# tc08-3-21.net
KiCad netlist of a schematic drawn in EAGLE
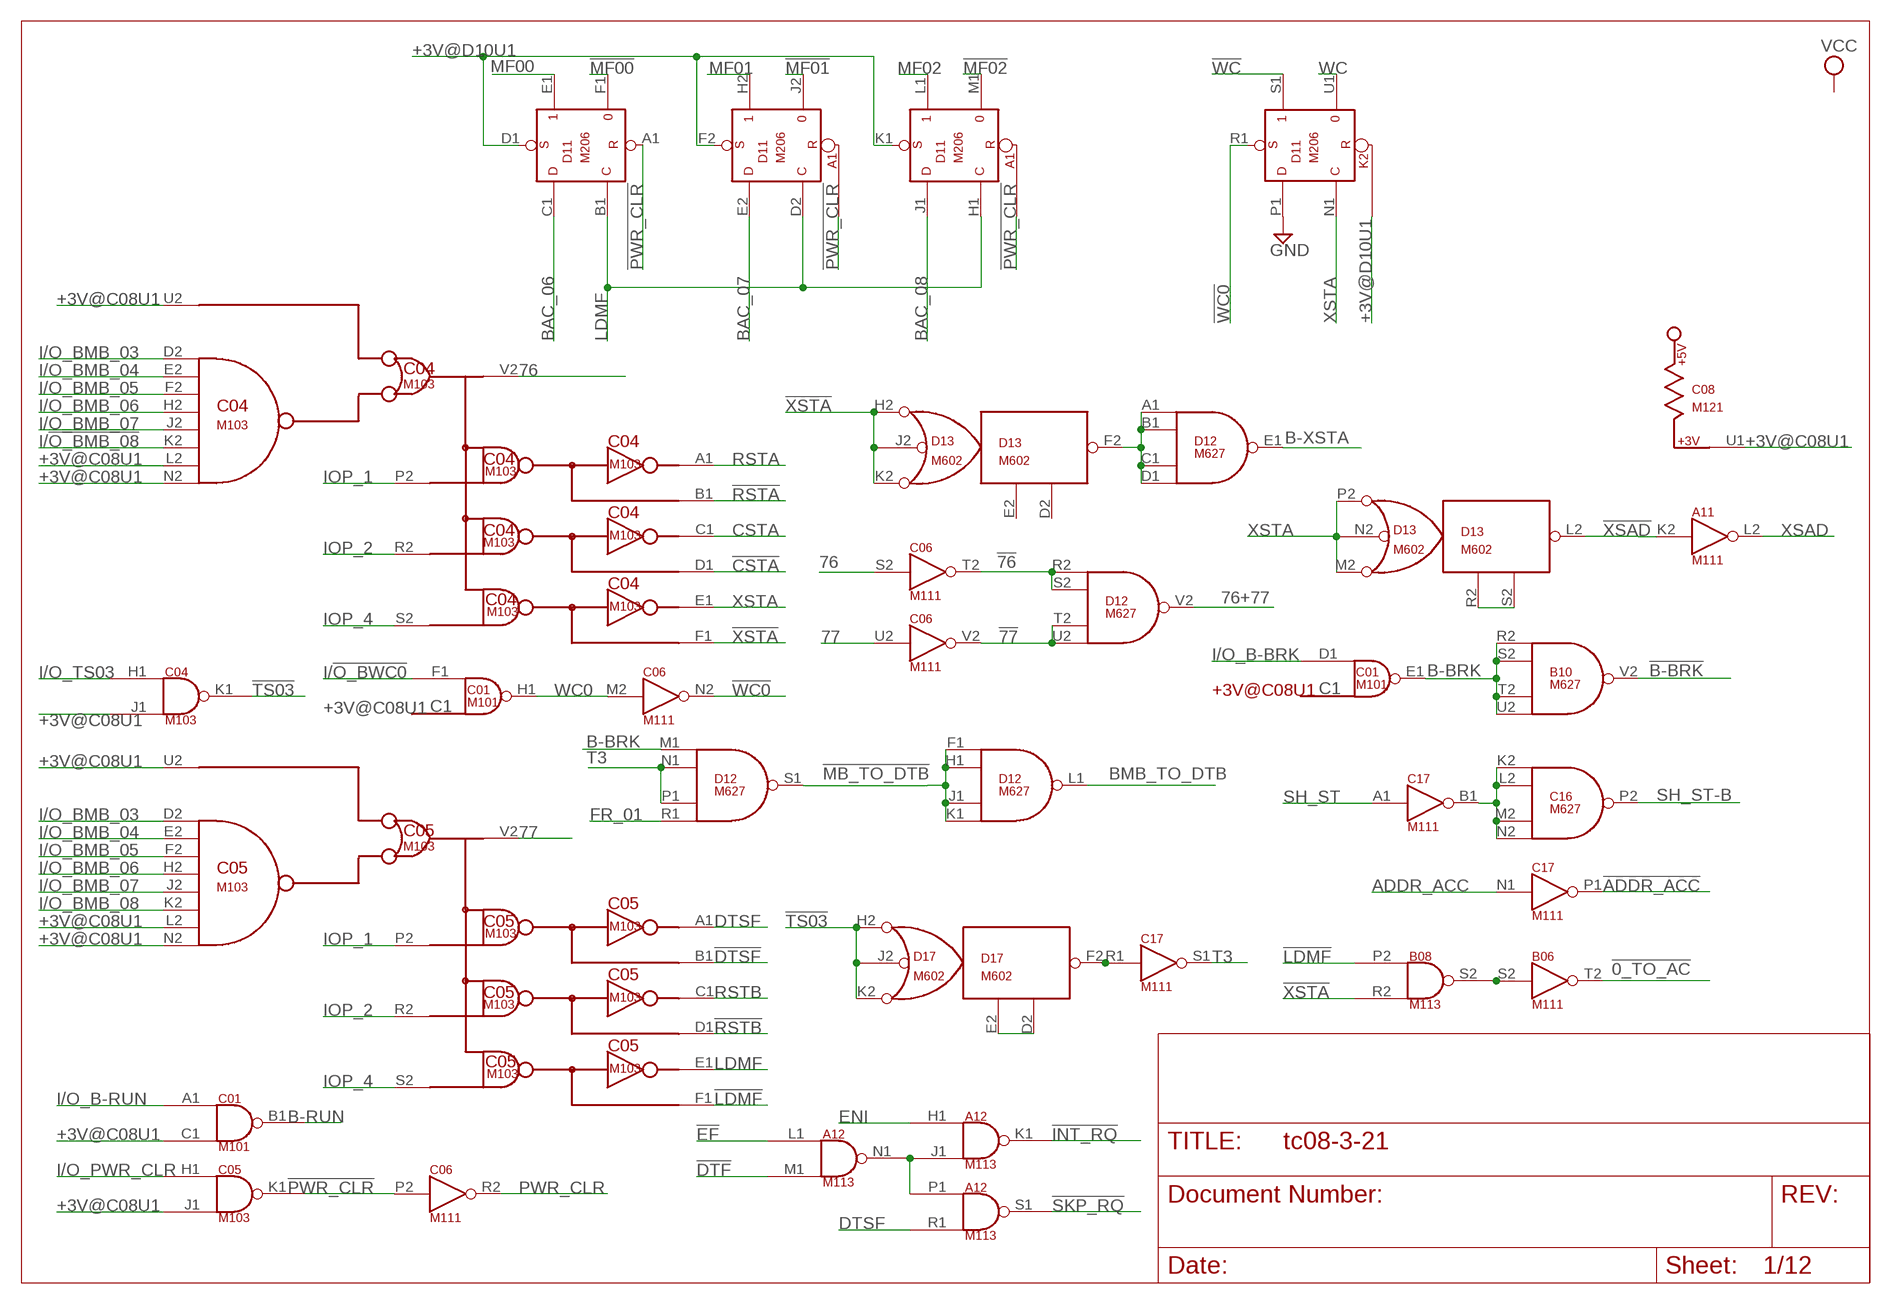
[diagram p0: schematic, sheet 1]
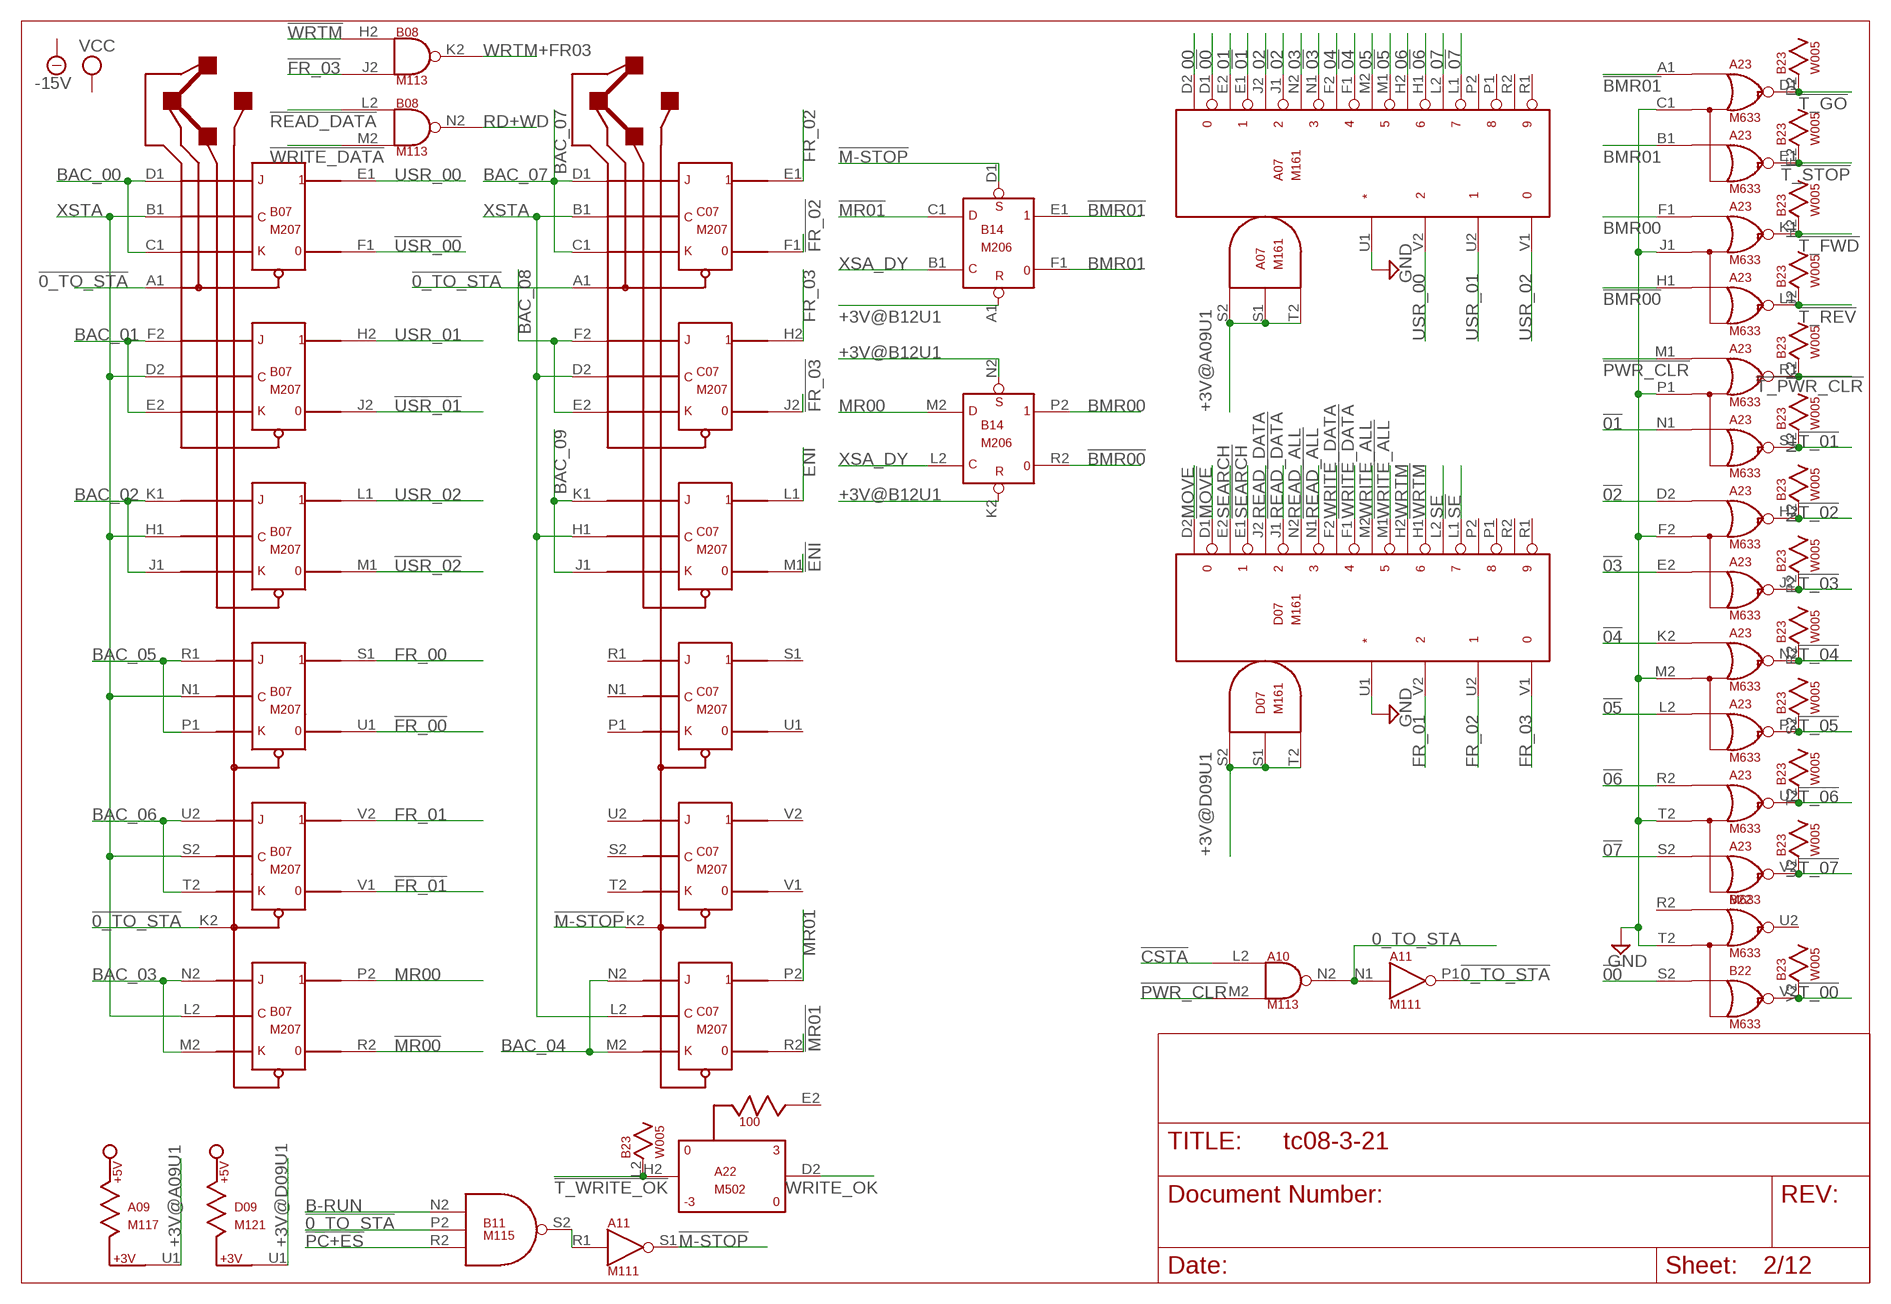
[diagram p1: schematic, sheet 2]
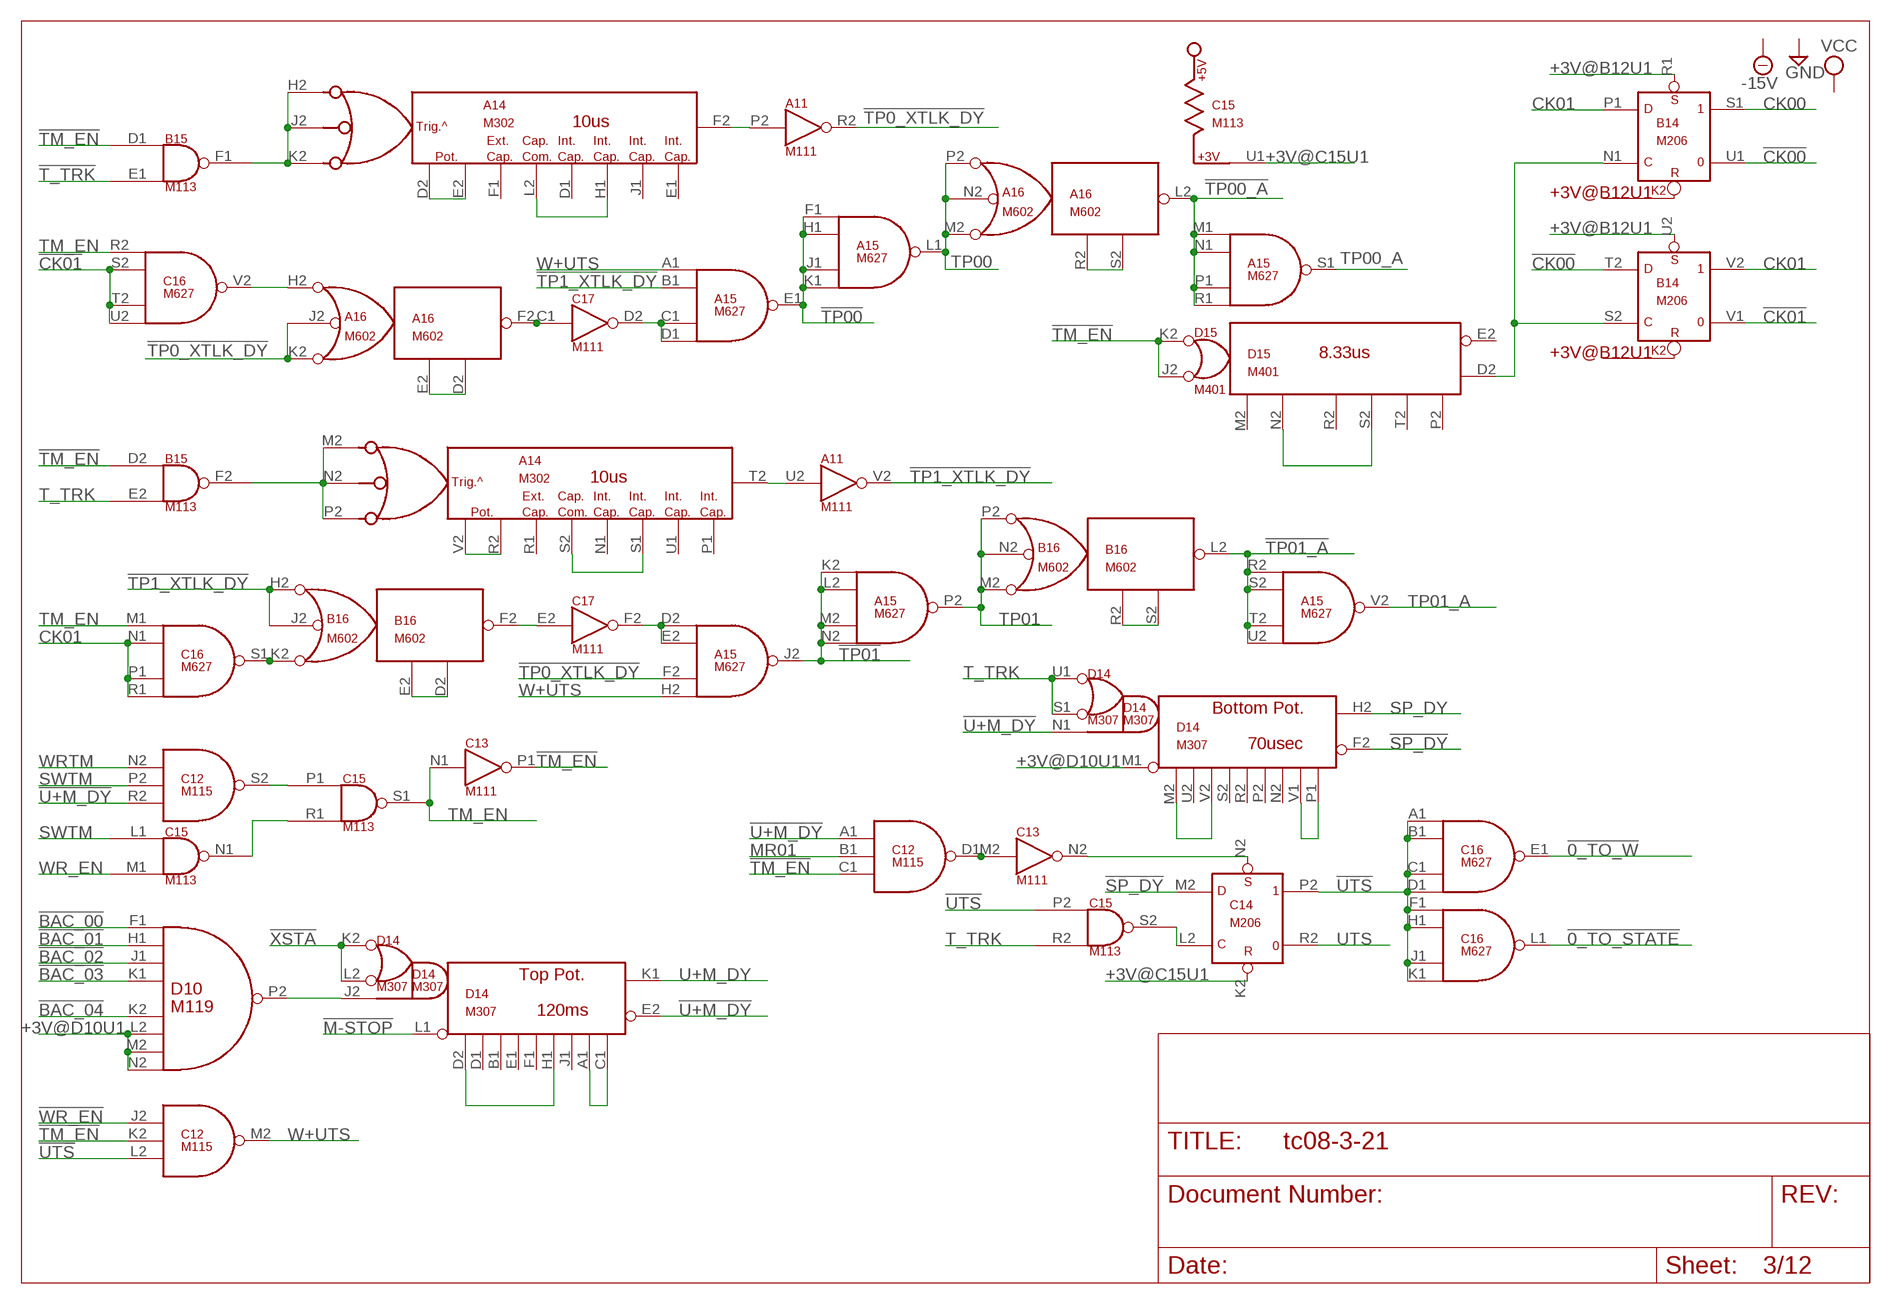
[diagram p2: schematic, sheet 3]
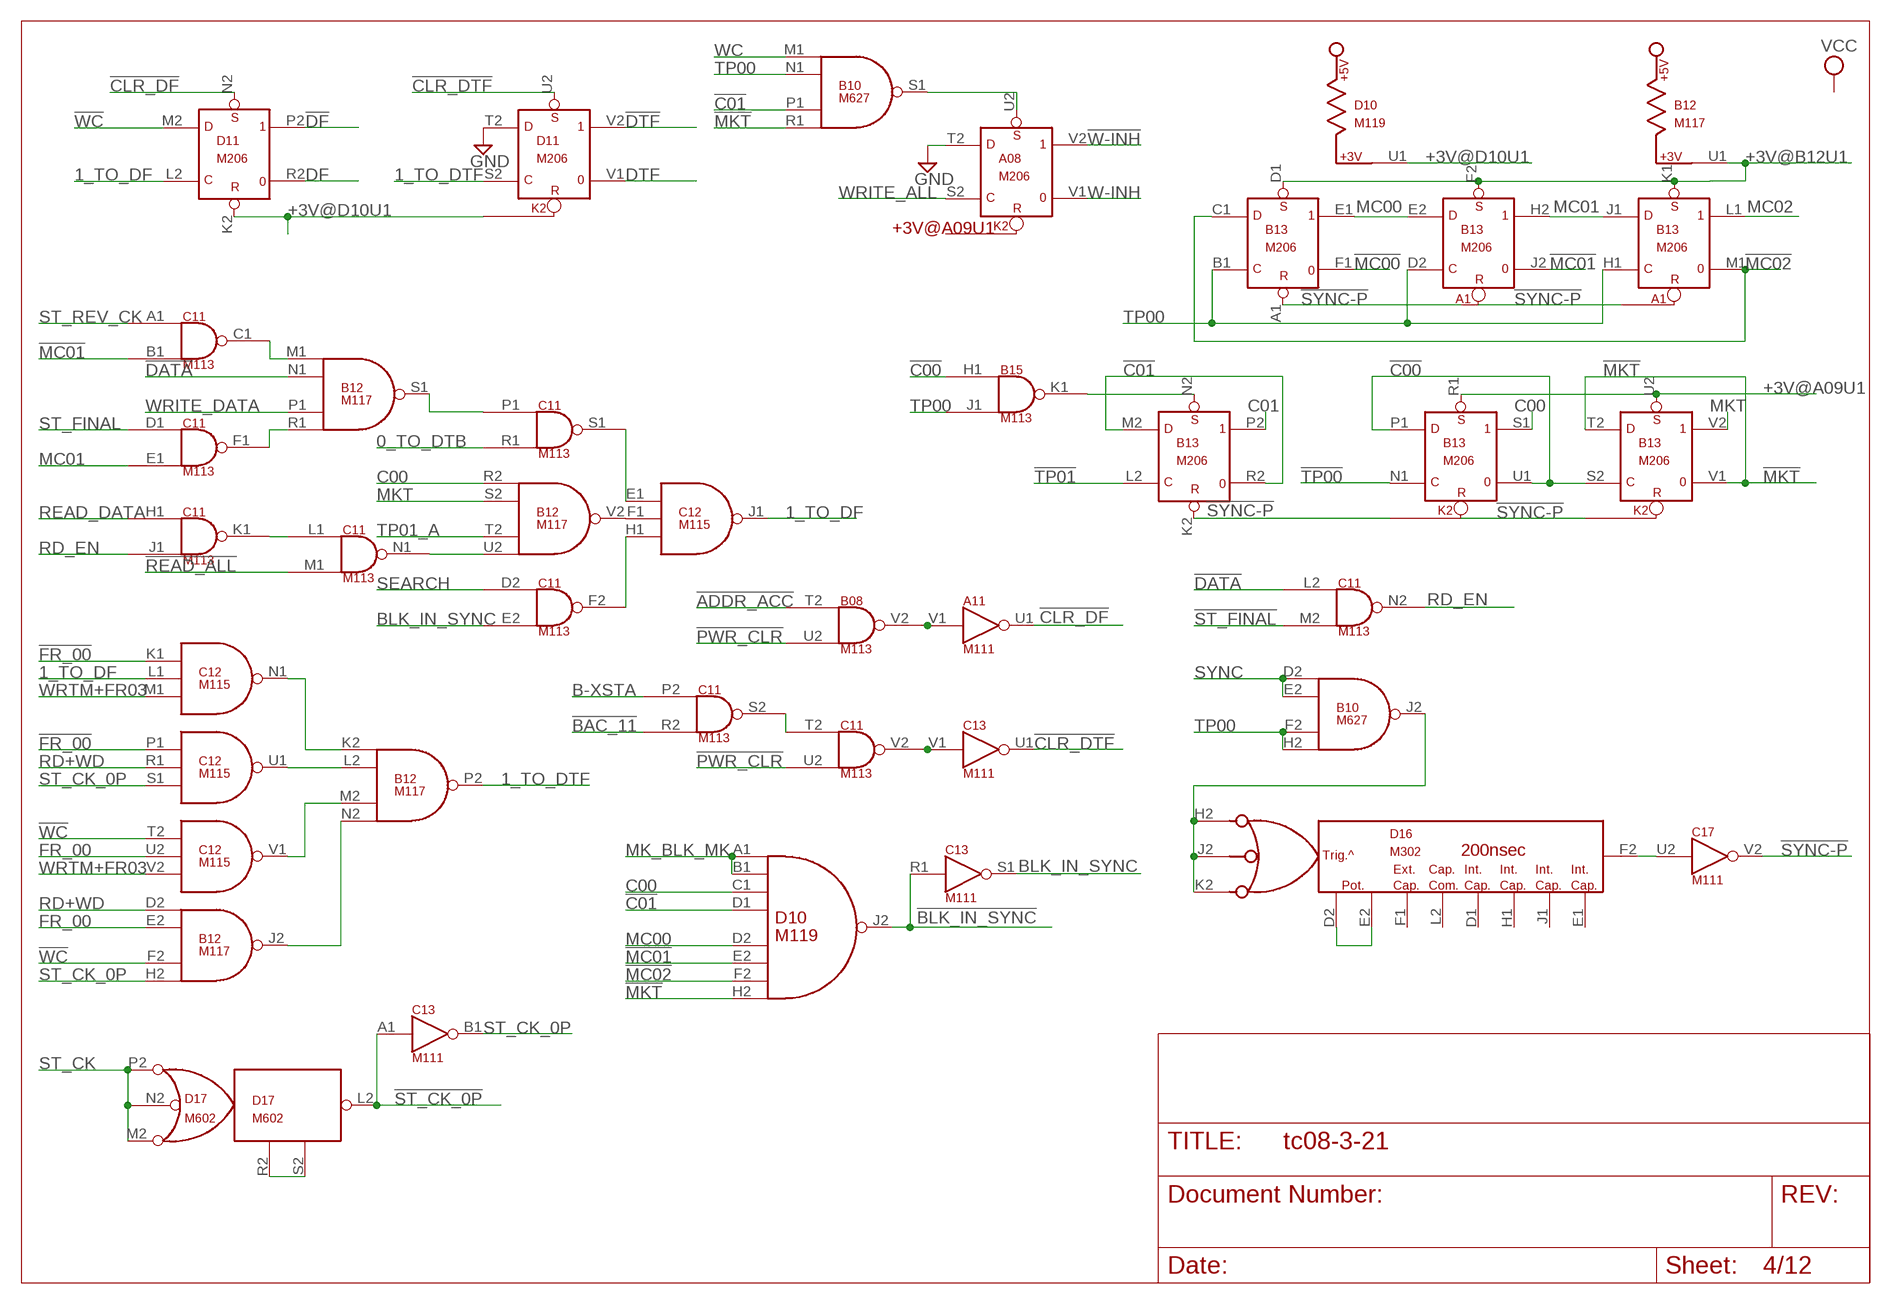
[diagram p3: schematic, sheet 4]
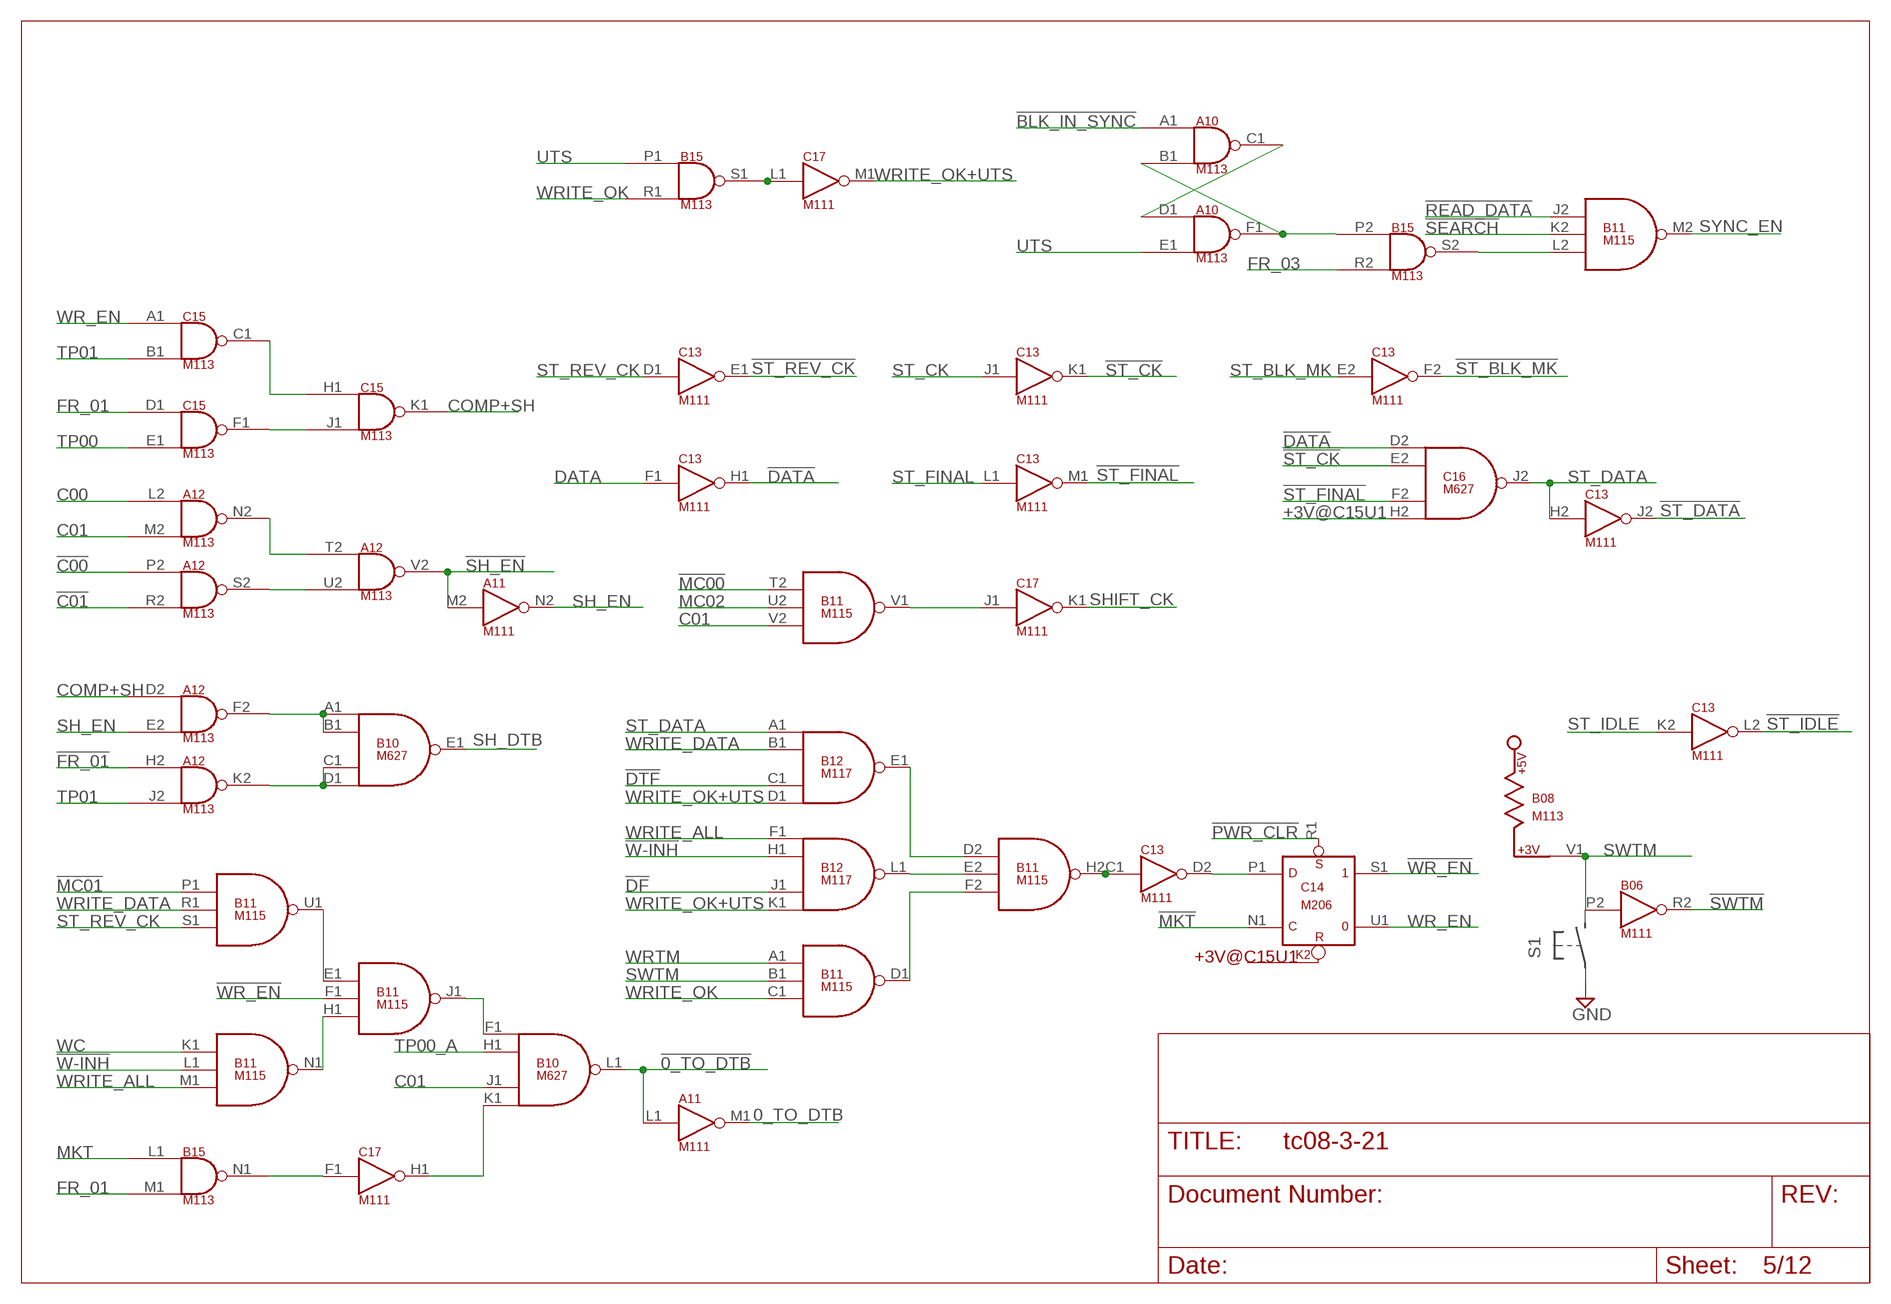
[diagram p4: schematic, sheet 5]
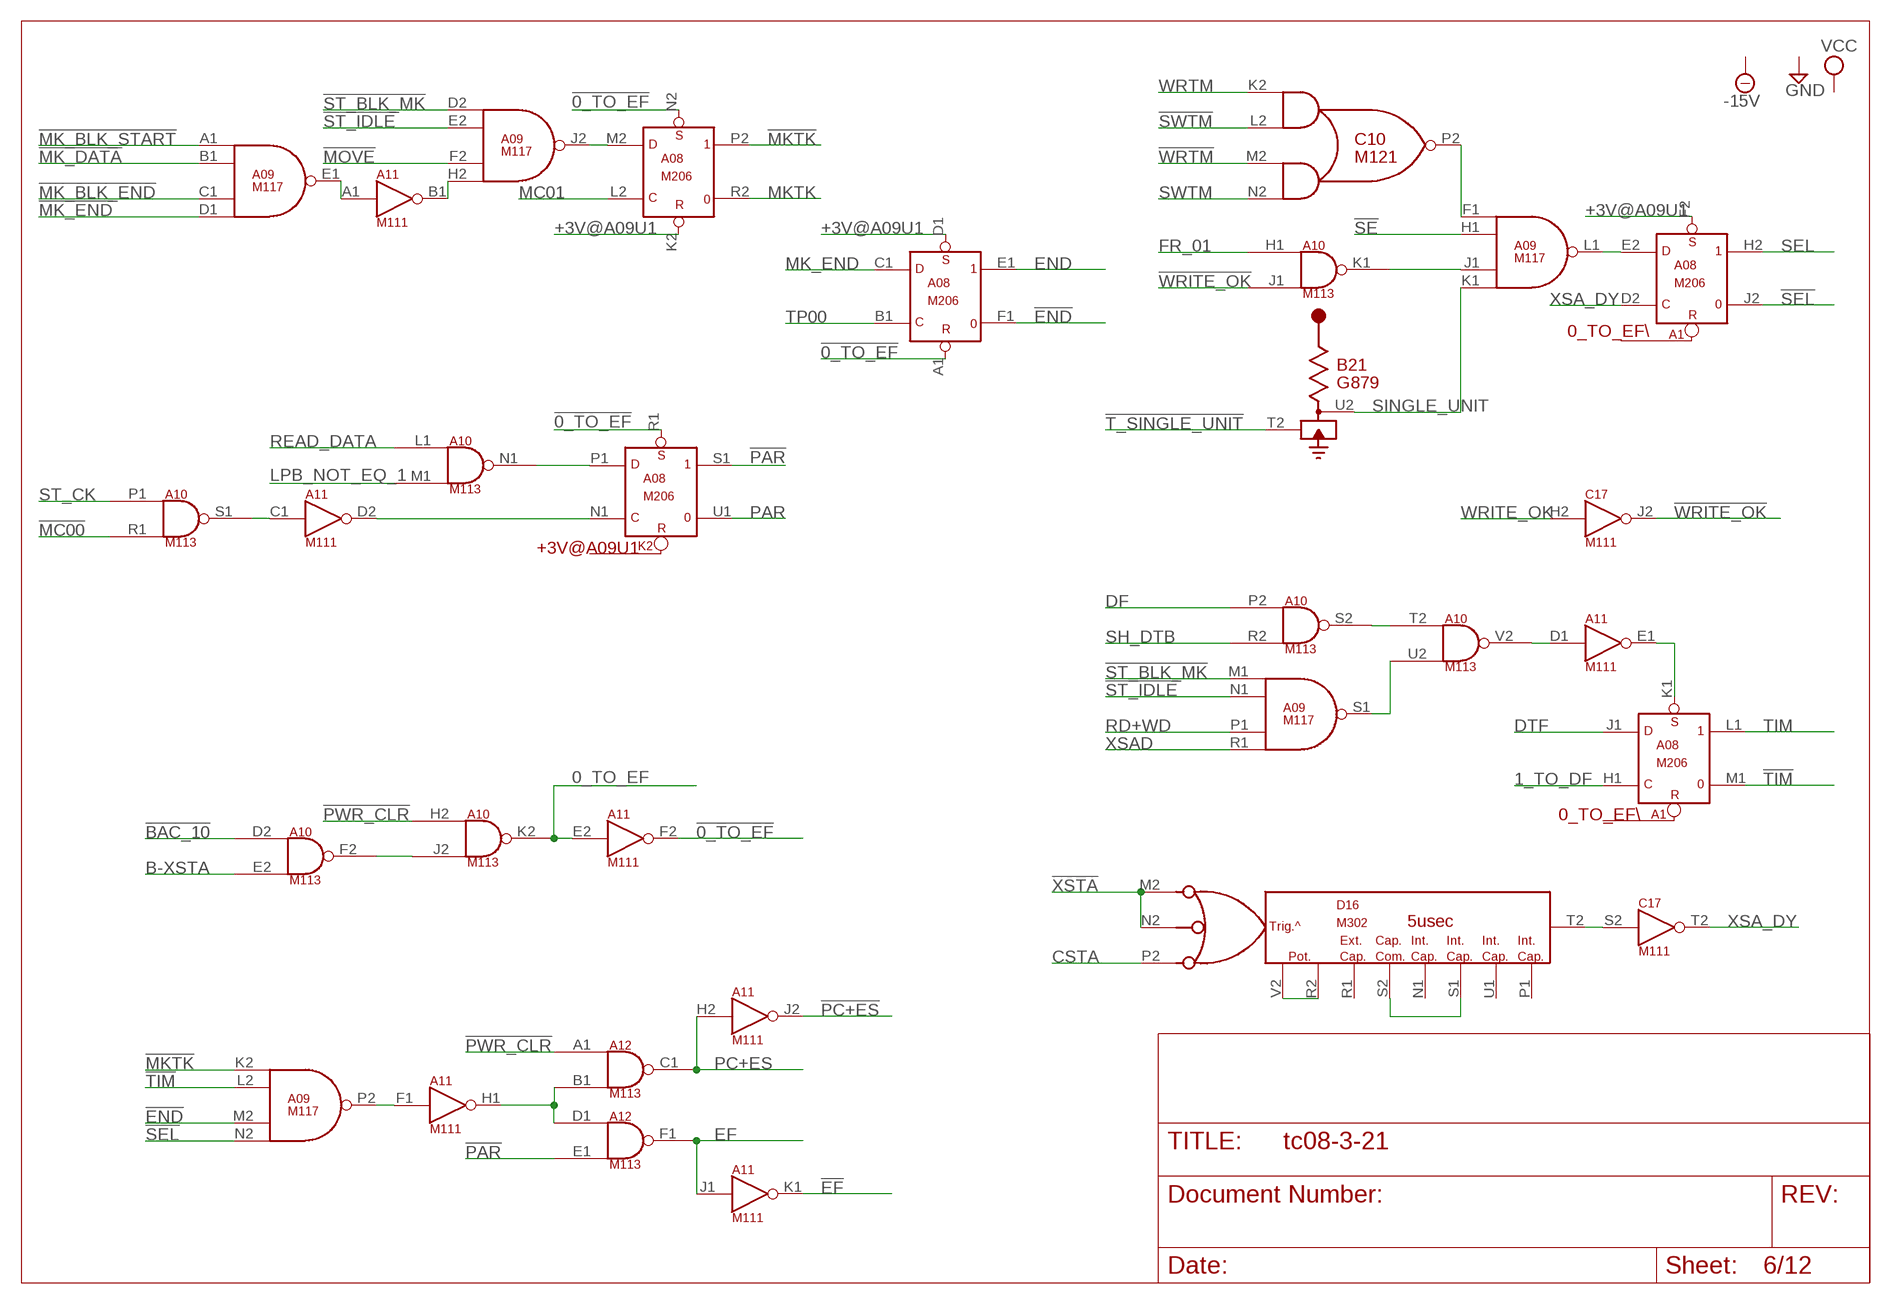
[diagram p5: schematic, sheet 6]
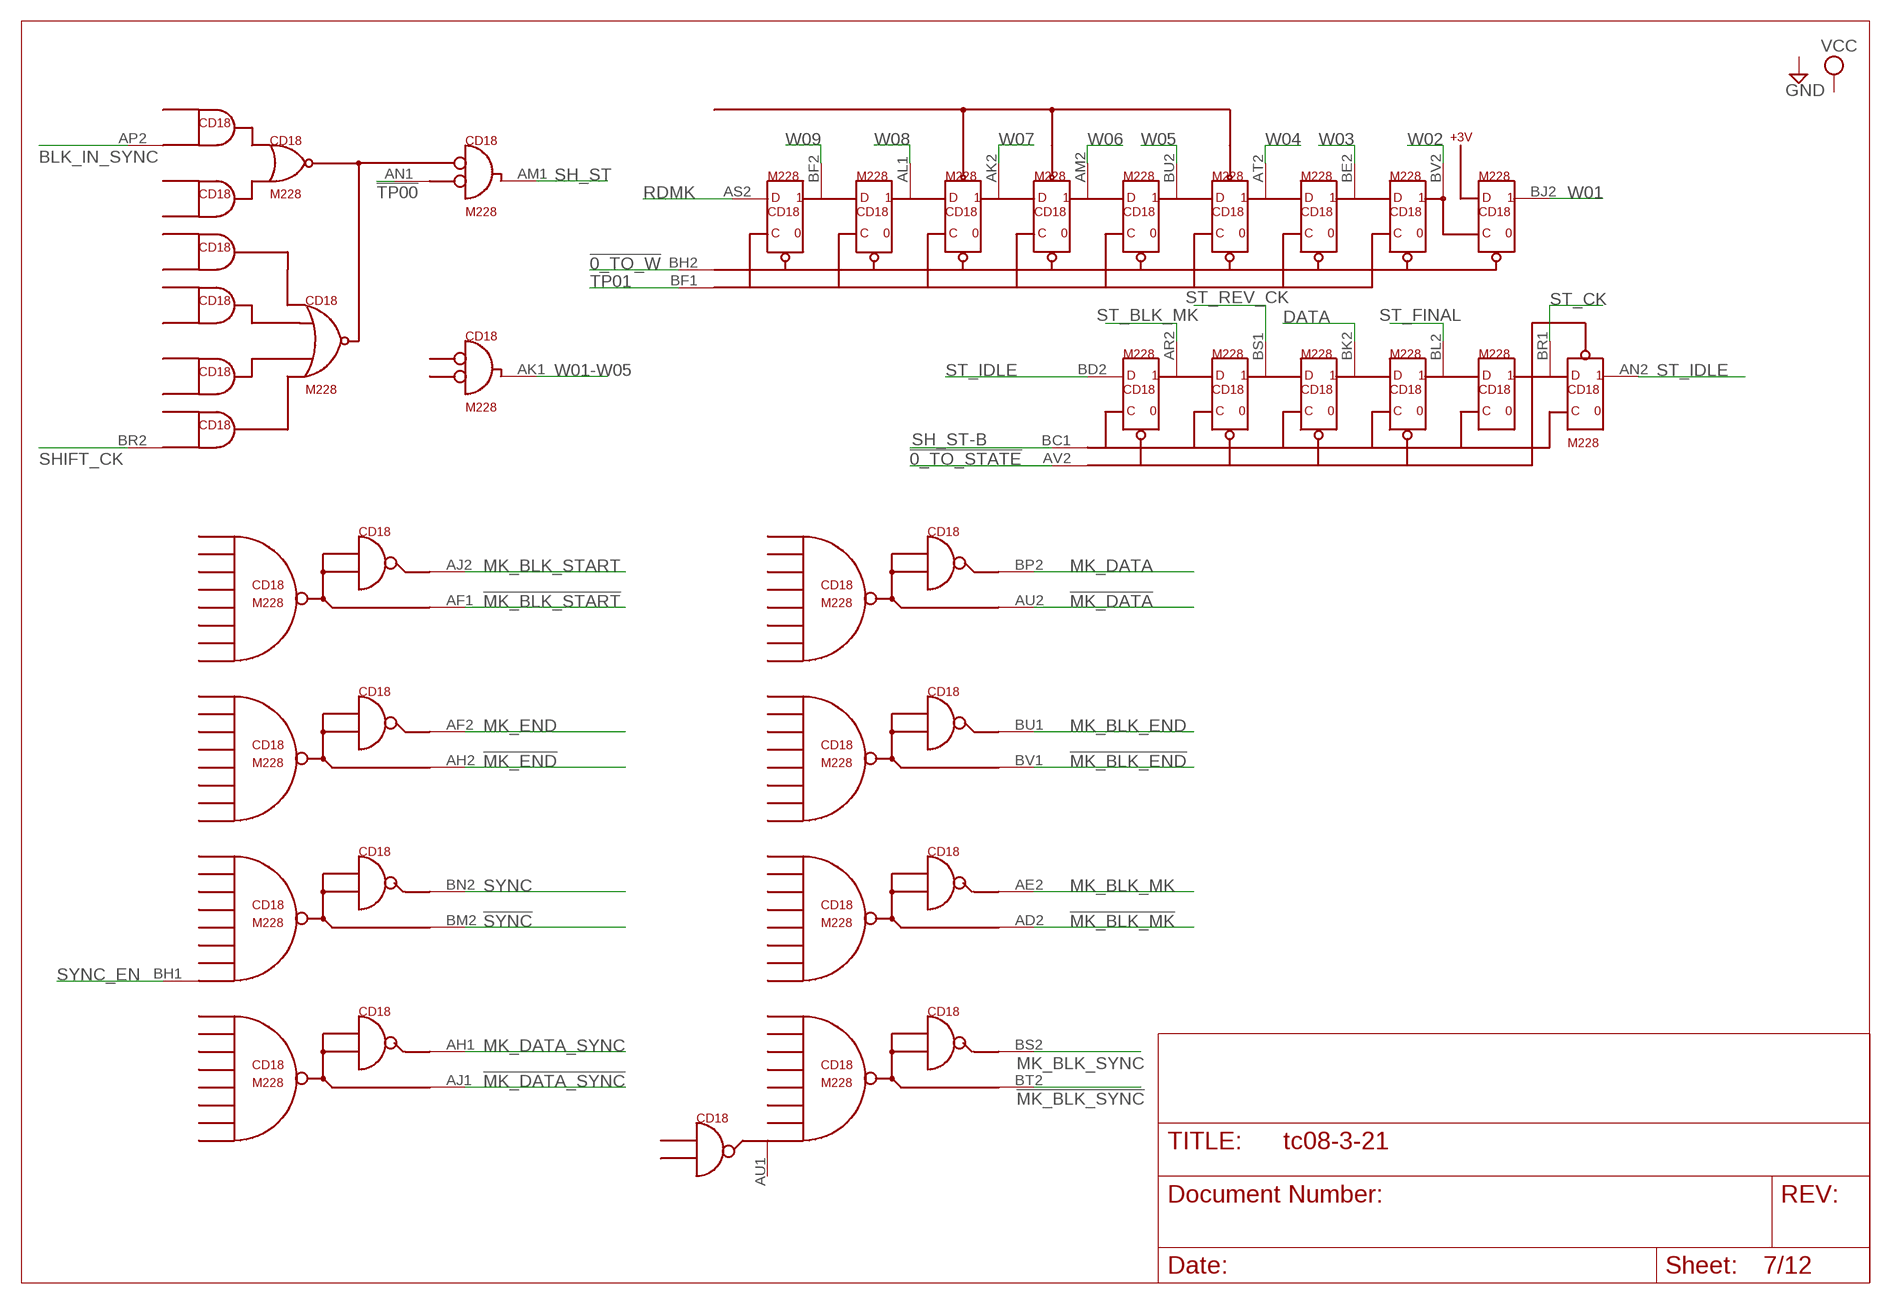
[diagram p6: schematic, sheet 7]
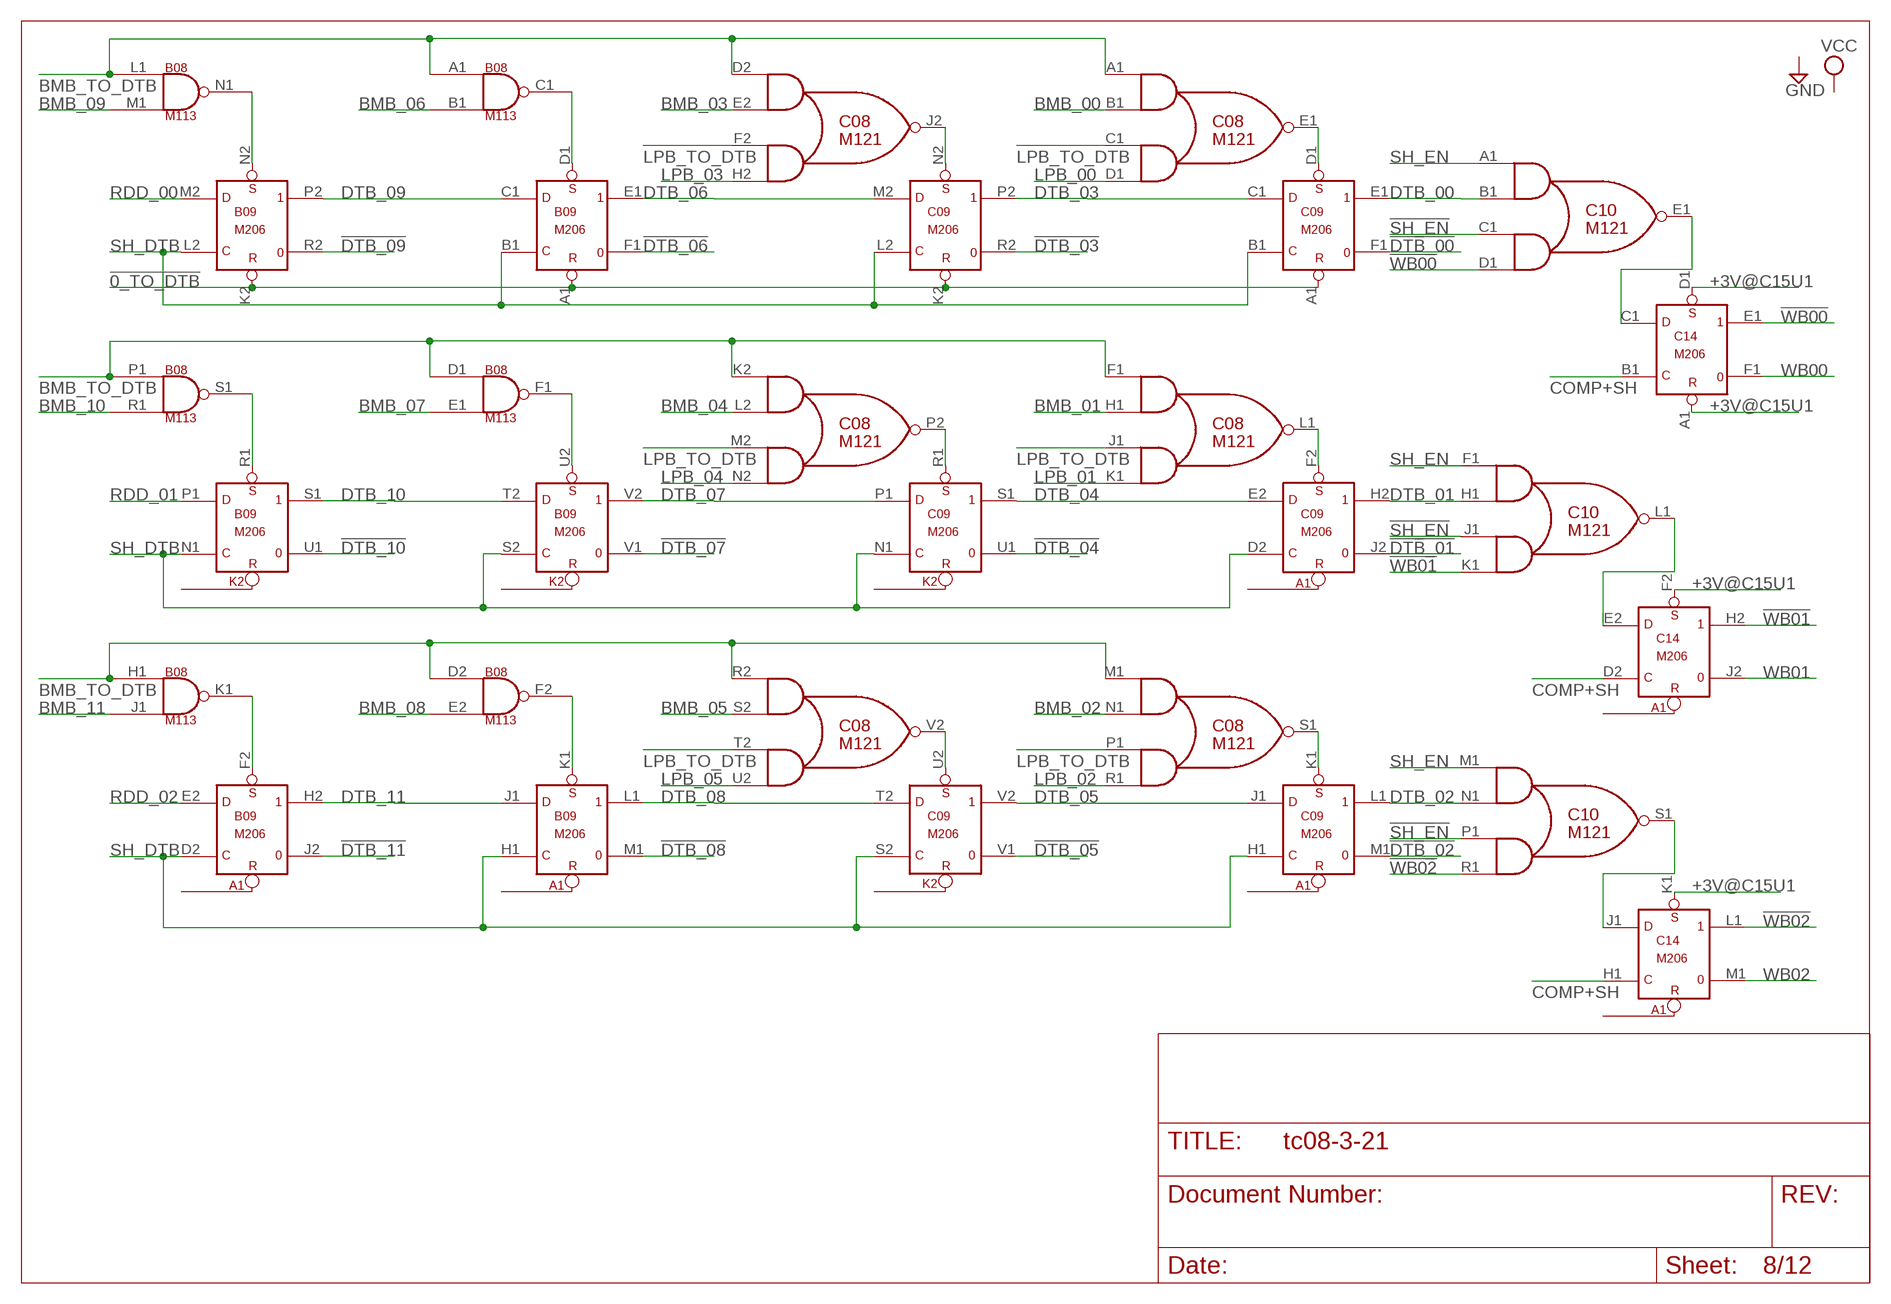
[diagram p7: schematic, sheet 8]
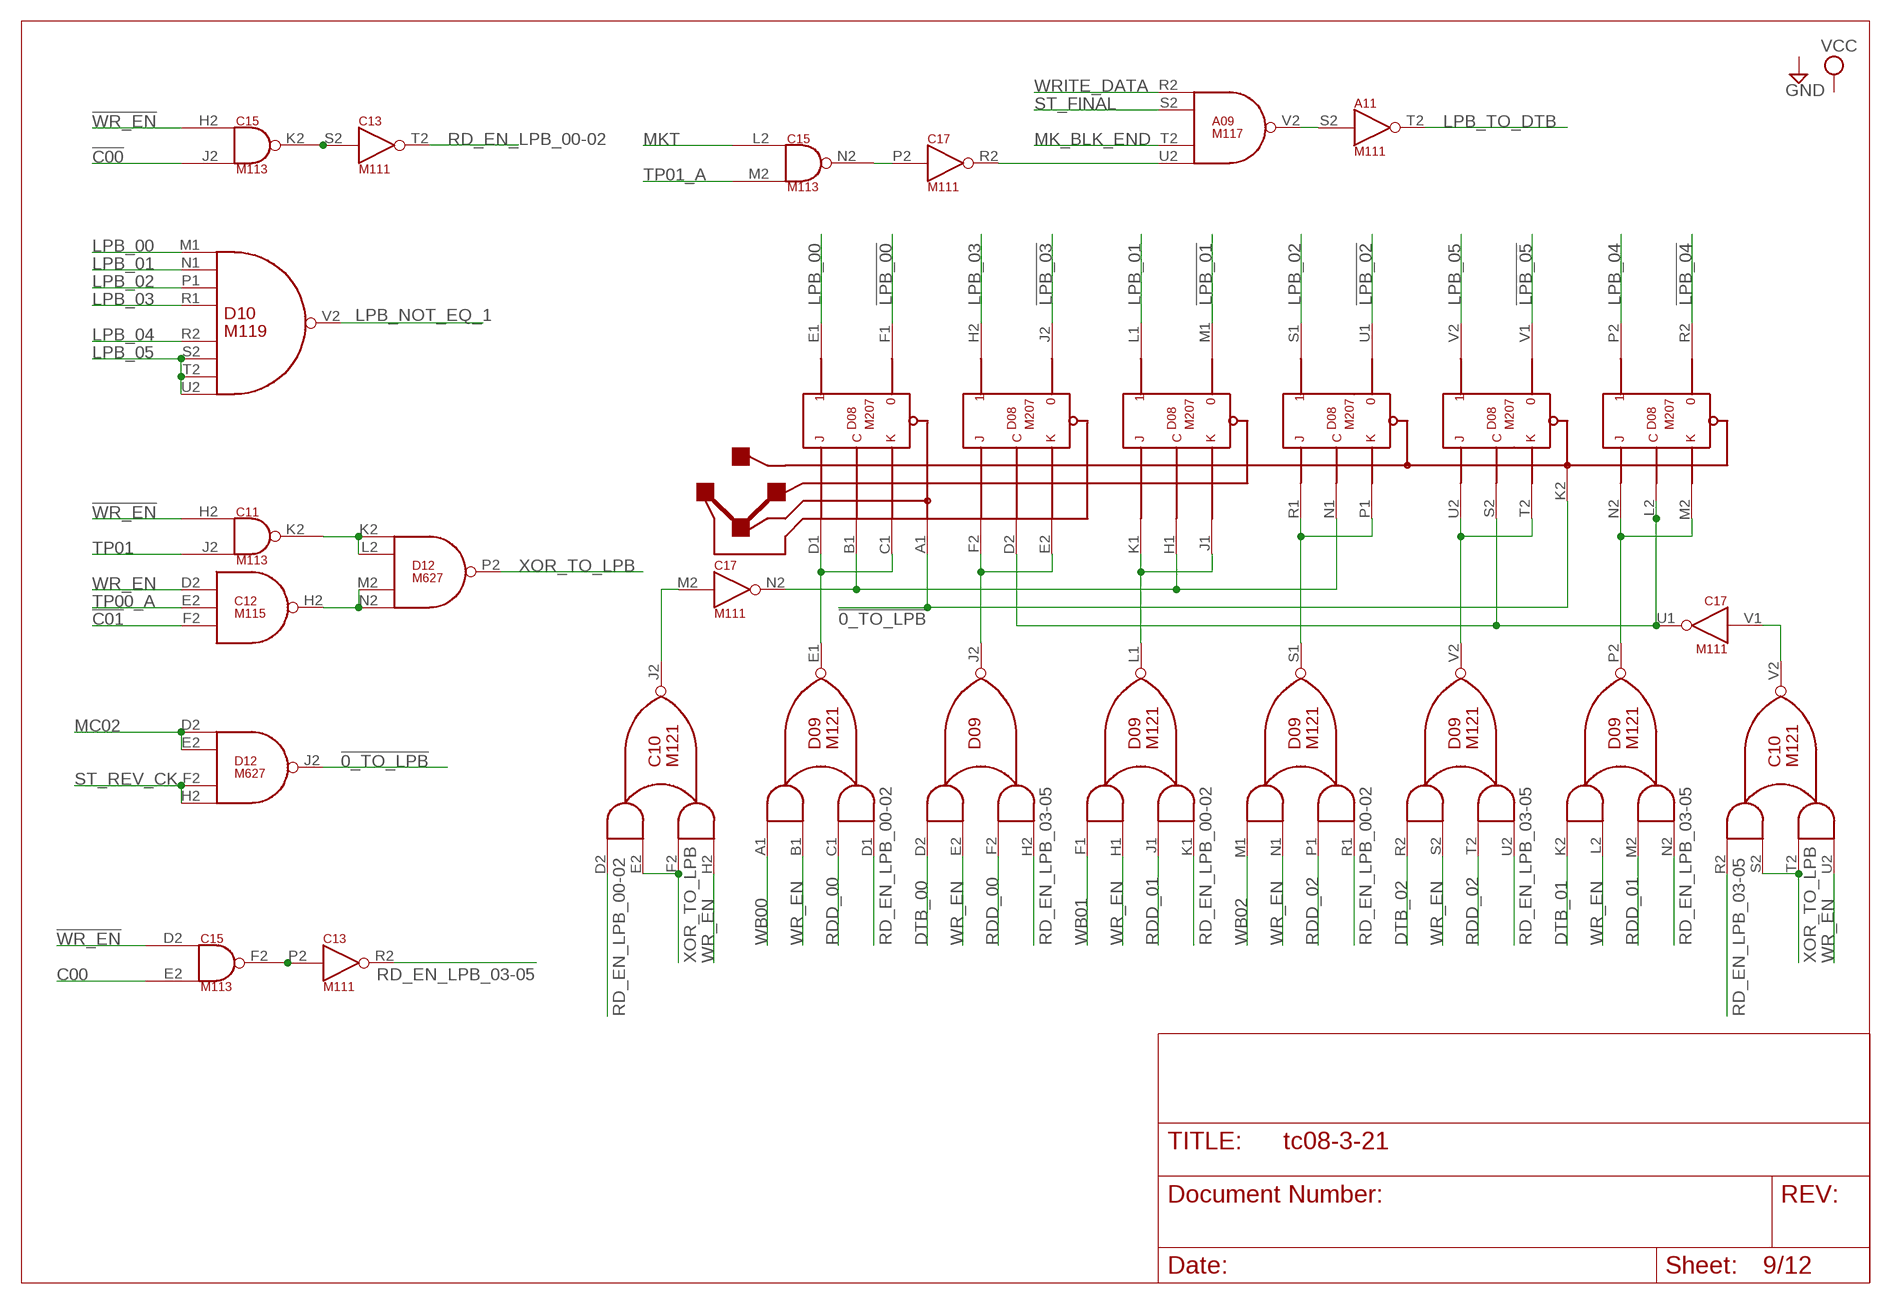
[diagram p8: schematic, sheet 9]
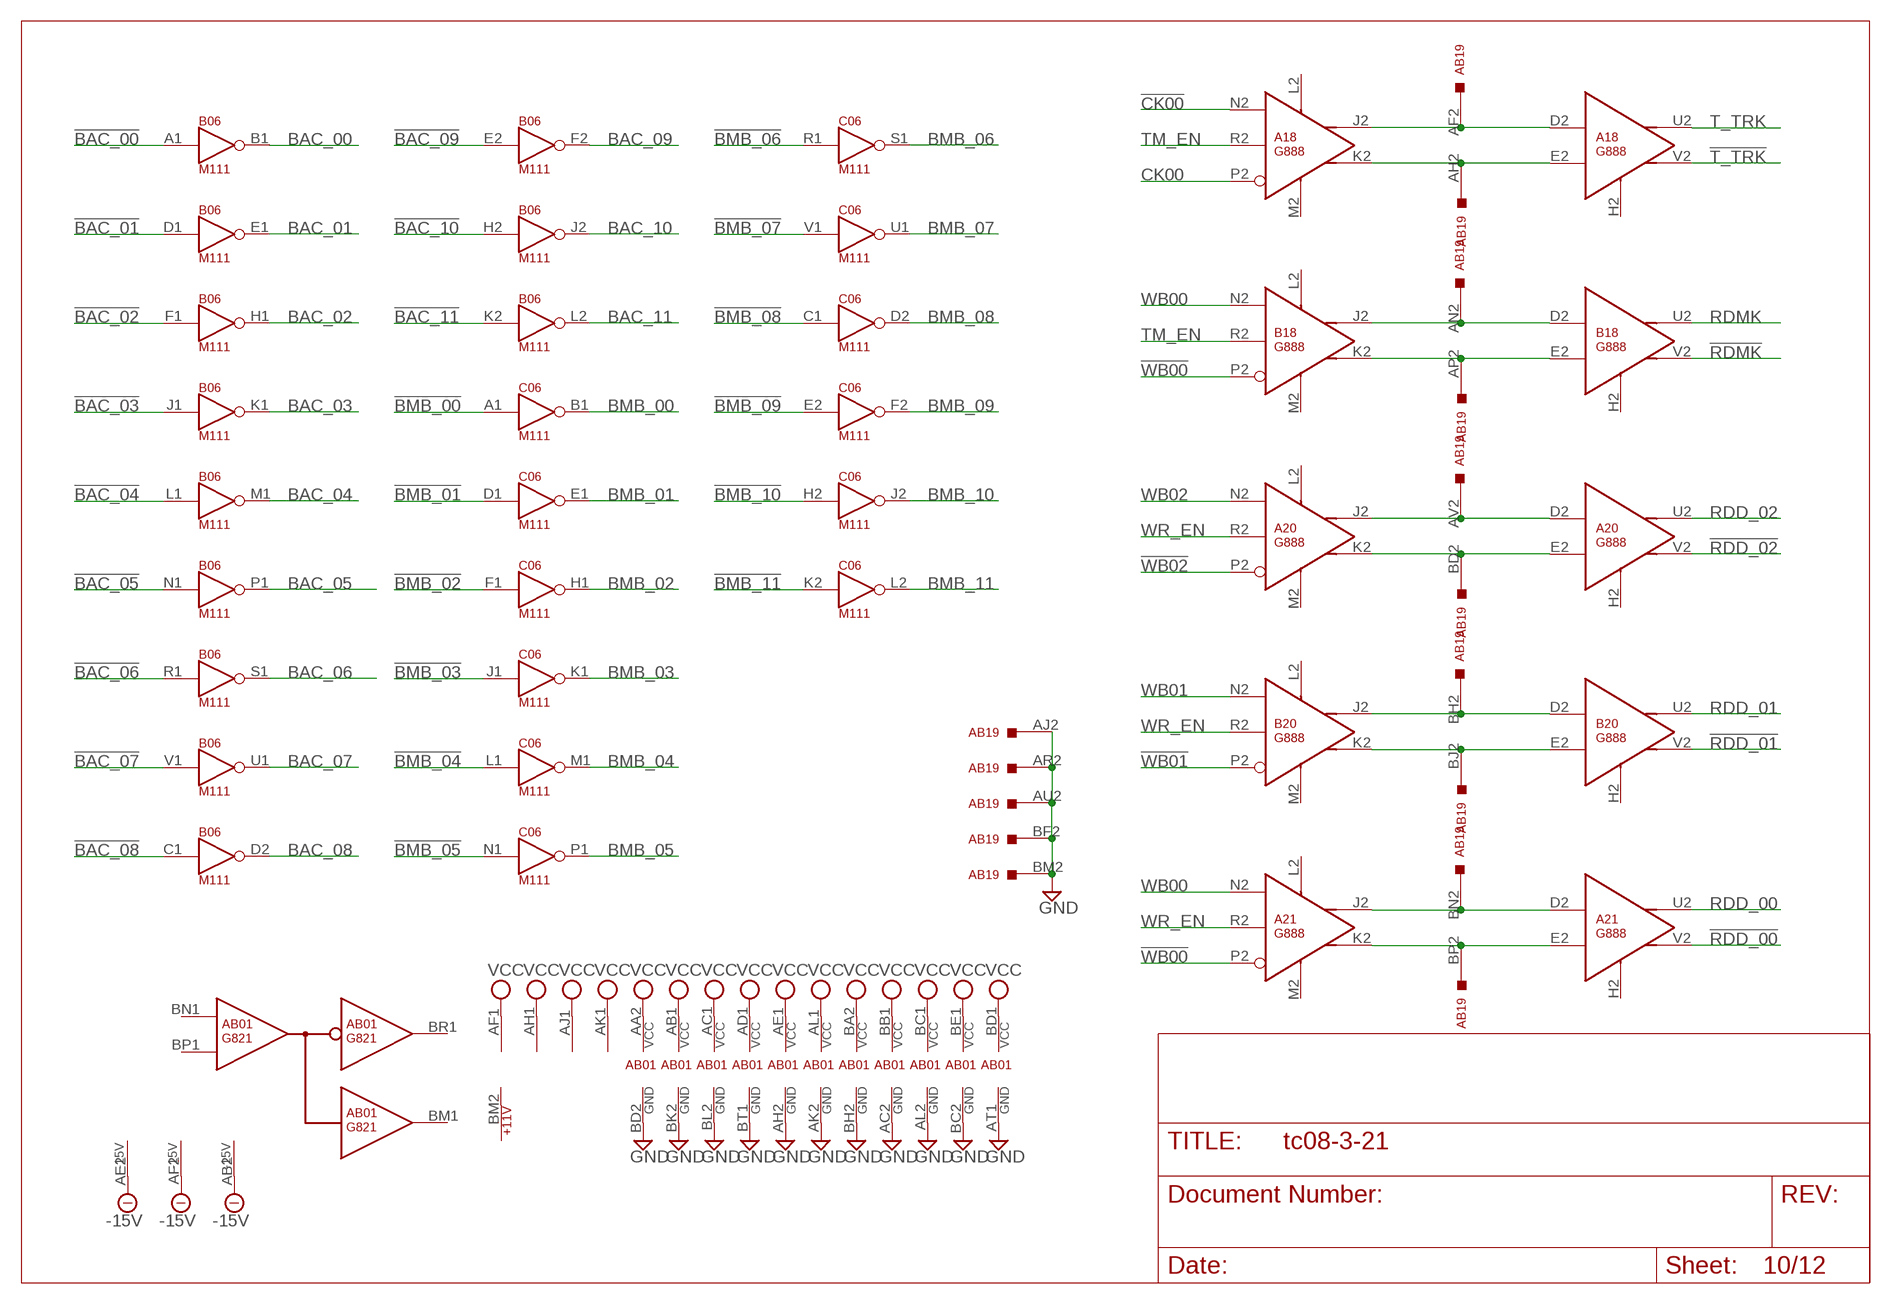
[diagram p9: schematic, sheet 10]
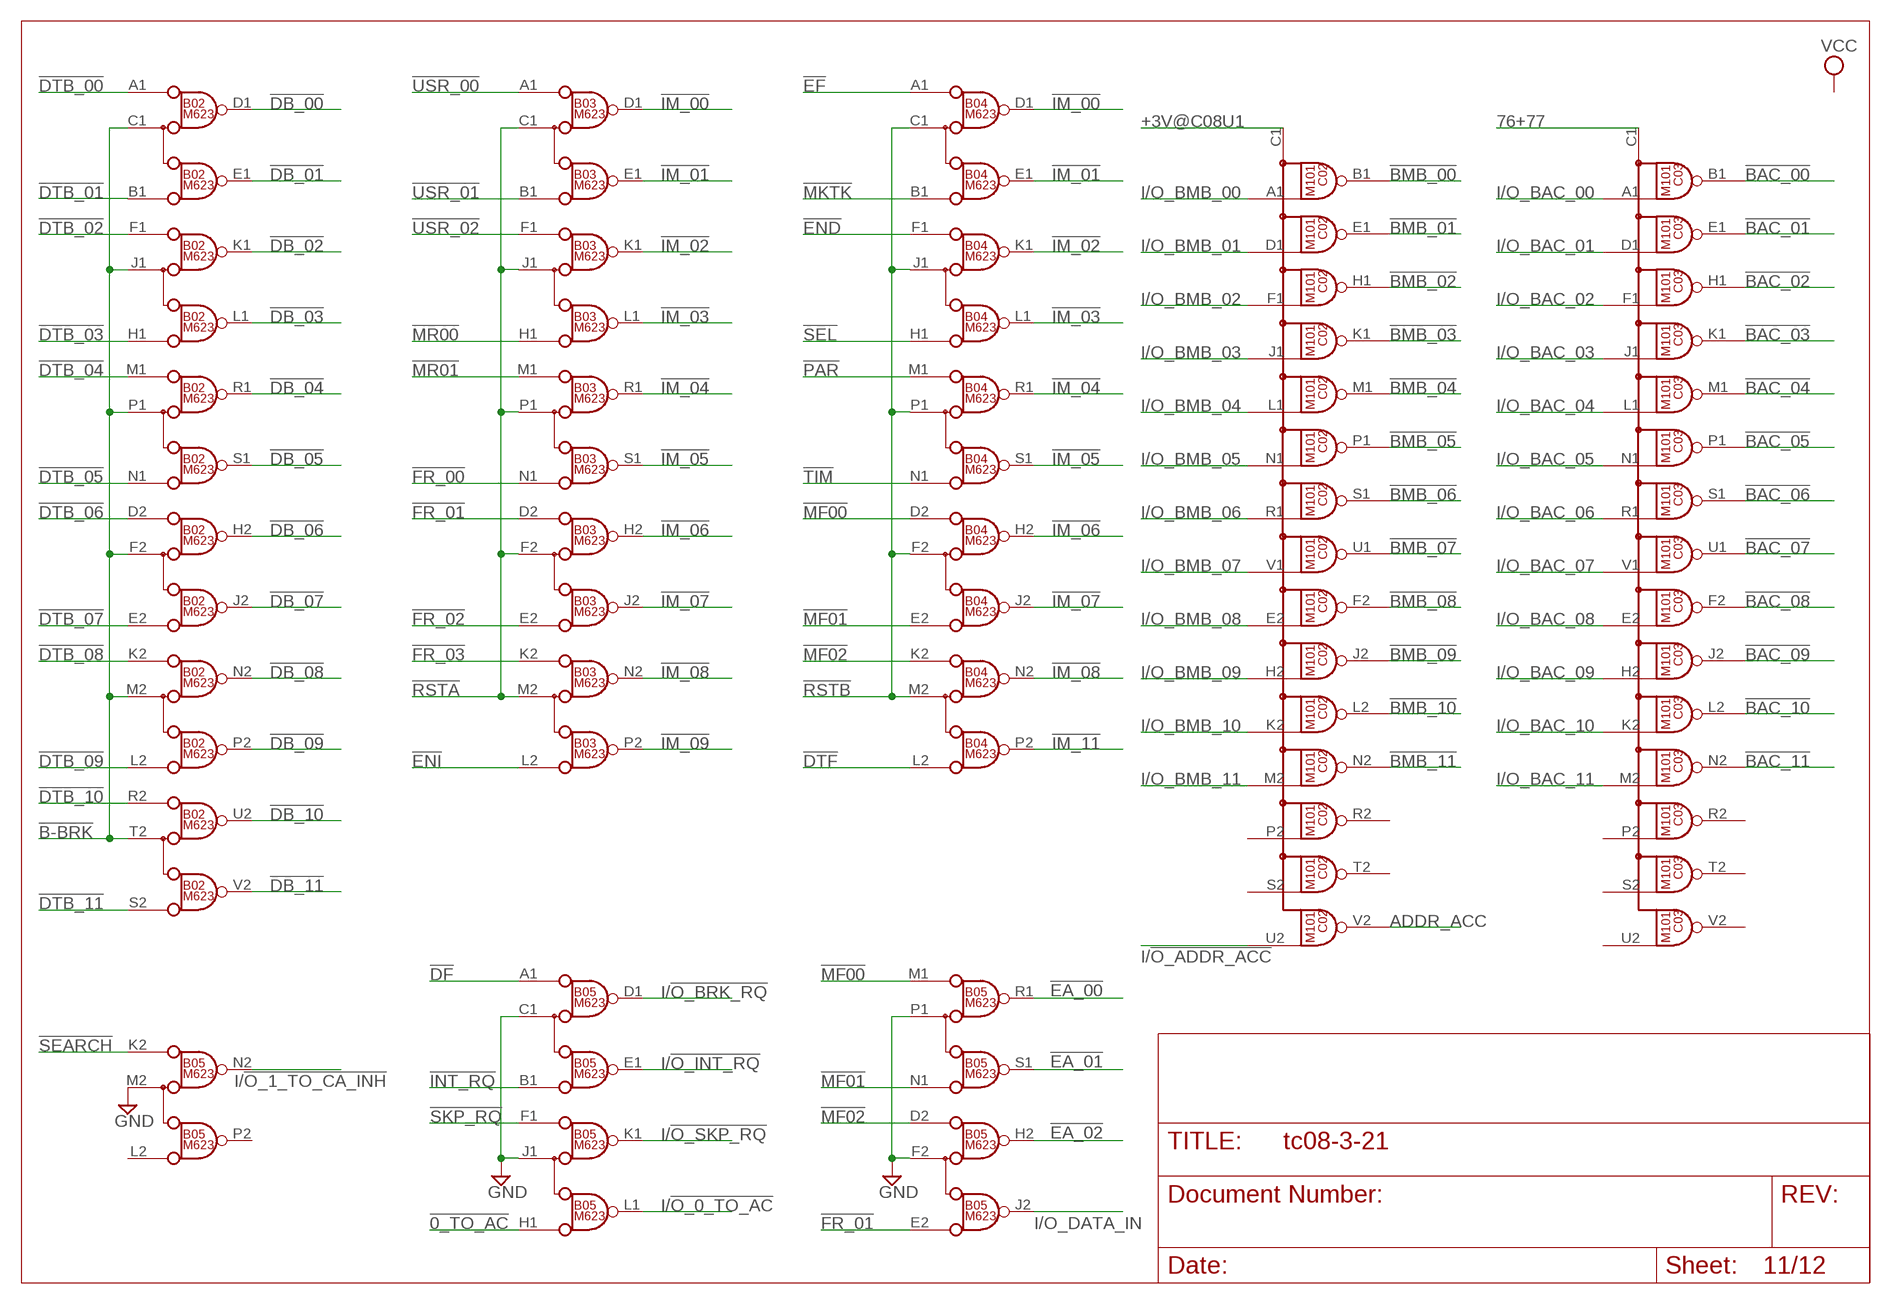
[diagram p10: schematic, sheet 11]
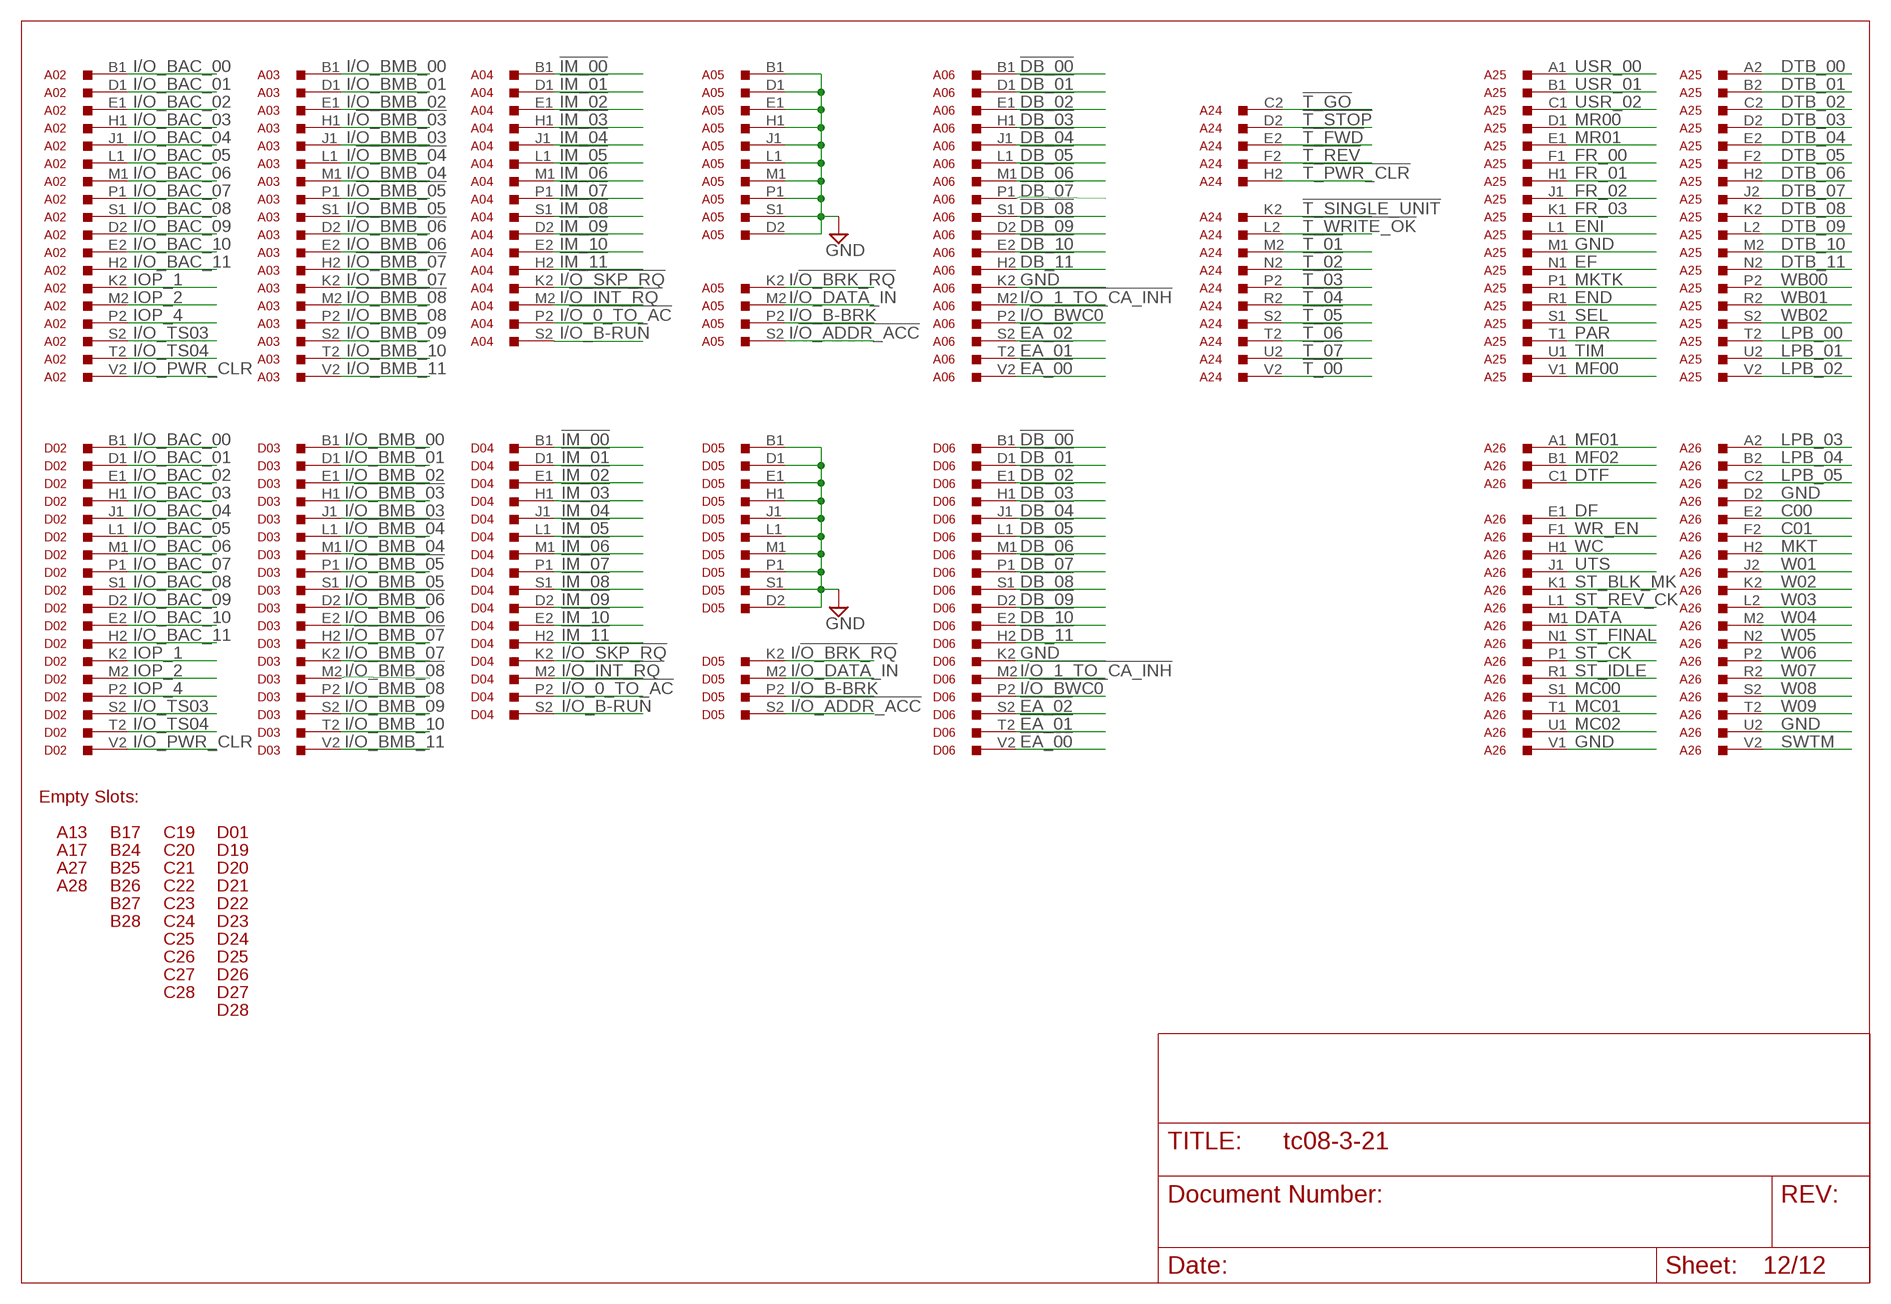
[diagram p11: schematic, sheet 12]

(export (version "E")
  (design (tool "Eeschema 10.0.6"))
  (components
    (comp (ref "A08")
      (value "M206")
      (footprint "eagle-import:H807")
      (libsource (lib "eagle-import") (part "M206X"))
    )
    (comp (ref "A09")
      (value "M117")
      (footprint "eagle-import:H807")
      (libsource (lib "eagle-import") (part "M117"))
    )
    (comp (ref "A10")
      (value "M113")
      (footprint "eagle-import:H807")
      (libsource (lib "eagle-import") (part "M113"))
    )
    (comp (ref "A11")
      (value "M111")
      (footprint "eagle-import:H807")
      (libsource (lib "eagle-import") (part "M111"))
    )
    (comp (ref "A12")
      (value "M113")
      (footprint "eagle-import:H807")
      (libsource (lib "eagle-import") (part "M113"))
    )
    (comp (ref "B21")
      (value "G879")
      (footprint "eagle-import:H807")
      (libsource (lib "eagle-import") (part "G879"))
    )
    (comp (ref "C10")
      (value "M121")
      (footprint "eagle-import:H807")
      (libsource (lib "eagle-import") (part "M121"))
    )
    (comp (ref "C17")
      (value "M111")
      (footprint "eagle-import:H807")
      (libsource (lib "eagle-import") (part "M111"))
    )
    (comp (ref "D16")
      (value "M302")
      (footprint "eagle-import:H807")
      (libsource (lib "eagle-import") (part "M302"))
    )
    (comp (ref "B08")
      (value "M113")
      (footprint "eagle-import:H807")
      (libsource (lib "eagle-import") (part "M113"))
    )
    (comp (ref "B09")
      (value "M206")
      (footprint "eagle-import:H807")
      (libsource (lib "eagle-import") (part "M206X"))
    )
    (comp (ref "C08")
      (value "M121")
      (footprint "eagle-import:H807")
      (libsource (lib "eagle-import") (part "M121"))
    )
    (comp (ref "C09")
      (value "M206")
      (footprint "eagle-import:H807")
      (libsource (lib "eagle-import") (part "M206X"))
    )
    (comp (ref "C14")
      (value "M206")
      (footprint "eagle-import:H807")
      (libsource (lib "eagle-import") (part "M206X"))
    )
    (comp (ref "A02")
      (value "M903")
      (footprint "eagle-import:H807")
      (libsource (lib "eagle-import") (part "M903"))
    )
    (comp (ref "A03")
      (value "M903")
      (footprint "eagle-import:H807")
      (libsource (lib "eagle-import") (part "M903"))
    )
    (comp (ref "A04")
      (value "M903")
      (footprint "eagle-import:H807")
      (libsource (lib "eagle-import") (part "M903"))
    )
    (comp (ref "A05")
      (value "M903")
      (footprint "eagle-import:H807")
      (libsource (lib "eagle-import") (part "M903"))
    )
    (comp (ref "A06")
      (value "M903")
      (footprint "eagle-import:H807")
      (libsource (lib "eagle-import") (part "M903"))
    )
    (comp (ref "A13")
      (value "H807")
      (footprint "eagle-import:H807")
      (libsource (lib "eagle-import") (part "H807"))
    )
    (comp (ref "A17")
      (value "H807")
      (footprint "eagle-import:H807")
      (libsource (lib "eagle-import") (part "H807"))
    )
    (comp (ref "A24")
      (value "W023")
      (footprint "eagle-import:H807")
      (libsource (lib "eagle-import") (part "W023"))
    )
    (comp (ref "A25")
      (value "M916")
      (footprint "eagle-import:H807")
      (libsource (lib "eagle-import") (part "M916"))
    )
    (comp (ref "A26")
      (value "M916")
      (footprint "eagle-import:H807")
      (libsource (lib "eagle-import") (part "M916"))
    )
    (comp (ref "A27")
      (value "H807")
      (footprint "eagle-import:H807")
      (libsource (lib "eagle-import") (part "H807"))
    )
    (comp (ref "A28")
      (value "H807")
      (footprint "eagle-import:H807")
      (libsource (lib "eagle-import") (part "H807"))
    )
    (comp (ref "B17")
      (value "H807")
      (footprint "eagle-import:H807")
      (libsource (lib "eagle-import") (part "H807"))
    )
    (comp (ref "B24")
      (value "H807")
      (footprint "eagle-import:H807")
      (libsource (lib "eagle-import") (part "H807"))
    )
    (comp (ref "B25")
      (value "H807")
      (footprint "eagle-import:H807")
      (libsource (lib "eagle-import") (part "H807"))
    )
    (comp (ref "B26")
      (value "H807")
      (footprint "eagle-import:H807")
      (libsource (lib "eagle-import") (part "H807"))
    )
    (comp (ref "B27")
      (value "H807")
      (footprint "eagle-import:H807")
      (libsource (lib "eagle-import") (part "H807"))
    )
    (comp (ref "B28")
      (value "H807")
      (footprint "eagle-import:H807")
      (libsource (lib "eagle-import") (part "H807"))
    )
    (comp (ref "C19")
      (value "H807")
      (footprint "eagle-import:H807")
      (libsource (lib "eagle-import") (part "H807"))
    )
    (comp (ref "C20")
      (value "H807")
      (footprint "eagle-import:H807")
      (libsource (lib "eagle-import") (part "H807"))
    )
    (comp (ref "C21")
      (value "H807")
      (footprint "eagle-import:H807")
      (libsource (lib "eagle-import") (part "H807"))
    )
    (comp (ref "C22")
      (value "H807")
      (footprint "eagle-import:H807")
      (libsource (lib "eagle-import") (part "H807"))
    )
    (comp (ref "C23")
      (value "H807")
      (footprint "eagle-import:H807")
      (libsource (lib "eagle-import") (part "H807"))
    )
    (comp (ref "C24")
      (value "H807")
      (footprint "eagle-import:H807")
      (libsource (lib "eagle-import") (part "H807"))
    )
    (comp (ref "C25")
      (value "H807")
      (footprint "eagle-import:H807")
      (libsource (lib "eagle-import") (part "H807"))
    )
    (comp (ref "C26")
      (value "H807")
      (footprint "eagle-import:H807")
      (libsource (lib "eagle-import") (part "H807"))
    )
    (comp (ref "C27")
      (value "H807")
      (footprint "eagle-import:H807")
      (libsource (lib "eagle-import") (part "H807"))
    )
    (comp (ref "C28")
      (value "H807")
      (footprint "eagle-import:H807")
      (libsource (lib "eagle-import") (part "H807"))
    )
    (comp (ref "D01")
      (value "H807")
      (footprint "eagle-import:H807")
      (libsource (lib "eagle-import") (part "H807"))
    )
    (comp (ref "D02")
      (value "M903")
      (footprint "eagle-import:H807")
      (libsource (lib "eagle-import") (part "M903"))
    )
    (comp (ref "D03")
      (value "M903")
      (footprint "eagle-import:H807")
      (libsource (lib "eagle-import") (part "M903"))
    )
    (comp (ref "D04")
      (value "M903")
      (footprint "eagle-import:H807")
      (libsource (lib "eagle-import") (part "M903"))
    )
    (comp (ref "D05")
      (value "M903")
      (footprint "eagle-import:H807")
      (libsource (lib "eagle-import") (part "M903"))
    )
    (comp (ref "D06")
      (value "M903")
      (footprint "eagle-import:H807")
      (libsource (lib "eagle-import") (part "M903"))
    )
    (comp (ref "D19")
      (value "H807")
      (footprint "eagle-import:H807")
      (libsource (lib "eagle-import") (part "H807"))
    )
    (comp (ref "D20")
      (value "H807")
      (footprint "eagle-import:H807")
      (libsource (lib "eagle-import") (part "H807"))
    )
    (comp (ref "D21")
      (value "H807")
      (footprint "eagle-import:H807")
      (libsource (lib "eagle-import") (part "H807"))
    )
    (comp (ref "D22")
      (value "H807")
      (footprint "eagle-import:H807")
      (libsource (lib "eagle-import") (part "H807"))
    )
    (comp (ref "D23")
      (value "H807")
      (footprint "eagle-import:H807")
      (libsource (lib "eagle-import") (part "H807"))
    )
    (comp (ref "D24")
      (value "H807")
      (footprint "eagle-import:H807")
      (libsource (lib "eagle-import") (part "H807"))
    )
    (comp (ref "D25")
      (value "H807")
      (footprint "eagle-import:H807")
      (libsource (lib "eagle-import") (part "H807"))
    )
    (comp (ref "D26")
      (value "H807")
      (footprint "eagle-import:H807")
      (libsource (lib "eagle-import") (part "H807"))
    )
    (comp (ref "D27")
      (value "H807")
      (footprint "eagle-import:H807")
      (libsource (lib "eagle-import") (part "H807"))
    )
    (comp (ref "D28")
      (value "H807")
      (footprint "eagle-import:H807")
      (libsource (lib "eagle-import") (part "H807"))
    )
    (comp (ref "C11")
      (value "M113")
      (footprint "eagle-import:H807")
      (libsource (lib "eagle-import") (part "M113"))
    )
    (comp (ref "C12")
      (value "M115")
      (footprint "eagle-import:H807")
      (libsource (lib "eagle-import") (part "M115"))
    )
    (comp (ref "C13")
      (value "M111")
      (footprint "eagle-import:H807")
      (libsource (lib "eagle-import") (part "M111"))
    )
    (comp (ref "C15")
      (value "M113")
      (footprint "eagle-import:H807")
      (libsource (lib "eagle-import") (part "M113"))
    )
    (comp (ref "D08")
      (value "M207")
      (footprint "eagle-import:H807")
      (libsource (lib "eagle-import") (part "M207"))
    )
    (comp (ref "D09")
      (value "M121")
      (footprint "eagle-import:H807")
      (libsource (lib "eagle-import") (part "M121"))
    )
    (comp (ref "D10")
      (value "M119")
      (footprint "eagle-import:H807")
      (libsource (lib "eagle-import") (part "M119"))
    )
    (comp (ref "D12")
      (value "M627")
      (footprint "eagle-import:H807")
      (libsource (lib "eagle-import") (part "M627"))
    )
    (comp (ref "B06")
      (value "M111")
      (footprint "eagle-import:H807")
      (libsource (lib "eagle-import") (part "M111"))
    )
    (comp (ref "B10")
      (value "M627")
      (footprint "eagle-import:H807")
      (libsource (lib "eagle-import") (part "M627"))
    )
    (comp (ref "B11")
      (value "M115")
      (footprint "eagle-import:H807")
      (libsource (lib "eagle-import") (part "M115"))
    )
    (comp (ref "B12")
      (value "M117")
      (footprint "eagle-import:H807")
      (libsource (lib "eagle-import") (part "M117"))
    )
    (comp (ref "B15")
      (value "M113")
      (footprint "eagle-import:H807")
      (libsource (lib "eagle-import") (part "M113"))
    )
    (comp (ref "C16")
      (value "M627")
      (footprint "eagle-import:H807")
      (libsource (lib "eagle-import") (part "M627"))
    )
    (comp (ref "A18")
      (value "G888")
      (footprint "eagle-import:H807")
      (libsource (lib "eagle-import") (part "G888"))
    )
    (comp (ref "A20")
      (value "G888")
      (footprint "eagle-import:H807")
      (libsource (lib "eagle-import") (part "G888"))
    )
    (comp (ref "A21")
      (value "G888")
      (footprint "eagle-import:H807")
      (libsource (lib "eagle-import") (part "G888"))
    )
    (comp (ref "AB01")
      (value "G821")
      (footprint "eagle-import:H807-2")
      (libsource (lib "eagle-import") (part "G821"))
    )
    (comp (ref "AB19")
      (value "W032")
      (footprint "eagle-import:H807-2")
      (libsource (lib "eagle-import") (part "W032"))
    )
    (comp (ref "B18")
      (value "G888")
      (footprint "eagle-import:H807")
      (libsource (lib "eagle-import") (part "G888"))
    )
    (comp (ref "B20")
      (value "G888")
      (footprint "eagle-import:H807")
      (libsource (lib "eagle-import") (part "G888"))
    )
    (comp (ref "C06")
      (value "M111")
      (footprint "eagle-import:H807")
      (libsource (lib "eagle-import") (part "M111"))
    )
    (comp (ref "C01")
      (value "M101")
      (footprint "eagle-import:H807")
      (libsource (lib "eagle-import") (part "M101"))
    )
    (comp (ref "C04")
      (value "M103")
      (footprint "eagle-import:H807")
      (libsource (lib "eagle-import") (part "M103"))
    )
    (comp (ref "C05")
      (value "M103")
      (footprint "eagle-import:H807")
      (libsource (lib "eagle-import") (part "M103"))
    )
    (comp (ref "D11")
      (value "M206")
      (footprint "eagle-import:H807")
      (libsource (lib "eagle-import") (part "M206X"))
    )
    (comp (ref "D13")
      (value "M602")
      (footprint "eagle-import:H807")
      (libsource (lib "eagle-import") (part "M602"))
    )
    (comp (ref "D17")
      (value "M602")
      (footprint "eagle-import:H807")
      (libsource (lib "eagle-import") (part "M602"))
    )
    (comp (ref "A14")
      (value "M302")
      (footprint "eagle-import:H807")
      (libsource (lib "eagle-import") (part "M302"))
    )
    (comp (ref "A15")
      (value "M627")
      (footprint "eagle-import:H807")
      (libsource (lib "eagle-import") (part "M627"))
    )
    (comp (ref "A16")
      (value "M602")
      (footprint "eagle-import:H807")
      (libsource (lib "eagle-import") (part "M602"))
    )
    (comp (ref "B14")
      (value "M206")
      (footprint "eagle-import:H807")
      (libsource (lib "eagle-import") (part "M206X"))
    )
    (comp (ref "B16")
      (value "M602")
      (footprint "eagle-import:H807")
      (libsource (lib "eagle-import") (part "M602"))
    )
    (comp (ref "D14")
      (value "M307")
      (footprint "eagle-import:H807")
      (libsource (lib "eagle-import") (part "M307"))
    )
    (comp (ref "D15")
      (value "M401")
      (footprint "eagle-import:H807")
      (libsource (lib "eagle-import") (part "M401"))
    )
    (comp (ref "A07")
      (value "M161")
      (footprint "eagle-import:H807")
      (libsource (lib "eagle-import") (part "M161"))
    )
    (comp (ref "A22")
      (value "M502")
      (footprint "eagle-import:H807")
      (libsource (lib "eagle-import") (part "M502"))
    )
    (comp (ref "A23")
      (value "M633")
      (footprint "eagle-import:H807")
      (libsource (lib "eagle-import") (part "M633"))
    )
    (comp (ref "B07")
      (value "M207")
      (footprint "eagle-import:H807")
      (libsource (lib "eagle-import") (part "M207"))
    )
    (comp (ref "B22")
      (value "M633")
      (footprint "eagle-import:H807")
      (libsource (lib "eagle-import") (part "M633"))
    )
    (comp (ref "B23")
      (value "W005")
      (footprint "eagle-import:H807")
      (libsource (lib "eagle-import") (part "W005"))
    )
    (comp (ref "C07")
      (value "M207")
      (footprint "eagle-import:H807")
      (libsource (lib "eagle-import") (part "M207"))
    )
    (comp (ref "D07")
      (value "M161")
      (footprint "eagle-import:H807")
      (libsource (lib "eagle-import") (part "M161"))
    )
    (comp (ref "CD18")
      (value "M228")
      (footprint "eagle-import:H807-2")
      (libsource (lib "eagle-import") (part "M228"))
    )
    (comp (ref "B02")
      (value "M623")
      (footprint "eagle-import:H807")
      (libsource (lib "eagle-import") (part "M623"))
    )
    (comp (ref "B03")
      (value "M623")
      (footprint "eagle-import:H807")
      (libsource (lib "eagle-import") (part "M623"))
    )
    (comp (ref "B04")
      (value "M623")
      (footprint "eagle-import:H807")
      (libsource (lib "eagle-import") (part "M623"))
    )
    (comp (ref "B05")
      (value "M623")
      (footprint "eagle-import:H807")
      (libsource (lib "eagle-import") (part "M623"))
    )
    (comp (ref "C02")
      (value "M101")
      (footprint "eagle-import:H807")
      (libsource (lib "eagle-import") (part "M101-ARRAY"))
    )
    (comp (ref "C03")
      (value "M101")
      (footprint "eagle-import:H807")
      (libsource (lib "eagle-import") (part "M101-ARRAY"))
    )
    (comp (ref "B13")
      (value "M206")
      (footprint "eagle-import:H807")
      (libsource (lib "eagle-import") (part "M206X"))
    )
  )
  (nets
    (net (code "1") (name "+3V@A09U1") (class "Default")
      (node (ref "A07") (pin "S1") (pinfunction "EN2_S1") (pintype "input"))
      (node (ref "A07") (pin "S2") (pinfunction "EN1_S2") (pintype "input"))
      (node (ref "A07") (pin "T2") (pinfunction "EN3_T2") (pintype "input"))
      (node (ref "A08") (pin "D1") (pinfunction "S_D1") (pintype "input"))
      (node (ref "A08") (pin "F2") (pinfunction "S_F2") (pintype "input"))
      (node (ref "A08") (pin "K2") (pinfunction "R_K2") (pintype "input"))
      (node (ref "A09") (pin "U1") (pinfunction "P$1_U1") (pintype "passive"))
      (node (ref "B13") (pin "R1") (pinfunction "S_R1") (pintype "input"))
      (node (ref "B13") (pin "U2") (pinfunction "S_U2") (pintype "input"))
    )
    (net (code "2") (name "+3V@B12U1") (class "Default")
      (node (ref "B12") (pin "U1") (pinfunction "P$1_U1") (pintype "passive"))
      (node (ref "B13") (pin "D1") (pinfunction "S_D1") (pintype "input"))
      (node (ref "B13") (pin "F2") (pinfunction "S_F2") (pintype "input"))
      (node (ref "B13") (pin "K1") (pinfunction "S_K1") (pintype "input"))
      (node (ref "B14") (pin "A1") (pinfunction "R_A1") (pintype "input"))
      (node (ref "B14") (pin "K2") (pinfunction "R_K2") (pintype "input"))
      (node (ref "B14") (pin "N2") (pinfunction "S_N2") (pintype "input"))
      (node (ref "B14") (pin "R1") (pinfunction "S_R1") (pintype "input"))
      (node (ref "B14") (pin "U2") (pinfunction "S_U2") (pintype "input"))
    )
    (net (code "3") (name "+3V@C08U1") (class "Default")
      (node (ref "C01") (pin "C1") (pinfunction "IN2_C1") (pintype "input"))
      (node (ref "C02") (pin "C1") (pinfunction "ENABLE_C1") (pintype "input"))
      (node (ref "C04") (pin "J1") (pinfunction "IN2_J1") (pintype "input"))
      (node (ref "C04") (pin "L2") (pinfunction "L2_L2") (pintype "input"))
      (node (ref "C04") (pin "N2") (pinfunction "N2_N2") (pintype "input"))
      (node (ref "C04") (pin "U2") (pinfunction "U2_U2") (pintype "input"))
      (node (ref "C05") (pin "J1") (pinfunction "IN2_J1") (pintype "input"))
      (node (ref "C05") (pin "L2") (pinfunction "L2_L2") (pintype "input"))
      (node (ref "C05") (pin "N2") (pinfunction "N2_N2") (pintype "input"))
      (node (ref "C05") (pin "U2") (pinfunction "U2_U2") (pintype "input"))
      (node (ref "C08") (pin "U1") (pinfunction "P$1_U1") (pintype "passive"))
    )
    (net (code "4") (name "+3V@C15U1") (class "Default")
      (node (ref "C14") (pin "A1") (pinfunction "R_A1") (pintype "input"))
      (node (ref "C14") (pin "D1") (pinfunction "S_D1") (pintype "input"))
      (node (ref "C14") (pin "F2") (pinfunction "S_F2") (pintype "input"))
      (node (ref "C14") (pin "K1") (pinfunction "S_K1") (pintype "input"))
      (node (ref "C14") (pin "K2") (pinfunction "R_K2") (pintype "input"))
      (node (ref "C15") (pin "U1") (pinfunction "P$1_U1") (pintype "passive"))
      (node (ref "C16") (pin "H2") (pinfunction "IN4_H2") (pintype "input"))
    )
    (net (code "5") (name "+3V@D09U1") (class "Default")
      (node (ref "D07") (pin "S1") (pinfunction "EN2_S1") (pintype "input"))
      (node (ref "D07") (pin "S2") (pinfunction "EN1_S2") (pintype "input"))
      (node (ref "D07") (pin "T2") (pinfunction "EN3_T2") (pintype "input"))
      (node (ref "D09") (pin "U1") (pinfunction "P$1_U1") (pintype "passive"))
    )
    (net (code "6") (name "+3V@D10U1") (class "Default")
      (node (ref "D10") (pin "L2") (pinfunction "IN6_L2") (pintype "input"))
      (node (ref "D10") (pin "M2") (pinfunction "IN7_M2") (pintype "input"))
      (node (ref "D10") (pin "N2") (pinfunction "IN8_N2") (pintype "input"))
      (node (ref "D10") (pin "U1") (pinfunction "P$1_U1") (pintype "passive"))
      (node (ref "D11") (pin "D1") (pinfunction "S_D1") (pintype "input"))
      (node (ref "D11") (pin "F2") (pinfunction "S_F2") (pintype "input"))
      (node (ref "D11") (pin "K1") (pinfunction "S_K1") (pintype "input"))
      (node (ref "D11") (pin "K2") (pinfunction "R_K2") (pintype "input"))
      (node (ref "D14") (pin "M1") (pinfunction "M1_M1") (pintype "input"))
    )
    (net (code "7") (name "+11V") (class "Default")
      (node (ref "AB01") (pin "BM2") (pinfunction "+11V_BM2") (pintype "power_in"))
    )
    (net (code "8") (name "-15V") (class "Default")
      (node (ref "AB01") (pin "AB2") (pinfunction "-15V_AB2") (pintype "power_in"))
      (node (ref "AB01") (pin "AE2") (pinfunction "-15V_AE2") (pintype "power_in"))
      (node (ref "AB01") (pin "AF2") (pinfunction "-15V_AF2") (pintype "power_in"))
    )
    (net (code "9") (name "00") (class "Default")
      (node (ref "A07") (pin "D2") (pinfunction "O0_D2") (pintype "output"))
    )
    (net (code "10") (name "0_TO_DTB") (class "Default")
      (node (ref "A11") (pin "M1") (pinfunction "OUT_M1") (pintype "output"))
      (node (ref "C11") (pin "R1") (pinfunction "IN2_R1") (pintype "input"))
    )
    (net (code "11") (name "0_TO_EF") (class "Default")
      (node (ref "A10") (pin "K2") (pinfunction "OUT_K2") (pintype "output"))
      (node (ref "A11") (pin "E2") (pinfunction "IN_E2") (pintype "input"))
    )
    (net (code "12") (name "0_TO_STA") (class "Default")
      (node (ref "A10") (pin "N2") (pinfunction "OUT_N2") (pintype "output"))
      (node (ref "A11") (pin "N1") (pinfunction "IN_N1") (pintype "input"))
    )
    (net (code "13") (name "01") (class "Default")
      (node (ref "A07") (pin "E2") (pinfunction "O1_E2") (pintype "output"))
    )
    (net (code "14") (name "1_TO_DF") (class "Default")
      (node (ref "A08") (pin "H1") (pinfunction "C_H1") (pintype "input"))
      (node (ref "C12") (pin "J1") (pinfunction "OUT_J1") (pintype "output"))
      (node (ref "C12") (pin "L1") (pinfunction "IN2_L1") (pintype "input"))
      (node (ref "D11") (pin "L2") (pinfunction "C_L2") (pintype "input"))
    )
    (net (code "15") (name "1_TO_DTF") (class "Default")
      (node (ref "B12") (pin "P2") (pinfunction "OUT_P2") (pintype "output"))
      (node (ref "D11") (pin "S2") (pinfunction "C_S2") (pintype "input"))
    )
    (net (code "16") (name "02") (class "Default")
      (node (ref "A07") (pin "J2") (pinfunction "O2_J2") (pintype "output"))
    )
    (net (code "17") (name "03") (class "Default")
      (node (ref "A07") (pin "N2") (pinfunction "O3_N2") (pintype "output"))
    )
    (net (code "18") (name "04") (class "Default")
      (node (ref "A07") (pin "F2") (pinfunction "O4_F2") (pintype "output"))
    )
    (net (code "19") (name "05") (class "Default")
      (node (ref "A07") (pin "M2") (pinfunction "O5_M2") (pintype "output"))
    )
    (net (code "20") (name "06") (class "Default")
      (node (ref "A07") (pin "H2") (pinfunction "O6_H2") (pintype "output"))
    )
    (net (code "21") (name "07") (class "Default")
      (node (ref "A07") (pin "L2") (pinfunction "O7_L2") (pintype "output"))
    )
    (net (code "22") (name "76") (class "Default")
      (node (ref "C04") (pin "V2") (pinfunction "V2_V2") (pintype "output"))
      (node (ref "C06") (pin "S2") (pinfunction "IN_S2") (pintype "input"))
    )
    (net (code "23") (name "76+77") (class "Default")
      (node (ref "C03") (pin "C1") (pinfunction "ENABLE_C1") (pintype "input"))
      (node (ref "D12") (pin "V2") (pinfunction "OUT_V2") (pintype "output"))
    )
    (net (code "24") (name "77") (class "Default")
      (node (ref "C05") (pin "V2") (pinfunction "V2_V2") (pintype "output"))
      (node (ref "C06") (pin "U2") (pinfunction "IN_U2") (pintype "input"))
    )
    (net (code "25") (name "ADDR_ACC") (class "Default")
      (node (ref "C02") (pin "V2") (pinfunction "O15_V2") (pintype "output"))
      (node (ref "C17") (pin "N1") (pinfunction "IN_N1") (pintype "input"))
    )
    (net (code "26") (name "B-BRK") (class "Default")
      (node (ref "B10") (pin "R2") (pinfunction "IN1_R2") (pintype "input"))
      (node (ref "B10") (pin "S2") (pinfunction "IN2_S2") (pintype "input"))
      (node (ref "B10") (pin "T2") (pinfunction "IN3_T2") (pintype "input"))
      (node (ref "B10") (pin "U2") (pinfunction "IN4_U2") (pintype "input"))
      (node (ref "C01") (pin "E1") (pinfunction "OUT_E1") (pintype "output"))
      (node (ref "D12") (pin "M1") (pinfunction "IN1_M1") (pintype "input"))
    )
    (net (code "27") (name "B-RUN") (class "Default")
      (node (ref "B11") (pin "N2") (pinfunction "IN1_N2") (pintype "input"))
      (node (ref "C01") (pin "B1") (pinfunction "OUT_B1") (pintype "output"))
    )
    (net (code "28") (name "B-XSTA") (class "Default")
      (node (ref "A10") (pin "E2") (pinfunction "IN2_E2") (pintype "input"))
      (node (ref "C11") (pin "P2") (pinfunction "IN1_P2") (pintype "input"))
      (node (ref "D12") (pin "E1") (pinfunction "OUT_E1") (pintype "output"))
    )
    (net (code "29") (name "BAC_00") (class "Default")
      (node (ref "B06") (pin "B1") (pinfunction "OUT_B1") (pintype "output"))
      (node (ref "B07") (pin "C1") (pinfunction "C1_C1") (pintype "input"))
      (node (ref "B07") (pin "D1") (pinfunction "D1_D1") (pintype "input"))
    )
    (net (code "30") (name "BAC_01") (class "Default")
      (node (ref "B06") (pin "E1") (pinfunction "OUT_E1") (pintype "output"))
      (node (ref "B07") (pin "E2") (pinfunction "E2_E2") (pintype "input"))
      (node (ref "B07") (pin "F2") (pinfunction "F2_F2") (pintype "input"))
    )
    (net (code "31") (name "BAC_02") (class "Default")
      (node (ref "B06") (pin "H1") (pinfunction "OUT_H1") (pintype "output"))
      (node (ref "B07") (pin "J1") (pinfunction "J1_J1") (pintype "input"))
      (node (ref "B07") (pin "K1") (pinfunction "K1_K1") (pintype "input"))
    )
    (net (code "32") (name "BAC_03") (class "Default")
      (node (ref "B06") (pin "K1") (pinfunction "OUT_K1") (pintype "output"))
      (node (ref "B07") (pin "M2") (pinfunction "M2_M2") (pintype "input"))
      (node (ref "B07") (pin "N2") (pinfunction "N2_N2") (pintype "input"))
    )
    (net (code "33") (name "BAC_04") (class "Default")
      (node (ref "B06") (pin "M1") (pinfunction "OUT_M1") (pintype "output"))
      (node (ref "C07") (pin "M2") (pinfunction "M2_M2") (pintype "input"))
      (node (ref "C07") (pin "N2") (pinfunction "N2_N2") (pintype "input"))
    )
    (net (code "34") (name "BAC_05") (class "Default")
      (node (ref "B06") (pin "P1") (pinfunction "OUT_P1") (pintype "output"))
      (node (ref "B07") (pin "P1") (pinfunction "P1_P1") (pintype "input"))
      (node (ref "B07") (pin "R1") (pinfunction "R1_R1") (pintype "input"))
    )
    (net (code "35") (name "BAC_06") (class "Default")
      (node (ref "B06") (pin "S1") (pinfunction "OUT_S1") (pintype "output"))
      (node (ref "B07") (pin "T2") (pinfunction "T2_T2") (pintype "input"))
      (node (ref "B07") (pin "U2") (pinfunction "U2_U2") (pintype "input"))
      (node (ref "D11") (pin "C1") (pinfunction "D_C1") (pintype "input"))
    )
    (net (code "36") (name "BAC_07") (class "Default")
      (node (ref "B06") (pin "U1") (pinfunction "OUT_U1") (pintype "output"))
      (node (ref "C07") (pin "C1") (pinfunction "C1_C1") (pintype "input"))
      (node (ref "C07") (pin "D1") (pinfunction "D1_D1") (pintype "input"))
      (node (ref "D11") (pin "E2") (pinfunction "D_E2") (pintype "input"))
    )
    (net (code "37") (name "BAC_08") (class "Default")
      (node (ref "B06") (pin "D2") (pinfunction "OUT_D2") (pintype "output"))
      (node (ref "C07") (pin "E2") (pinfunction "E2_E2") (pintype "input"))
      (node (ref "C07") (pin "F2") (pinfunction "F2_F2") (pintype "input"))
      (node (ref "D11") (pin "J1") (pinfunction "D_J1") (pintype "input"))
    )
    (net (code "38") (name "BAC_09") (class "Default")
      (node (ref "B06") (pin "F2") (pinfunction "OUT_F2") (pintype "output"))
      (node (ref "C07") (pin "J1") (pinfunction "J1_J1") (pintype "input"))
      (node (ref "C07") (pin "K1") (pinfunction "K1_K1") (pintype "input"))
    )
    (net (code "39") (name "BAC_10") (class "Default")
      (node (ref "B06") (pin "J2") (pinfunction "OUT_J2") (pintype "output"))
    )
    (net (code "40") (name "BAC_11") (class "Default")
      (node (ref "B06") (pin "L2") (pinfunction "OUT_L2") (pintype "output"))
    )
    (net (code "41") (name "BLK_IN_SYNC") (class "Default")
      (node (ref "C11") (pin "E2") (pinfunction "IN2_E2") (pintype "input"))
      (node (ref "C13") (pin "S1") (pinfunction "OUT_S1") (pintype "output"))
      (node (ref "CD18") (pin "AP2") (pinfunction "AP2_AP2") (pintype "input"))
    )
    (net (code "42") (name "BMB_00") (class "Default")
      (node (ref "C06") (pin "B1") (pinfunction "OUT_B1") (pintype "output"))
      (node (ref "C08") (pin "B1") (pinfunction "IN1B_B1") (pintype "input"))
    )
    (net (code "43") (name "BMB_01") (class "Default")
      (node (ref "C06") (pin "E1") (pinfunction "OUT_E1") (pintype "output"))
      (node (ref "C08") (pin "H1") (pinfunction "IN1B_H1") (pintype "input"))
    )
    (net (code "44") (name "BMB_02") (class "Default")
      (node (ref "C06") (pin "H1") (pinfunction "OUT_H1") (pintype "output"))
      (node (ref "C08") (pin "N1") (pinfunction "IN1B_N1") (pintype "input"))
    )
    (net (code "45") (name "BMB_03") (class "Default")
      (node (ref "C06") (pin "K1") (pinfunction "OUT_K1") (pintype "output"))
      (node (ref "C08") (pin "E2") (pinfunction "IN1B_E2") (pintype "input"))
    )
    (net (code "46") (name "BMB_04") (class "Default")
      (node (ref "C06") (pin "M1") (pinfunction "OUT_M1") (pintype "output"))
      (node (ref "C08") (pin "L2") (pinfunction "IN1B_L2") (pintype "input"))
    )
    (net (code "47") (name "BMB_05") (class "Default")
      (node (ref "C06") (pin "P1") (pinfunction "OUT_P1") (pintype "output"))
      (node (ref "C08") (pin "S2") (pinfunction "IN1B_S2") (pintype "input"))
    )
    (net (code "48") (name "BMB_06") (class "Default")
      (node (ref "B08") (pin "B1") (pinfunction "IN2_B1") (pintype "input"))
      (node (ref "C06") (pin "S1") (pinfunction "OUT_S1") (pintype "output"))
    )
    (net (code "49") (name "BMB_07") (class "Default")
      (node (ref "B08") (pin "E1") (pinfunction "IN2_E1") (pintype "input"))
      (node (ref "C06") (pin "U1") (pinfunction "OUT_U1") (pintype "output"))
    )
    (net (code "50") (name "BMB_08") (class "Default")
      (node (ref "B08") (pin "E2") (pinfunction "IN2_E2") (pintype "input"))
      (node (ref "C06") (pin "D2") (pinfunction "OUT_D2") (pintype "output"))
    )
    (net (code "51") (name "BMB_09") (class "Default")
      (node (ref "B08") (pin "M1") (pinfunction "IN2_M1") (pintype "input"))
      (node (ref "C06") (pin "F2") (pinfunction "OUT_F2") (pintype "output"))
    )
    (net (code "52") (name "BMB_10") (class "Default")
      (node (ref "B08") (pin "R1") (pinfunction "IN2_R1") (pintype "input"))
      (node (ref "C06") (pin "J2") (pinfunction "OUT_J2") (pintype "output"))
    )
    (net (code "53") (name "BMB_11") (class "Default")
      (node (ref "B08") (pin "J1") (pinfunction "IN2_J1") (pintype "input"))
      (node (ref "C06") (pin "L2") (pinfunction "OUT_L2") (pintype "output"))
    )
    (net (code "54") (name "BMB_TO_DTB") (class "Default")
      (node (ref "B08") (pin "A1") (pinfunction "IN1_A1") (pintype "input"))
      (node (ref "B08") (pin "D1") (pinfunction "IN1_D1") (pintype "input"))
      (node (ref "B08") (pin "D2") (pinfunction "IN1_D2") (pintype "input"))
      (node (ref "B08") (pin "H1") (pinfunction "IN1_H1") (pintype "input"))
      (node (ref "B08") (pin "L1") (pinfunction "IN1_L1") (pintype "input"))
      (node (ref "B08") (pin "P1") (pinfunction "IN1_P1") (pintype "input"))
      (node (ref "C08") (pin "A1") (pinfunction "IN1A_A1") (pintype "input"))
      (node (ref "C08") (pin "D2") (pinfunction "IN1A_D2") (pintype "input"))
      (node (ref "C08") (pin "F1") (pinfunction "IN1A_F1") (pintype "input"))
      (node (ref "C08") (pin "K2") (pinfunction "IN1A_K2") (pintype "input"))
      (node (ref "C08") (pin "M1") (pinfunction "IN1A_M1") (pintype "input"))
      (node (ref "C08") (pin "R2") (pinfunction "IN1A_R2") (pintype "input"))
      (node (ref "D12") (pin "L1") (pinfunction "OUT_L1") (pintype "output"))
    )
    (net (code "55") (name "BMR00") (class "Default")
      (node (ref "A23") (pin "F1") (pinfunction "A_F1") (pintype "input"))
      (node (ref "B14") (pin "P2") (pinfunction "1_P2") (pintype "output"))
    )
    (net (code "56") (name "BMR01") (class "Default")
      (node (ref "A23") (pin "B1") (pinfunction "B_B1") (pintype "input"))
      (node (ref "B14") (pin "F1") (pinfunction "0_F1") (pintype "output"))
    )
    (net (code "57") (name "C00") (class "Default")
      (node (ref "A12") (pin "L2") (pinfunction "IN1_L2") (pintype "input"))
      (node (ref "A26") (pin "E2") (pinfunction "P$2_E2") (pintype "bidirectional"))
      (node (ref "B12") (pin "R2") (pinfunction "IN1_R2") (pintype "input"))
      (node (ref "B13") (pin "S1") (pinfunction "1_S1") (pintype "output"))
      (node (ref "C15") (pin "E2") (pinfunction "IN2_E2") (pintype "input"))
      (node (ref "D10") (pin "C1") (pinfunction "IN3_C1") (pintype "input"))
    )
    (net (code "58") (name "C01") (class "Default")
      (node (ref "A12") (pin "M2") (pinfunction "IN2_M2") (pintype "input"))
      (node (ref "A26") (pin "F2") (pinfunction "P$2_F2") (pintype "bidirectional"))
      (node (ref "B10") (pin "J1") (pinfunction "IN3_J1") (pintype "input"))
      (node (ref "B11") (pin "V2") (pinfunction "IN3_V2") (pintype "input"))
      (node (ref "B13") (pin "P2") (pinfunction "1_P2") (pintype "output"))
    )
    (net (code "59") (name "CK00") (class "Default")
      (node (ref "A18") (pin "P2") (pinfunction "P2_P2") (pintype "input"))
      (node (ref "B14") (pin "S1") (pinfunction "1_S1") (pintype "output"))
    )
    (net (code "60") (name "CK01") (class "Default")
      (node (ref "B14") (pin "P1") (pinfunction "D_P1") (pintype "input"))
      (node (ref "B14") (pin "V2") (pinfunction "1_V2") (pintype "output"))
      (node (ref "C16") (pin "N1") (pinfunction "IN2_N1") (pintype "input"))
      (node (ref "C16") (pin "P1") (pinfunction "IN3_P1") (pintype "input"))
      (node (ref "C16") (pin "R1") (pinfunction "IN4_R1") (pintype "input"))
    )
    (net (code "61") (name "COMP+SH") (class "Default")
      (node (ref "A12") (pin "D2") (pinfunction "IN1_D2") (pintype "input"))
      (node (ref "C14") (pin "B1") (pinfunction "C_B1") (pintype "input"))
      (node (ref "C14") (pin "D2") (pinfunction "C_D2") (pintype "input"))
      (node (ref "C14") (pin "H1") (pinfunction "C_H1") (pintype "input"))
      (node (ref "C15") (pin "K1") (pinfunction "OUT_K1") (pintype "output"))
    )
    (net (code "62") (name "CSTA") (class "Default")
      (node (ref "C04") (pin "C1") (pinfunction "C1_C1") (pintype "output"))
      (node (ref "D16") (pin "P2") (pinfunction "K2_P2") (pintype "input"))
    )
    (net (code "63") (name "DATA") (class "Default")
      (node (ref "A26") (pin "M1") (pinfunction "P$2_M1") (pintype "bidirectional"))
      (node (ref "C13") (pin "F1") (pinfunction "IN_F1") (pintype "input"))
      (node (ref "CD18") (pin "BK2") (pinfunction "BK2_BK2") (pintype "output"))
    )
    (net (code "64") (name "DF") (class "Default")
      (node (ref "A10") (pin "P2") (pinfunction "IN1_P2") (pintype "input"))
      (node (ref "A26") (pin "E1") (pinfunction "P$2_E1") (pintype "bidirectional"))
      (node (ref "D11") (pin "R2") (pinfunction "0_R2") (pintype "output"))
    )
    (net (code "65") (name "DTB_00") (class "Default")
      (node (ref "A25") (pin "A2") (pinfunction "P$2_A2") (pintype "bidirectional"))
      (node (ref "C09") (pin "E1") (pinfunction "1_E1") (pintype "output"))
      (node (ref "C10") (pin "B1") (pinfunction "IN1B_B1") (pintype "input"))
      (node (ref "D09") (pin "D2") (pinfunction "IN1A_D2") (pintype "input"))
    )
    (net (code "66") (name "DTB_01") (class "Default")
      (node (ref "A25") (pin "B2") (pinfunction "P$2_B2") (pintype "bidirectional"))
      (node (ref "C09") (pin "H2") (pinfunction "1_H2") (pintype "output"))
      (node (ref "C10") (pin "H1") (pinfunction "IN1B_H1") (pintype "input"))
      (node (ref "D09") (pin "K2") (pinfunction "IN1A_K2") (pintype "input"))
    )
    (net (code "67") (name "DTB_02") (class "Default")
      (node (ref "A25") (pin "C2") (pinfunction "P$2_C2") (pintype "bidirectional"))
      (node (ref "C09") (pin "L1") (pinfunction "1_L1") (pintype "output"))
      (node (ref "C10") (pin "N1") (pinfunction "IN1B_N1") (pintype "input"))
      (node (ref "D09") (pin "R2") (pinfunction "IN1A_R2") (pintype "input"))
    )
    (net (code "68") (name "DTB_03") (class "Default")
      (node (ref "A25") (pin "D2") (pinfunction "P$2_D2") (pintype "bidirectional"))
      (node (ref "C09") (pin "C1") (pinfunction "D_C1") (pintype "input"))
      (node (ref "C09") (pin "P2") (pinfunction "1_P2") (pintype "output"))
    )
    (net (code "69") (name "DTB_04") (class "Default")
      (node (ref "A25") (pin "E2") (pinfunction "P$2_E2") (pintype "bidirectional"))
      (node (ref "C09") (pin "E2") (pinfunction "D_E2") (pintype "input"))
      (node (ref "C09") (pin "S1") (pinfunction "1_S1") (pintype "output"))
    )
    (net (code "70") (name "DTB_05") (class "Default")
      (node (ref "A25") (pin "F2") (pinfunction "P$2_F2") (pintype "bidirectional"))
      (node (ref "C09") (pin "J1") (pinfunction "D_J1") (pintype "input"))
      (node (ref "C09") (pin "V2") (pinfunction "1_V2") (pintype "output"))
    )
    (net (code "71") (name "DTB_06") (class "Default")
      (node (ref "A25") (pin "H2") (pinfunction "P$2_H2") (pintype "bidirectional"))
      (node (ref "B09") (pin "E1") (pinfunction "1_E1") (pintype "output"))
      (node (ref "C09") (pin "M2") (pinfunction "D_M2") (pintype "input"))
    )
    (net (code "72") (name "DTB_07") (class "Default")
      (node (ref "A25") (pin "J2") (pinfunction "P$2_J2") (pintype "bidirectional"))
      (node (ref "B09") (pin "V2") (pinfunction "1_V2") (pintype "output"))
      (node (ref "C09") (pin "P1") (pinfunction "D_P1") (pintype "input"))
    )
    (net (code "73") (name "DTB_08") (class "Default")
      (node (ref "A25") (pin "K2") (pinfunction "P$2_K2") (pintype "bidirectional"))
      (node (ref "B09") (pin "L1") (pinfunction "1_L1") (pintype "output"))
      (node (ref "C09") (pin "T2") (pinfunction "D_T2") (pintype "input"))
    )
    (net (code "74") (name "DTB_09") (class "Default")
      (node (ref "A25") (pin "L2") (pinfunction "P$2_L2") (pintype "bidirectional"))
      (node (ref "B09") (pin "C1") (pinfunction "D_C1") (pintype "input"))
      (node (ref "B09") (pin "P2") (pinfunction "1_P2") (pintype "output"))
    )
    (net (code "75") (name "DTB_10") (class "Default")
      (node (ref "A25") (pin "M2") (pinfunction "P$2_M2") (pintype "bidirectional"))
      (node (ref "B09") (pin "S1") (pinfunction "1_S1") (pintype "output"))
      (node (ref "B09") (pin "T2") (pinfunction "D_T2") (pintype "input"))
    )
    (net (code "76") (name "DTB_11") (class "Default")
      (node (ref "A25") (pin "N2") (pinfunction "P$2_N2") (pintype "bidirectional"))
      (node (ref "B09") (pin "H2") (pinfunction "1_H2") (pintype "output"))
      (node (ref "B09") (pin "J1") (pinfunction "D_J1") (pintype "input"))
    )
    (net (code "77") (name "DTF") (class "Default")
      (node (ref "A08") (pin "J1") (pinfunction "D_J1") (pintype "input"))
      (node (ref "A26") (pin "C1") (pinfunction "P$2_C1") (pintype "bidirectional"))
      (node (ref "D11") (pin "V1") (pinfunction "0_V1") (pintype "output"))
    )
    (net (code "78") (name "DTSF") (class "Default")
      (node (ref "A12") (pin "R1") (pinfunction "IN2_R1") (pintype "input"))
      (node (ref "C05") (pin "A1") (pinfunction "A1_A1") (pintype "output"))
    )
    (net (code "79") (name "EF") (class "Default")
      (node (ref "A11") (pin "J1") (pinfunction "IN_J1") (pintype "input"))
      (node (ref "A12") (pin "F1") (pinfunction "OUT_F1") (pintype "output"))
      (node (ref "A25") (pin "N1") (pinfunction "P$2_N1") (pintype "bidirectional"))
    )
    (net (code "80") (name "END") (class "Default")
      (node (ref "A08") (pin "E1") (pinfunction "1_E1") (pintype "output"))
      (node (ref "A25") (pin "R1") (pinfunction "P$2_R1") (pintype "bidirectional"))
    )
    (net (code "81") (name "ENI") (class "Default")
      (node (ref "A12") (pin "H1") (pinfunction "IN1_H1") (pintype "input"))
      (node (ref "A25") (pin "L1") (pinfunction "P$2_L1") (pintype "bidirectional"))
      (node (ref "C07") (pin "L1") (pinfunction "L1_L1") (pintype "output"))
    )
    (net (code "82") (name "FR_00") (class "Default")
      (node (ref "A25") (pin "F1") (pinfunction "P$2_F1") (pintype "bidirectional"))
      (node (ref "B07") (pin "S1") (pinfunction "S1_S1") (pintype "output"))
      (node (ref "B12") (pin "E2") (pinfunction "IN2_E2") (pintype "input"))
      (node (ref "C12") (pin "U2") (pinfunction "IN2_U2") (pintype "input"))
    )
    (net (code "83") (name "FR_01") (class "Default")
      (node (ref "A10") (pin "H1") (pinfunction "IN1_H1") (pintype "input"))
      (node (ref "A25") (pin "H1") (pinfunction "P$2_H1") (pintype "bidirectional"))
      (node (ref "B07") (pin "V2") (pinfunction "V2_V2") (pintype "output"))
      (node (ref "B15") (pin "M1") (pinfunction "IN2_M1") (pintype "input"))
      (node (ref "C15") (pin "D1") (pinfunction "IN1_D1") (pintype "input"))
      (node (ref "D07") (pin "V2") (pinfunction "IN2_V2") (pintype "input"))
      (node (ref "D12") (pin "R1") (pinfunction "IN4_R1") (pintype "input"))
    )
    (net (code "84") (name "FR_02") (class "Default")
      (node (ref "A25") (pin "J1") (pinfunction "P$2_J1") (pintype "bidirectional"))
      (node (ref "C07") (pin "E1") (pinfunction "E1_E1") (pintype "output"))
      (node (ref "D07") (pin "U2") (pinfunction "IN1_U2") (pintype "input"))
    )
    (net (code "85") (name "FR_03") (class "Default")
      (node (ref "A25") (pin "K1") (pinfunction "P$2_K1") (pintype "bidirectional"))
      (node (ref "B15") (pin "R2") (pinfunction "IN2_R2") (pintype "input"))
      (node (ref "C07") (pin "H2") (pinfunction "H2_H2") (pintype "output"))
      (node (ref "D07") (pin "V1") (pinfunction "IN0_V1") (pintype "input"))
    )
    (net (code "86") (name "GND") (class "Default")
      (node (ref "A05") (pin "B1") (pinfunction "P$2_B1") (pintype "bidirectional"))
      (node (ref "A05") (pin "D1") (pinfunction "P$2_D1") (pintype "bidirectional"))
      (node (ref "A05") (pin "D2") (pinfunction "P$2_D2") (pintype "bidirectional"))
      (node (ref "A05") (pin "E1") (pinfunction "P$2_E1") (pintype "bidirectional"))
      (node (ref "A05") (pin "H1") (pinfunction "P$2_H1") (pintype "bidirectional"))
      (node (ref "A05") (pin "J1") (pinfunction "P$2_J1") (pintype "bidirectional"))
      (node (ref "A05") (pin "L1") (pinfunction "P$2_L1") (pintype "bidirectional"))
      (node (ref "A05") (pin "M1") (pinfunction "P$2_M1") (pintype "bidirectional"))
      (node (ref "A05") (pin "P1") (pinfunction "P$2_P1") (pintype "bidirectional"))
      (node (ref "A05") (pin "S1") (pinfunction "P$2_S1") (pintype "bidirectional"))
      (node (ref "A06") (pin "K2") (pinfunction "P$2_K2") (pintype "bidirectional"))
      (node (ref "A07") (pin "U1") (pinfunction "IN*_U1") (pintype "input"))
      (node (ref "A08") (pin "T2") (pinfunction "D_T2") (pintype "input"))
      (node (ref "A23") (pin "C1") (pinfunction "C_C1") (pintype "input"))
      (node (ref "A23") (pin "F2") (pinfunction "C_F2") (pintype "input"))
      (node (ref "A23") (pin "J1") (pinfunction "C_J1") (pintype "input"))
      (node (ref "A23") (pin "M2") (pinfunction "C_M2") (pintype "input"))
      (node (ref "A23") (pin "P1") (pinfunction "C_P1") (pintype "input"))
      (node (ref "A23") (pin "T2") (pinfunction "C_T2") (pintype "input"))
      (node (ref "A25") (pin "M1") (pinfunction "P$2_M1") (pintype "bidirectional"))
      (node (ref "A26") (pin "D2") (pinfunction "P$2_D2") (pintype "bidirectional"))
      (node (ref "A26") (pin "U2") (pinfunction "P$2_U2") (pintype "bidirectional"))
      (node (ref "A26") (pin "V1") (pinfunction "P$2_V1") (pintype "bidirectional"))
      (node (ref "AB01") (pin "AC2") (pinfunction "GND_AC2") (pintype "power_in"))
      (node (ref "AB01") (pin "AH2") (pinfunction "GND_AH2") (pintype "power_in"))
      (node (ref "AB01") (pin "AK2") (pinfunction "GND_AK2") (pintype "power_in"))
      (node (ref "AB01") (pin "AL2") (pinfunction "GND_AL2") (pintype "power_in"))
      (node (ref "AB01") (pin "AT1") (pinfunction "GND_AT1") (pintype "power_in"))
      (node (ref "AB01") (pin "BC2") (pinfunction "GND_BC2") (pintype "power_in"))
      (node (ref "AB01") (pin "BD2") (pinfunction "GND_BD2") (pintype "power_in"))
      (node (ref "AB01") (pin "BH2") (pinfunction "GND_BH2") (pintype "power_in"))
      (node (ref "AB01") (pin "BK2") (pinfunction "GND_BK2") (pintype "power_in"))
      (node (ref "AB01") (pin "BL2") (pinfunction "GND_BL2") (pintype "power_in"))
      (node (ref "AB01") (pin "BT1") (pinfunction "GND_BT1") (pintype "power_in"))
      (node (ref "AB19") (pin "AJ2") (pinfunction "P$2_AJ2") (pintype "bidirectional"))
      (node (ref "AB19") (pin "AR2") (pinfunction "P$2_AR2") (pintype "bidirectional"))
      (node (ref "AB19") (pin "AU2") (pinfunction "P$2_AU2") (pintype "bidirectional"))
      (node (ref "AB19") (pin "BF2") (pinfunction "P$2_BF2") (pintype "bidirectional"))
      (node (ref "AB19") (pin "BM2") (pinfunction "P$2_BM2") (pintype "bidirectional"))
      (node (ref "B05") (pin "C1") (pinfunction "C_C1") (pintype "input"))
      (node (ref "B05") (pin "F2") (pinfunction "C_F2") (pintype "input"))
      (node (ref "B05") (pin "J1") (pinfunction "C_J1") (pintype "input"))
      (node (ref "B05") (pin "M2") (pinfunction "C_M2") (pintype "input"))
      (node (ref "B05") (pin "P1") (pinfunction "C_P1") (pintype "input"))
      (node (ref "B22") (pin "T2") (pinfunction "C_T2") (pintype "input"))
      (node (ref "D05") (pin "B1") (pinfunction "P$2_B1") (pintype "bidirectional"))
      (node (ref "D05") (pin "D1") (pinfunction "P$2_D1") (pintype "bidirectional"))
      (node (ref "D05") (pin "D2") (pinfunction "P$2_D2") (pintype "bidirectional"))
      (node (ref "D05") (pin "E1") (pinfunction "P$2_E1") (pintype "bidirectional"))
      (node (ref "D05") (pin "H1") (pinfunction "P$2_H1") (pintype "bidirectional"))
      (node (ref "D05") (pin "J1") (pinfunction "P$2_J1") (pintype "bidirectional"))
      (node (ref "D05") (pin "L1") (pinfunction "P$2_L1") (pintype "bidirectional"))
      (node (ref "D05") (pin "M1") (pinfunction "P$2_M1") (pintype "bidirectional"))
      (node (ref "D05") (pin "P1") (pinfunction "P$2_P1") (pintype "bidirectional"))
      (node (ref "D05") (pin "S1") (pinfunction "P$2_S1") (pintype "bidirectional"))
      (node (ref "D06") (pin "K2") (pinfunction "P$2_K2") (pintype "bidirectional"))
      (node (ref "D07") (pin "U1") (pinfunction "IN*_U1") (pintype "input"))
      (node (ref "D11") (pin "P1") (pinfunction "D_P1") (pintype "input"))
      (node (ref "D11") (pin "T2") (pinfunction "D_T2") (pintype "input"))
    )
    (net (code "87") (name "IOP_1") (class "Default")
      (node (ref "A02") (pin "K2") (pinfunction "P$2_K2") (pintype "bidirectional"))
      (node (ref "C04") (pin "P2") (pinfunction "P2_P2") (pintype "input"))
      (node (ref "C05") (pin "P2") (pinfunction "P2_P2") (pintype "input"))
      (node (ref "D02") (pin "K2") (pinfunction "P$2_K2") (pintype "bidirectional"))
    )
    (net (code "88") (name "IOP_2") (class "Default")
      (node (ref "A02") (pin "M2") (pinfunction "P$2_M2") (pintype "bidirectional"))
      (node (ref "C04") (pin "R2") (pinfunction "R2_R2") (pintype "input"))
      (node (ref "C05") (pin "R2") (pinfunction "R2_R2") (pintype "input"))
      (node (ref "D02") (pin "M2") (pinfunction "P$2_M2") (pintype "bidirectional"))
    )
    (net (code "89") (name "IOP_4") (class "Default")
      (node (ref "A02") (pin "P2") (pinfunction "P$2_P2") (pintype "bidirectional"))
      (node (ref "C04") (pin "S2") (pinfunction "S2_S2") (pintype "input"))
      (node (ref "C05") (pin "S2") (pinfunction "S2_S2") (pintype "input"))
      (node (ref "D02") (pin "P2") (pinfunction "P$2_P2") (pintype "bidirectional"))
    )
    (net (code "90") (name "I{slash}O_B-BRK") (class "Default")
      (node (ref "A05") (pin "P2") (pinfunction "P$2_P2") (pintype "bidirectional"))
      (node (ref "C01") (pin "D1") (pinfunction "IN_D1") (pintype "input"))
      (node (ref "D05") (pin "P2") (pinfunction "P$2_P2") (pintype "bidirectional"))
    )
    (net (code "91") (name "I{slash}O_B-RUN") (class "Default")
      (node (ref "A04") (pin "S2") (pinfunction "P$2_S2") (pintype "bidirectional"))
      (node (ref "C01") (pin "A1") (pinfunction "IN1_A1") (pintype "input"))
      (node (ref "D04") (pin "S2") (pinfunction "P$2_S2") (pintype "bidirectional"))
    )
    (net (code "92") (name "I{slash}O_BAC_00") (class "Default")
      (node (ref "A02") (pin "B1") (pinfunction "P$2_B1") (pintype "bidirectional"))
      (node (ref "C03") (pin "A1") (pinfunction "IN1_A1") (pintype "input"))
      (node (ref "D02") (pin "B1") (pinfunction "P$2_B1") (pintype "bidirectional"))
    )
    (net (code "93") (name "I{slash}O_BAC_01") (class "Default")
      (node (ref "A02") (pin "D1") (pinfunction "P$2_D1") (pintype "bidirectional"))
      (node (ref "C03") (pin "D1") (pinfunction "IN2_D1") (pintype "input"))
      (node (ref "D02") (pin "D1") (pinfunction "P$2_D1") (pintype "bidirectional"))
    )
    (net (code "94") (name "I{slash}O_BAC_02") (class "Default")
      (node (ref "A02") (pin "E1") (pinfunction "P$2_E1") (pintype "bidirectional"))
      (node (ref "C03") (pin "F1") (pinfunction "IN3_F1") (pintype "input"))
      (node (ref "D02") (pin "E1") (pinfunction "P$2_E1") (pintype "bidirectional"))
    )
    (net (code "95") (name "I{slash}O_BAC_03") (class "Default")
      (node (ref "A02") (pin "H1") (pinfunction "P$2_H1") (pintype "bidirectional"))
      (node (ref "C03") (pin "J1") (pinfunction "IN4_J1") (pintype "input"))
      (node (ref "D02") (pin "H1") (pinfunction "P$2_H1") (pintype "bidirectional"))
    )
    (net (code "96") (name "I{slash}O_BAC_04") (class "Default")
      (node (ref "A02") (pin "J1") (pinfunction "P$2_J1") (pintype "bidirectional"))
      (node (ref "C03") (pin "L1") (pinfunction "IN5_L1") (pintype "input"))
      (node (ref "D02") (pin "J1") (pinfunction "P$2_J1") (pintype "bidirectional"))
    )
    (net (code "97") (name "I{slash}O_BAC_05") (class "Default")
      (node (ref "A02") (pin "L1") (pinfunction "P$2_L1") (pintype "bidirectional"))
      (node (ref "C03") (pin "N1") (pinfunction "IN6_N1") (pintype "input"))
      (node (ref "D02") (pin "L1") (pinfunction "P$2_L1") (pintype "bidirectional"))
    )
    (net (code "98") (name "I{slash}O_BAC_06") (class "Default")
      (node (ref "A02") (pin "M1") (pinfunction "P$2_M1") (pintype "bidirectional"))
      (node (ref "C03") (pin "R1") (pinfunction "IN7_R1") (pintype "input"))
      (node (ref "D02") (pin "M1") (pinfunction "P$2_M1") (pintype "bidirectional"))
    )
    (net (code "99") (name "I{slash}O_BAC_07") (class "Default")
      (node (ref "A02") (pin "P1") (pinfunction "P$2_P1") (pintype "bidirectional"))
      (node (ref "C03") (pin "V1") (pinfunction "IN8_V1") (pintype "input"))
      (node (ref "D02") (pin "P1") (pinfunction "P$2_P1") (pintype "bidirectional"))
    )
    (net (code "100") (name "I{slash}O_BAC_08") (class "Default")
      (node (ref "A02") (pin "S1") (pinfunction "P$2_S1") (pintype "bidirectional"))
      (node (ref "C03") (pin "E2") (pinfunction "IN9_E2") (pintype "input"))
      (node (ref "D02") (pin "S1") (pinfunction "P$2_S1") (pintype "bidirectional"))
    )
    (net (code "101") (name "I{slash}O_BAC_09") (class "Default")
      (node (ref "A02") (pin "D2") (pinfunction "P$2_D2") (pintype "bidirectional"))
      (node (ref "C03") (pin "H2") (pinfunction "IN10_H2") (pintype "input"))
      (node (ref "D02") (pin "D2") (pinfunction "P$2_D2") (pintype "bidirectional"))
    )
    (net (code "102") (name "I{slash}O_BAC_10") (class "Default")
      (node (ref "A02") (pin "E2") (pinfunction "P$2_E2") (pintype "bidirectional"))
      (node (ref "C03") (pin "K2") (pinfunction "IN11_K2") (pintype "input"))
      (node (ref "D02") (pin "E2") (pinfunction "P$2_E2") (pintype "bidirectional"))
    )
    (net (code "103") (name "I{slash}O_BAC_11") (class "Default")
      (node (ref "A02") (pin "H2") (pinfunction "P$2_H2") (pintype "bidirectional"))
      (node (ref "C03") (pin "M2") (pinfunction "IN12_M2") (pintype "input"))
      (node (ref "D02") (pin "H2") (pinfunction "P$2_H2") (pintype "bidirectional"))
    )
    (net (code "104") (name "I{slash}O_BMB_00") (class "Default")
      (node (ref "A03") (pin "B1") (pinfunction "P$2_B1") (pintype "bidirectional"))
      (node (ref "C02") (pin "A1") (pinfunction "IN1_A1") (pintype "input"))
      (node (ref "D03") (pin "B1") (pinfunction "P$2_B1") (pintype "bidirectional"))
    )
    (net (code "105") (name "I{slash}O_BMB_01") (class "Default")
      (node (ref "A03") (pin "D1") (pinfunction "P$2_D1") (pintype "bidirectional"))
      (node (ref "C02") (pin "D1") (pinfunction "IN2_D1") (pintype "input"))
      (node (ref "D03") (pin "D1") (pinfunction "P$2_D1") (pintype "bidirectional"))
    )
    (net (code "106") (name "I{slash}O_BMB_02") (class "Default")
      (node (ref "A03") (pin "E1") (pinfunction "P$2_E1") (pintype "bidirectional"))
      (node (ref "C02") (pin "F1") (pinfunction "IN3_F1") (pintype "input"))
      (node (ref "D03") (pin "E1") (pinfunction "P$2_E1") (pintype "bidirectional"))
    )
    (net (code "107") (name "I{slash}O_BMB_03") (class "Default")
      (node (ref "A03") (pin "J1") (pinfunction "P$2_J1") (pintype "bidirectional"))
      (node (ref "C02") (pin "J1") (pinfunction "IN4_J1") (pintype "input"))
      (node (ref "C04") (pin "D2") (pinfunction "D2_D2") (pintype "input"))
      (node (ref "C05") (pin "D2") (pinfunction "D2_D2") (pintype "input"))
      (node (ref "D03") (pin "J1") (pinfunction "P$2_J1") (pintype "bidirectional"))
    )
    (net (code "108") (name "I{slash}O_BMB_04") (class "Default")
      (node (ref "A03") (pin "M1") (pinfunction "P$2_M1") (pintype "bidirectional"))
      (node (ref "C02") (pin "L1") (pinfunction "IN5_L1") (pintype "input"))
      (node (ref "C04") (pin "E2") (pinfunction "E2_E2") (pintype "input"))
      (node (ref "C05") (pin "E2") (pinfunction "E2_E2") (pintype "input"))
      (node (ref "D03") (pin "M1") (pinfunction "P$2_M1") (pintype "bidirectional"))
    )
    (net (code "109") (name "I{slash}O_BMB_05") (class "Default")
      (node (ref "A03") (pin "S1") (pinfunction "P$2_S1") (pintype "bidirectional"))
      (node (ref "C02") (pin "N1") (pinfunction "IN6_N1") (pintype "input"))
      (node (ref "C04") (pin "F2") (pinfunction "F2_F2") (pintype "input"))
      (node (ref "C05") (pin "F2") (pinfunction "F2_F2") (pintype "input"))
      (node (ref "D03") (pin "S1") (pinfunction "P$2_S1") (pintype "bidirectional"))
    )
    (net (code "110") (name "I{slash}O_BMB_06") (class "Default")
      (node (ref "A03") (pin "E2") (pinfunction "P$2_E2") (pintype "bidirectional"))
      (node (ref "C02") (pin "R1") (pinfunction "IN7_R1") (pintype "input"))
      (node (ref "C04") (pin "H2") (pinfunction "H2_H2") (pintype "input"))
      (node (ref "C05") (pin "H2") (pinfunction "H2_H2") (pintype "input"))
      (node (ref "D03") (pin "E2") (pinfunction "P$2_E2") (pintype "bidirectional"))
    )
    (net (code "111") (name "I{slash}O_BMB_07") (class "Default")
      (node (ref "A03") (pin "K2") (pinfunction "P$2_K2") (pintype "bidirectional"))
      (node (ref "C02") (pin "V1") (pinfunction "IN8_V1") (pintype "input"))
      (node (ref "C04") (pin "J2") (pinfunction "J2_J2") (pintype "input"))
      (node (ref "C05") (pin "J2") (pinfunction "J2_J2") (pintype "input"))
      (node (ref "D03") (pin "K2") (pinfunction "P$2_K2") (pintype "bidirectional"))
    )
    (net (code "112") (name "I{slash}O_BMB_08") (class "Default")
      (node (ref "A03") (pin "P2") (pinfunction "P$2_P2") (pintype "bidirectional"))
      (node (ref "C02") (pin "E2") (pinfunction "IN9_E2") (pintype "input"))
      (node (ref "C05") (pin "K2") (pinfunction "K2_K2") (pintype "input"))
      (node (ref "D03") (pin "P2") (pinfunction "P$2_P2") (pintype "bidirectional"))
    )
    (net (code "113") (name "I{slash}O_BMB_09") (class "Default")
      (node (ref "A03") (pin "S2") (pinfunction "P$2_S2") (pintype "bidirectional"))
      (node (ref "C02") (pin "H2") (pinfunction "IN10_H2") (pintype "input"))
      (node (ref "D03") (pin "S2") (pinfunction "P$2_S2") (pintype "bidirectional"))
    )
    (net (code "114") (name "I{slash}O_BMB_10") (class "Default")
      (node (ref "A03") (pin "T2") (pinfunction "P$2_T2") (pintype "bidirectional"))
      (node (ref "C02") (pin "K2") (pinfunction "IN11_K2") (pintype "input"))
      (node (ref "D03") (pin "T2") (pinfunction "P$2_T2") (pintype "bidirectional"))
    )
    (net (code "115") (name "I{slash}O_BMB_11") (class "Default")
      (node (ref "A03") (pin "V2") (pinfunction "P$2_V2") (pintype "bidirectional"))
      (node (ref "C02") (pin "M2") (pinfunction "IN12_M2") (pintype "input"))
      (node (ref "D03") (pin "V2") (pinfunction "P$2_V2") (pintype "bidirectional"))
    )
    (net (code "116") (name "I{slash}O_DATA_IN") (class "Default")
      (node (ref "A05") (pin "M2") (pinfunction "P$2_M2") (pintype "bidirectional"))
      (node (ref "B05") (pin "J2") (pinfunction "E_J2") (pintype "open_collector"))
      (node (ref "D05") (pin "M2") (pinfunction "P$2_M2") (pintype "bidirectional"))
    )
    (net (code "117") (name "I{slash}O_PWR_CLR") (class "Default")
      (node (ref "A02") (pin "V2") (pinfunction "P$2_V2") (pintype "bidirectional"))
      (node (ref "C05") (pin "H1") (pinfunction "IN1_H1") (pintype "input"))
      (node (ref "D02") (pin "V2") (pinfunction "P$2_V2") (pintype "bidirectional"))
    )
    (net (code "118") (name "I{slash}O_TS03") (class "Default")
      (node (ref "A02") (pin "S2") (pinfunction "P$2_S2") (pintype "bidirectional"))
      (node (ref "C04") (pin "H1") (pinfunction "IN1_H1") (pintype "input"))
      (node (ref "D02") (pin "S2") (pinfunction "P$2_S2") (pintype "bidirectional"))
    )
    (net (code "119") (name "I{slash}O_TS04") (class "Default")
      (node (ref "A02") (pin "T2") (pinfunction "P$2_T2") (pintype "bidirectional"))
      (node (ref "D02") (pin "T2") (pinfunction "P$2_T2") (pintype "bidirectional"))
    )
    (net (code "120") (name "I{slash}~{O_0_TO_AC}") (class "Default")
      (node (ref "A04") (pin "P2") (pinfunction "P$2_P2") (pintype "bidirectional"))
      (node (ref "B05") (pin "L1") (pinfunction "E_L1") (pintype "open_collector"))
      (node (ref "D04") (pin "P2") (pinfunction "P$2_P2") (pintype "bidirectional"))
    )
    (net (code "121") (name "I{slash}~{O_1_TO_CA_INH}") (class "Default")
      (node (ref "A06") (pin "M2") (pinfunction "P$2_M2") (pintype "bidirectional"))
      (node (ref "B05") (pin "N2") (pinfunction "D_N2") (pintype "open_collector"))
      (node (ref "D06") (pin "M2") (pinfunction "P$2_M2") (pintype "bidirectional"))
    )
    (net (code "122") (name "I{slash}~{O_ADDR_ACC}") (class "Default")
      (node (ref "A05") (pin "S2") (pinfunction "P$2_S2") (pintype "bidirectional"))
      (node (ref "C02") (pin "U2") (pinfunction "IN15_U2") (pintype "input"))
      (node (ref "D05") (pin "S2") (pinfunction "P$2_S2") (pintype "bidirectional"))
    )
    (net (code "123") (name "I{slash}~{O_BMB_03}") (class "Default")
      (node (ref "A03") (pin "H1") (pinfunction "P$2_H1") (pintype "bidirectional"))
      (node (ref "D03") (pin "H1") (pinfunction "P$2_H1") (pintype "bidirectional"))
    )
    (net (code "124") (name "I{slash}~{O_BMB_04}") (class "Default")
      (node (ref "A03") (pin "L1") (pinfunction "P$2_L1") (pintype "bidirectional"))
      (node (ref "D03") (pin "L1") (pinfunction "P$2_L1") (pintype "bidirectional"))
    )
    (net (code "125") (name "I{slash}~{O_BMB_05}") (class "Default")
      (node (ref "A03") (pin "P1") (pinfunction "P$2_P1") (pintype "bidirectional"))
      (node (ref "D03") (pin "P1") (pinfunction "P$2_P1") (pintype "bidirectional"))
    )
    (net (code "126") (name "I{slash}~{O_BMB_06}") (class "Default")
      (node (ref "A03") (pin "D2") (pinfunction "P$2_D2") (pintype "bidirectional"))
      (node (ref "D03") (pin "D2") (pinfunction "P$2_D2") (pintype "bidirectional"))
    )
    (net (code "127") (name "I{slash}~{O_BMB_07}") (class "Default")
      (node (ref "A03") (pin "H2") (pinfunction "P$2_H2") (pintype "bidirectional"))
      (node (ref "D03") (pin "H2") (pinfunction "P$2_H2") (pintype "bidirectional"))
    )
    (net (code "128") (name "I{slash}~{O_BMB_08}") (class "Default")
      (node (ref "A03") (pin "M2") (pinfunction "P$2_M2") (pintype "bidirectional"))
      (node (ref "C04") (pin "K2") (pinfunction "K2_K2") (pintype "input"))
      (node (ref "D03") (pin "M2") (pinfunction "P$2_M2") (pintype "bidirectional"))
    )
    (net (code "129") (name "I{slash}~{O_BRK_RQ}") (class "Default")
      (node (ref "A05") (pin "K2") (pinfunction "P$2_K2") (pintype "bidirectional"))
      (node (ref "B05") (pin "D1") (pinfunction "D_D1") (pintype "open_collector"))
      (node (ref "D05") (pin "K2") (pinfunction "P$2_K2") (pintype "bidirectional"))
    )
    (net (code "130") (name "I{slash}~{O_BWC0}") (class "Default")
      (node (ref "A06") (pin "P2") (pinfunction "P$2_P2") (pintype "bidirectional"))
      (node (ref "C01") (pin "F1") (pinfunction "IN_F1") (pintype "input"))
      (node (ref "D06") (pin "P2") (pinfunction "P$2_P2") (pintype "bidirectional"))
    )
    (net (code "131") (name "I{slash}~{O_INT_RQ}") (class "Default")
      (node (ref "A04") (pin "M2") (pinfunction "P$2_M2") (pintype "bidirectional"))
      (node (ref "B05") (pin "E1") (pinfunction "E_E1") (pintype "open_collector"))
      (node (ref "D04") (pin "M2") (pinfunction "P$2_M2") (pintype "bidirectional"))
    )
    (net (code "132") (name "I{slash}~{O_SKP_RQ}") (class "Default")
      (node (ref "A04") (pin "K2") (pinfunction "P$2_K2") (pintype "bidirectional"))
      (node (ref "B05") (pin "K1") (pinfunction "D_K1") (pintype "open_collector"))
      (node (ref "D04") (pin "K2") (pinfunction "P$2_K2") (pintype "bidirectional"))
    )
    (net (code "133") (name "LDMF") (class "Default")
      (node (ref "C05") (pin "E1") (pinfunction "E1_E1") (pintype "output"))
      (node (ref "D11") (pin "B1") (pinfunction "C_B1") (pintype "input"))
      (node (ref "D11") (pin "D2") (pinfunction "C_D2") (pintype "input"))
      (node (ref "D11") (pin "H1") (pinfunction "C_H1") (pintype "input"))
    )
    (net (code "134") (name "LPB_00") (class "Default")
      (node (ref "A25") (pin "T2") (pinfunction "P$2_T2") (pintype "bidirectional"))
      (node (ref "C08") (pin "D1") (pinfunction "IN2B_D1") (pintype "input"))
      (node (ref "D08") (pin "E1") (pinfunction "E1_E1") (pintype "output"))
      (node (ref "D10") (pin "M1") (pinfunction "IN1_M1") (pintype "input"))
    )
    (net (code "135") (name "LPB_01") (class "Default")
      (node (ref "A25") (pin "U2") (pinfunction "P$2_U2") (pintype "bidirectional"))
      (node (ref "C08") (pin "K1") (pinfunction "IN2B_K1") (pintype "input"))
      (node (ref "D08") (pin "L1") (pinfunction "L1_L1") (pintype "output"))
      (node (ref "D10") (pin "N1") (pinfunction "IN2_N1") (pintype "input"))
    )
    (net (code "136") (name "LPB_02") (class "Default")
      (node (ref "A25") (pin "V2") (pinfunction "P$2_V2") (pintype "bidirectional"))
      (node (ref "C08") (pin "R1") (pinfunction "IN2B_R1") (pintype "input"))
      (node (ref "D08") (pin "S1") (pinfunction "S1_S1") (pintype "output"))
      (node (ref "D10") (pin "P1") (pinfunction "IN3_P1") (pintype "input"))
    )
    (net (code "137") (name "LPB_03") (class "Default")
      (node (ref "A26") (pin "A2") (pinfunction "P$2_A2") (pintype "bidirectional"))
      (node (ref "C08") (pin "H2") (pinfunction "IN2B_H2") (pintype "input"))
      (node (ref "D08") (pin "H2") (pinfunction "H2_H2") (pintype "output"))
      (node (ref "D10") (pin "R1") (pinfunction "IN4_R1") (pintype "input"))
    )
    (net (code "138") (name "LPB_04") (class "Default")
      (node (ref "A26") (pin "B2") (pinfunction "P$2_B2") (pintype "bidirectional"))
      (node (ref "C08") (pin "N2") (pinfunction "IN2B_N2") (pintype "input"))
      (node (ref "D08") (pin "P2") (pinfunction "P2_P2") (pintype "output"))
      (node (ref "D10") (pin "R2") (pinfunction "IN5_R2") (pintype "input"))
    )
    (net (code "139") (name "LPB_05") (class "Default")
      (node (ref "A26") (pin "C2") (pinfunction "P$2_C2") (pintype "bidirectional"))
      (node (ref "C08") (pin "U2") (pinfunction "IN2B_U2") (pintype "input"))
      (node (ref "D08") (pin "V2") (pinfunction "V2_V2") (pintype "output"))
      (node (ref "D10") (pin "S2") (pinfunction "IN6_S2") (pintype "input"))
      (node (ref "D10") (pin "T2") (pinfunction "IN7_T2") (pintype "input"))
      (node (ref "D10") (pin "U2") (pinfunction "IN8_U2") (pintype "input"))
    )
    (net (code "140") (name "LPB_NOT_EQ_1") (class "Default")
      (node (ref "A10") (pin "M1") (pinfunction "IN2_M1") (pintype "input"))
      (node (ref "D10") (pin "V2") (pinfunction "OUT_V2") (pintype "output"))
    )
    (net (code "141") (name "LPB_TO_DTB") (class "Default")
      (node (ref "A11") (pin "T2") (pinfunction "OUT_T2") (pintype "output"))
      (node (ref "C08") (pin "C1") (pinfunction "IN2A_C1") (pintype "input"))
      (node (ref "C08") (pin "F2") (pinfunction "IN2A_F2") (pintype "input"))
      (node (ref "C08") (pin "J1") (pinfunction "IN2A_J1") (pintype "input"))
      (node (ref "C08") (pin "M2") (pinfunction "IN2A_M2") (pintype "input"))
      (node (ref "C08") (pin "P1") (pinfunction "IN2A_P1") (pintype "input"))
      (node (ref "C08") (pin "T2") (pinfunction "IN2A_T2") (pintype "input"))
    )
    (net (code "142") (name "MC00") (class "Default")
      (node (ref "A26") (pin "S1") (pinfunction "P$2_S1") (pintype "bidirectional"))
      (node (ref "B13") (pin "E1") (pinfunction "1_E1") (pintype "output"))
      (node (ref "B13") (pin "E2") (pinfunction "D_E2") (pintype "input"))
      (node (ref "D10") (pin "D2") (pinfunction "IN5_D2") (pintype "input"))
    )
    (net (code "143") (name "MC01") (class "Default")
      (node (ref "A08") (pin "L2") (pinfunction "C_L2") (pintype "input"))
      (node (ref "A26") (pin "T1") (pinfunction "P$2_T1") (pintype "bidirectional"))
      (node (ref "B13") (pin "H2") (pinfunction "1_H2") (pintype "output"))
      (node (ref "B13") (pin "J1") (pinfunction "D_J1") (pintype "input"))
      (node (ref "C11") (pin "E1") (pinfunction "IN2_E1") (pintype "input"))
    )
    (net (code "144") (name "MC02") (class "Default")
      (node (ref "A26") (pin "U1") (pinfunction "P$2_U1") (pintype "bidirectional"))
      (node (ref "B11") (pin "U2") (pinfunction "IN2_U2") (pintype "input"))
      (node (ref "B13") (pin "L1") (pinfunction "1_L1") (pintype "output"))
      (node (ref "D12") (pin "D2") (pinfunction "IN1_D2") (pintype "input"))
      (node (ref "D12") (pin "E2") (pinfunction "IN2_E2") (pintype "input"))
    )
    (net (code "145") (name "MF00") (class "Default")
      (node (ref "A25") (pin "V1") (pinfunction "P$2_V1") (pintype "bidirectional"))
      (node (ref "D11") (pin "E1") (pinfunction "1_E1") (pintype "output"))
    )
    (net (code "146") (name "MF01") (class "Default")
      (node (ref "A26") (pin "A1") (pinfunction "P$2_A1") (pintype "bidirectional"))
      (node (ref "D11") (pin "H2") (pinfunction "1_H2") (pintype "output"))
    )
    (net (code "147") (name "MF02") (class "Default")
      (node (ref "A26") (pin "B1") (pinfunction "P$2_B1") (pintype "bidirectional"))
      (node (ref "D11") (pin "L1") (pinfunction "1_L1") (pintype "output"))
    )
    (net (code "148") (name "MKT") (class "Default")
      (node (ref "A26") (pin "H2") (pinfunction "P$2_H2") (pintype "bidirectional"))
      (node (ref "B12") (pin "S2") (pinfunction "IN2_S2") (pintype "input"))
      (node (ref "B13") (pin "V2") (pinfunction "1_V2") (pintype "output"))
      (node (ref "B15") (pin "L1") (pinfunction "IN1_L1") (pintype "input"))
      (node (ref "C15") (pin "L2") (pinfunction "IN1_L2") (pintype "input"))
    )
    (net (code "149") (name "MKTK") (class "Default")
      (node (ref "A08") (pin "R2") (pinfunction "0_R2") (pintype "output"))
      (node (ref "A25") (pin "P1") (pinfunction "P$2_P1") (pintype "bidirectional"))
    )
    (net (code "150") (name "MK_BLK_END") (class "Default")
      (node (ref "A09") (pin "T2") (pinfunction "IN3_T2") (pintype "input"))
      (node (ref "CD18") (pin "BU1") (pinfunction "BU1_BU1") (pintype "output"))
    )
    (net (code "151") (name "MK_BLK_MK") (class "Default")
      (node (ref "CD18") (pin "AE2") (pinfunction "AE2_AE2") (pintype "output"))
      (node (ref "D10") (pin "A1") (pinfunction "IN1_A1") (pintype "input"))
      (node (ref "D10") (pin "B1") (pinfunction "IN2_B1") (pintype "input"))
    )
    (net (code "152") (name "MK_BLK_START") (class "Default")
      (node (ref "CD18") (pin "AJ2") (pinfunction "AJ2_AJ2") (pintype "output"))
    )
    (net (code "153") (name "MK_BLK_SYNC") (class "Default")
      (node (ref "CD18") (pin "BS2") (pinfunction "BS2_BS2") (pintype "output"))
    )
    (net (code "154") (name "MK_DATA") (class "Default")
      (node (ref "CD18") (pin "BP2") (pinfunction "BP2_BP2") (pintype "output"))
    )
    (net (code "155") (name "MK_DATA_SYNC") (class "Default")
      (node (ref "CD18") (pin "AH1") (pinfunction "AH1_AH1") (pintype "output"))
    )
    (net (code "156") (name "MK_END") (class "Default")
      (node (ref "A08") (pin "C1") (pinfunction "D_C1") (pintype "input"))
      (node (ref "CD18") (pin "AF2") (pinfunction "AF2_AF2") (pintype "output"))
    )
    (net (code "157") (name "MOVE") (class "Default")
      (node (ref "D07") (pin "D2") (pinfunction "O0_D2") (pintype "output"))
    )
    (net (code "158") (name "MR00") (class "Default")
      (node (ref "A25") (pin "D1") (pinfunction "P$2_D1") (pintype "bidirectional"))
      (node (ref "B07") (pin "P2") (pinfunction "P2_P2") (pintype "output"))
      (node (ref "B14") (pin "M2") (pinfunction "D_M2") (pintype "input"))
    )
    (net (code "159") (name "MR01") (class "Default")
      (node (ref "A25") (pin "E1") (pinfunction "P$2_E1") (pintype "bidirectional"))
      (node (ref "C07") (pin "P2") (pinfunction "P2_P2") (pintype "output"))
      (node (ref "C12") (pin "B1") (pinfunction "IN2_B1") (pintype "input"))
    )
    (net (code "160") (name "Net-(A08D-D)") (class "Default")
      (node (ref "A08") (pin "E2") (pinfunction "D_E2") (pintype "input"))
      (node (ref "A09") (pin "L1") (pinfunction "OUT_L1") (pintype "output"))
    )
    (net (code "161") (name "Net-(A08E-S)") (class "Default")
      (node (ref "A08") (pin "K1") (pinfunction "S_K1") (pintype "input"))
      (node (ref "A11") (pin "E1") (pinfunction "OUT_E1") (pintype "output"))
    )
    (net (code "162") (name "Net-(A08F-D)") (class "Default")
      (node (ref "A08") (pin "M2") (pinfunction "D_M2") (pintype "input"))
      (node (ref "A09") (pin "J2") (pinfunction "OUT_J2") (pintype "output"))
    )
    (net (code "163") (name "Net-(A08G-C)") (class "Default")
      (node (ref "A08") (pin "N1") (pinfunction "C_N1") (pintype "input"))
      (node (ref "A11") (pin "D2") (pinfunction "OUT_D2") (pintype "output"))
    )
    (net (code "164") (name "Net-(A08G-D)") (class "Default")
      (node (ref "A08") (pin "P1") (pinfunction "D_P1") (pintype "input"))
      (node (ref "A10") (pin "N1") (pinfunction "OUT_N1") (pintype "output"))
    )
    (net (code "165") (name "Net-(A08H-S)") (class "Default")
      (node (ref "A08") (pin "U2") (pinfunction "S_U2") (pintype "input"))
      (node (ref "B10") (pin "S1") (pinfunction "OUT_S1") (pintype "output"))
    )
    (net (code "166") (name "Net-(A09A-OUT)") (class "Default")
      (node (ref "A09") (pin "E1") (pinfunction "OUT_E1") (pintype "output"))
      (node (ref "A11") (pin "A1") (pinfunction "IN_A1") (pintype "input"))
    )
    (net (code "167") (name "Net-(A09D-IN4)") (class "Default")
      (node (ref "A09") (pin "H2") (pinfunction "IN4_H2") (pintype "input"))
      (node (ref "A11") (pin "B1") (pinfunction "OUT_B1") (pintype "output"))
    )
    (net (code "168") (name "Net-(A09E-IN1)") (class "Default")
      (node (ref "A09") (pin "F1") (pinfunction "IN1_F1") (pintype "input"))
      (node (ref "C10") (pin "P2") (pinfunction "OUT_P2") (pintype "output"))
    )
    (net (code "169") (name "Net-(A09E-IN3)") (class "Default")
      (node (ref "A09") (pin "J1") (pinfunction "IN3_J1") (pintype "input"))
      (node (ref "A10") (pin "K1") (pinfunction "OUT_K1") (pintype "output"))
    )
    (net (code "170") (name "Net-(A09F-OUT)") (class "Default")
      (node (ref "A09") (pin "P2") (pinfunction "OUT_P2") (pintype "output"))
      (node (ref "A11") (pin "F1") (pinfunction "IN_F1") (pintype "input"))
    )
    (net (code "171") (name "Net-(A09G-OUT)") (class "Default")
      (node (ref "A09") (pin "S1") (pinfunction "OUT_S1") (pintype "output"))
      (node (ref "A10") (pin "U2") (pinfunction "IN2_U2") (pintype "input"))
    )
    (net (code "172") (name "Net-(A09J-IN4)") (class "Default")
      (node (ref "A09") (pin "U2") (pinfunction "IN4_U2") (pintype "input"))
      (node (ref "C17") (pin "R2") (pinfunction "OUT_R2") (pintype "output"))
    )
    (net (code "173") (name "Net-(A09J-OUT)") (class "Default")
      (node (ref "A09") (pin "V2") (pinfunction "OUT_V2") (pintype "output"))
      (node (ref "A11") (pin "S2") (pinfunction "IN_S2") (pintype "input"))
    )
    (net (code "174") (name "Net-(A10A-IN2)") (class "Default")
      (node (ref "A10") (pin "B1") (pinfunction "IN2_B1") (pintype "input"))
      (node (ref "A10") (pin "F1") (pinfunction "OUT_F1") (pintype "output"))
      (node (ref "B15") (pin "P2") (pinfunction "IN1_P2") (pintype "input"))
    )
    (net (code "175") (name "Net-(A10A-OUT)") (class "Default")
      (node (ref "A10") (pin "C1") (pinfunction "OUT_C1") (pintype "output"))
      (node (ref "A10") (pin "D1") (pinfunction "IN1_D1") (pintype "input"))
    )
    (net (code "176") (name "Net-(A10C-OUT)") (class "Default")
      (node (ref "A10") (pin "F2") (pinfunction "OUT_F2") (pintype "output"))
      (node (ref "A10") (pin "J2") (pinfunction "IN2_J2") (pintype "input"))
    )
    (net (code "177") (name "Net-(A10J-OUT)") (class "Default")
      (node (ref "A10") (pin "S1") (pinfunction "OUT_S1") (pintype "output"))
      (node (ref "A11") (pin "C1") (pinfunction "IN_C1") (pintype "input"))
    )
    (net (code "178") (name "Net-(A10K-OUT)") (class "Default")
      (node (ref "A10") (pin "S2") (pinfunction "OUT_S2") (pintype "output"))
      (node (ref "A10") (pin "T2") (pinfunction "IN1_T2") (pintype "input"))
    )
    (net (code "179") (name "Net-(A10N-OUT)") (class "Default")
      (node (ref "A10") (pin "V2") (pinfunction "OUT_V2") (pintype "output"))
      (node (ref "A11") (pin "D1") (pinfunction "IN_D1") (pintype "input"))
    )
    (net (code "180") (name "Net-(A11G-OUT)") (class "Default")
      (node (ref "A11") (pin "H1") (pinfunction "OUT_H1") (pintype "output"))
      (node (ref "A12") (pin "B1") (pinfunction "IN2_B1") (pintype "input"))
      (node (ref "A12") (pin "D1") (pinfunction "IN1_D1") (pintype "input"))
    )
    (net (code "181") (name "Net-(A11N-IN)") (class "Default")
      (node (ref "A11") (pin "P2") (pinfunction "IN_P2") (pintype "input"))
      (node (ref "A14") (pin "F2") (pinfunction "F2_F2") (pintype "output"))
    )
    (net (code "182") (name "Net-(A11O-IN)") (class "Default")
      (node (ref "A11") (pin "R1") (pinfunction "IN_R1") (pintype "input"))
      (node (ref "B11") (pin "S2") (pinfunction "OUT_S2") (pintype "output"))
    )
    (net (code "183") (name "Net-(A11Q-IN)") (class "Default")
      (node (ref "A11") (pin "V1") (pinfunction "IN_V1") (pintype "input"))
      (node (ref "B08") (pin "V2") (pinfunction "OUT_V2") (pintype "output"))
    )
    (net (code "184") (name "Net-(A11R-IN)") (class "Default")
      (node (ref "A11") (pin "U2") (pinfunction "IN_U2") (pintype "input"))
      (node (ref "A14") (pin "T2") (pinfunction "F2_T2") (pintype "output"))
    )
    (net (code "185") (name "Net-(A12C-OUT)") (class "Default")
      (node (ref "A12") (pin "F2") (pinfunction "OUT_F2") (pintype "output"))
      (node (ref "B10") (pin "A1") (pinfunction "IN1_A1") (pintype "input"))
      (node (ref "B10") (pin "B1") (pinfunction "IN2_B1") (pintype "input"))
    )
    (net (code "186") (name "Net-(A12F-IN2)") (class "Default")
      (node (ref "A12") (pin "J1") (pinfunction "IN2_J1") (pintype "input"))
      (node (ref "A12") (pin "N1") (pinfunction "OUT_N1") (pintype "output"))
      (node (ref "A12") (pin "P1") (pinfunction "IN1_P1") (pintype "input"))
    )
    (net (code "187") (name "Net-(A12G-OUT)") (class "Default")
      (node (ref "A12") (pin "K2") (pinfunction "OUT_K2") (pintype "output"))
      (node (ref "B10") (pin "C1") (pinfunction "IN3_C1") (pintype "input"))
      (node (ref "B10") (pin "D1") (pinfunction "IN4_D1") (pintype "input"))
    )
    (net (code "188") (name "Net-(A12I-OUT)") (class "Default")
      (node (ref "A12") (pin "N2") (pinfunction "OUT_N2") (pintype "output"))
      (node (ref "A12") (pin "T2") (pinfunction "IN1_T2") (pintype "input"))
    )
    (net (code "189") (name "Net-(A12K-OUT)") (class "Default")
      (node (ref "A12") (pin "S2") (pinfunction "OUT_S2") (pintype "output"))
      (node (ref "A12") (pin "U2") (pinfunction "IN2_U2") (pintype "input"))
    )
    (net (code "190") (name "Net-(A14-PadD2)") (class "Default")
      (node (ref "A14") (pin "D2") (pinfunction "D2_D2") (pintype "passive"))
      (node (ref "A14") (pin "E2") (pinfunction "E2_E2") (pintype "passive"))
    )
    (net (code "191") (name "Net-(A14-PadH1)") (class "Default")
      (node (ref "A14") (pin "H1") (pinfunction "H1_H1") (pintype "passive"))
      (node (ref "A14") (pin "L2") (pinfunction "L2_L2") (pintype "passive"))
    )
    (net (code "192") (name "Net-(A14D-D2)") (class "Default")
      (node (ref "A14") (pin "R2") (pinfunction "E2_R2") (pintype "passive"))
      (node (ref "A14") (pin "V2") (pinfunction "D2_V2") (pintype "passive"))
    )
    (net (code "193") (name "Net-(A14D-H1)") (class "Default")
      (node (ref "A14") (pin "S1") (pinfunction "H1_S1") (pintype "passive"))
      (node (ref "A14") (pin "S2") (pinfunction "L2_S2") (pintype "passive"))
    )
    (net (code "194") (name "Net-(A14D-H2)") (class "Default")
      (node (ref "A14") (pin "M2") (pinfunction "H2_M2") (pintype "input"))
      (node (ref "A14") (pin "N2") (pinfunction "J2_N2") (pintype "input"))
      (node (ref "A14") (pin "P2") (pinfunction "K2_P2") (pintype "input"))
      (node (ref "B15") (pin "F2") (pinfunction "OUT_F2") (pintype "output"))
    )
    (net (code "195") (name "Net-(A15A-IN3)") (class "Default")
      (node (ref "A15") (pin "C1") (pinfunction "IN3_C1") (pintype "input"))
      (node (ref "A15") (pin "D1") (pinfunction "IN4_D1") (pintype "input"))
      (node (ref "C17") (pin "D2") (pinfunction "OUT_D2") (pintype "output"))
    )
    (net (code "196") (name "Net-(A15D-IN1)") (class "Default")
      (node (ref "A15") (pin "D2") (pinfunction "IN1_D2") (pintype "input"))
      (node (ref "A15") (pin "E2") (pinfunction "IN2_E2") (pintype "input"))
      (node (ref "C17") (pin "F2") (pinfunction "OUT_F2") (pintype "output"))
    )
    (net (code "197") (name "Net-(A16-PadD2)") (class "Default")
      (node (ref "A16") (pin "D2") (pinfunction "D2_D2") (pintype "passive"))
      (node (ref "A16") (pin "E2") (pinfunction "E2_E2") (pintype "passive"))
    )
    (net (code "198") (name "Net-(A16C-D2)") (class "Default")
      (node (ref "A16") (pin "R2") (pinfunction "E2_R2") (pintype "passive"))
      (node (ref "A16") (pin "S2") (pinfunction "D2_S2") (pintype "passive"))
    )
    (net (code "199") (name "Net-(AB19A-P$2)") (class "Default")
      (node (ref "A18") (pin "D2") (pinfunction "D2_D2") (pintype "input"))
      (node (ref "A18") (pin "J2") (pinfunction "J2_J2") (pintype "output"))
      (node (ref "AB19") (pin "AF2") (pinfunction "P$2_AF2") (pintype "bidirectional"))
    )
    (net (code "200") (name "Net-(AB19B-P$2)") (class "Default")
      (node (ref "A18") (pin "E2") (pinfunction "E2_E2") (pintype "input"))
      (node (ref "A18") (pin "K2") (pinfunction "K2_K2") (pintype "output"))
      (node (ref "AB19") (pin "AH2") (pinfunction "P$2_AH2") (pintype "bidirectional"))
    )
    (net (code "201") (name "Net-(AB19D-P$2)") (class "Default")
      (node (ref "AB19") (pin "AN2") (pinfunction "P$2_AN2") (pintype "bidirectional"))
      (node (ref "B18") (pin "D2") (pinfunction "D2_D2") (pintype "input"))
      (node (ref "B18") (pin "J2") (pinfunction "J2_J2") (pintype "output"))
    )
    (net (code "202") (name "Net-(AB19E-P$2)") (class "Default")
      (node (ref "AB19") (pin "AP2") (pinfunction "P$2_AP2") (pintype "bidirectional"))
      (node (ref "B18") (pin "E2") (pinfunction "E2_E2") (pintype "input"))
      (node (ref "B18") (pin "K2") (pinfunction "K2_K2") (pintype "output"))
    )
    (net (code "203") (name "Net-(AB19H-P$2)") (class "Default")
      (node (ref "A20") (pin "D2") (pinfunction "D2_D2") (pintype "input"))
      (node (ref "A20") (pin "J2") (pinfunction "J2_J2") (pintype "output"))
      (node (ref "AB19") (pin "AV2") (pinfunction "P$2_AV2") (pintype "bidirectional"))
    )
    (net (code "204") (name "Net-(AB19I-P$2)") (class "Default")
      (node (ref "A20") (pin "E2") (pinfunction "E2_E2") (pintype "input"))
      (node (ref "A20") (pin "K2") (pinfunction "K2_K2") (pintype "output"))
      (node (ref "AB19") (pin "BD2") (pinfunction "P$2_BD2") (pintype "bidirectional"))
    )
    (net (code "205") (name "Net-(AB19K-P$2)") (class "Default")
      (node (ref "AB19") (pin "BH2") (pinfunction "P$2_BH2") (pintype "bidirectional"))
      (node (ref "B20") (pin "D2") (pinfunction "D2_D2") (pintype "input"))
      (node (ref "B20") (pin "J2") (pinfunction "J2_J2") (pintype "output"))
    )
    (net (code "206") (name "Net-(AB19L-P$2)") (class "Default")
      (node (ref "AB19") (pin "BJ2") (pinfunction "P$2_BJ2") (pintype "bidirectional"))
      (node (ref "B20") (pin "E2") (pinfunction "E2_E2") (pintype "input"))
      (node (ref "B20") (pin "K2") (pinfunction "K2_K2") (pintype "output"))
    )
    (net (code "207") (name "Net-(AB19N-P$2)") (class "Default")
      (node (ref "A21") (pin "D2") (pinfunction "D2_D2") (pintype "input"))
      (node (ref "A21") (pin "J2") (pinfunction "J2_J2") (pintype "output"))
      (node (ref "AB19") (pin "BN2") (pinfunction "P$2_BN2") (pintype "bidirectional"))
    )
    (net (code "208") (name "Net-(AB19O-P$2)") (class "Default")
      (node (ref "A21") (pin "E2") (pinfunction "E2_E2") (pintype "input"))
      (node (ref "A21") (pin "K2") (pinfunction "K2_K2") (pintype "output"))
      (node (ref "AB19") (pin "BP2") (pinfunction "P$2_BP2") (pintype "bidirectional"))
    )
    (net (code "209") (name "Net-(B06P-IN)") (class "Default")
      (node (ref "B06") (pin "S2") (pinfunction "IN_S2") (pintype "input"))
      (node (ref "B08") (pin "S2") (pinfunction "OUT_S2") (pintype "output"))
    )
    (net (code "210") (name "Net-(B08A-OUT)") (class "Default")
      (node (ref "B08") (pin "C1") (pinfunction "OUT_C1") (pintype "output"))
      (node (ref "B09") (pin "D1") (pinfunction "S_D1") (pintype "input"))
    )
    (net (code "211") (name "Net-(B08B-OUT)") (class "Default")
      (node (ref "B08") (pin "F1") (pinfunction "OUT_F1") (pintype "output"))
      (node (ref "B09") (pin "U2") (pinfunction "S_U2") (pintype "input"))
    )
    (net (code "212") (name "Net-(B08C-OUT)") (class "Default")
      (node (ref "B08") (pin "F2") (pinfunction "OUT_F2") (pintype "output"))
      (node (ref "B09") (pin "K1") (pinfunction "S_K1") (pintype "input"))
    )
    (net (code "213") (name "Net-(B08F-OUT)") (class "Default")
      (node (ref "B08") (pin "K1") (pinfunction "OUT_K1") (pintype "output"))
      (node (ref "B09") (pin "F2") (pinfunction "S_F2") (pintype "input"))
    )
    (net (code "214") (name "Net-(B08H-OUT)") (class "Default")
      (node (ref "B08") (pin "N1") (pinfunction "OUT_N1") (pintype "output"))
      (node (ref "B09") (pin "N2") (pinfunction "S_N2") (pintype "input"))
    )
    (net (code "215") (name "Net-(B08J-OUT)") (class "Default")
      (node (ref "B08") (pin "S1") (pinfunction "OUT_S1") (pintype "output"))
      (node (ref "B09") (pin "R1") (pinfunction "S_R1") (pintype "input"))
    )
    (net (code "216") (name "Net-(B10D-OUT)") (class "Default")
      (node (ref "B10") (pin "J2") (pinfunction "OUT_J2") (pintype "output"))
      (node (ref "D16") (pin "H2") (pinfunction "H2_H2") (pintype "input"))
      (node (ref "D16") (pin "J2") (pinfunction "J2_J2") (pintype "input"))
      (node (ref "D16") (pin "K2") (pinfunction "K2_K2") (pintype "input"))
    )
    (net (code "217") (name "Net-(B10E-IN1)") (class "Default")
      (node (ref "B10") (pin "F1") (pinfunction "IN1_F1") (pintype "input"))
      (node (ref "B11") (pin "J1") (pinfunction "OUT_J1") (pintype "output"))
    )
    (net (code "218") (name "Net-(B10E-IN4)") (class "Default")
      (node (ref "B10") (pin "K1") (pinfunction "IN4_K1") (pintype "input"))
      (node (ref "C17") (pin "H1") (pinfunction "OUT_H1") (pintype "output"))
    )
    (net (code "219") (name "Net-(B11A-OUT)") (class "Default")
      (node (ref "B11") (pin "D1") (pinfunction "OUT_D1") (pintype "output"))
      (node (ref "B11") (pin "F2") (pinfunction "IN3_F2") (pintype "input"))
    )
    (net (code "220") (name "Net-(B11D-IN1)") (class "Default")
      (node (ref "B11") (pin "D2") (pinfunction "IN1_D2") (pintype "input"))
      (node (ref "B12") (pin "E1") (pinfunction "OUT_E1") (pintype "output"))
    )
    (net (code "221") (name "Net-(B11D-IN2)") (class "Default")
      (node (ref "B11") (pin "E2") (pinfunction "IN2_E2") (pintype "input"))
      (node (ref "B12") (pin "L1") (pinfunction "OUT_L1") (pintype "output"))
    )
    (net (code "222") (name "Net-(B11D-OUT)") (class "Default")
      (node (ref "B11") (pin "H2") (pinfunction "OUT_H2") (pintype "output"))
      (node (ref "C13") (pin "C1") (pinfunction "IN_C1") (pintype "input"))
    )
    (net (code "223") (name "Net-(B11E-IN1)") (class "Default")
      (node (ref "B11") (pin "E1") (pinfunction "IN1_E1") (pintype "input"))
      (node (ref "B11") (pin "U1") (pinfunction "OUT_U1") (pintype "output"))
    )
    (net (code "224") (name "Net-(B11E-IN3)") (class "Default")
      (node (ref "B11") (pin "H1") (pinfunction "IN3_H1") (pintype "input"))
      (node (ref "B11") (pin "N1") (pinfunction "OUT_N1") (pintype "output"))
    )
    (net (code "225") (name "Net-(B11F-IN3)") (class "Default")
      (node (ref "B11") (pin "L2") (pinfunction "IN3_L2") (pintype "input"))
      (node (ref "B15") (pin "S2") (pinfunction "OUT_S2") (pintype "output"))
    )
    (net (code "226") (name "Net-(B11J-OUT)") (class "Default")
      (node (ref "B11") (pin "V1") (pinfunction "OUT_V1") (pintype "output"))
      (node (ref "C17") (pin "J1") (pinfunction "IN_J1") (pintype "input"))
    )
    (net (code "227") (name "Net-(B12D-OUT)") (class "Default")
      (node (ref "B12") (pin "J2") (pinfunction "OUT_J2") (pintype "output"))
      (node (ref "B12") (pin "N2") (pinfunction "IN4_N2") (pintype "input"))
    )
    (net (code "228") (name "Net-(B12F-IN1)") (class "Default")
      (node (ref "B12") (pin "K2") (pinfunction "IN1_K2") (pintype "input"))
      (node (ref "C12") (pin "N1") (pinfunction "OUT_N1") (pintype "output"))
    )
    (net (code "229") (name "Net-(B12F-IN2)") (class "Default")
      (node (ref "B12") (pin "L2") (pinfunction "IN2_L2") (pintype "input"))
      (node (ref "C12") (pin "U1") (pinfunction "OUT_U1") (pintype "output"))
    )
    (net (code "230") (name "Net-(B12F-IN3)") (class "Default")
      (node (ref "B12") (pin "M2") (pinfunction "IN3_M2") (pintype "input"))
      (node (ref "C12") (pin "V1") (pinfunction "OUT_V1") (pintype "output"))
    )
    (net (code "231") (name "Net-(B12G-IN1)") (class "Default")
      (node (ref "B12") (pin "M1") (pinfunction "IN1_M1") (pintype "input"))
      (node (ref "C11") (pin "C1") (pinfunction "OUT_C1") (pintype "output"))
    )
    (net (code "232") (name "Net-(B12G-IN4)") (class "Default")
      (node (ref "B12") (pin "R1") (pinfunction "IN4_R1") (pintype "input"))
      (node (ref "C11") (pin "F1") (pinfunction "OUT_F1") (pintype "output"))
    )
    (net (code "233") (name "Net-(B12G-OUT)") (class "Default")
      (node (ref "B12") (pin "S1") (pinfunction "OUT_S1") (pintype "output"))
      (node (ref "C11") (pin "P1") (pinfunction "IN1_P1") (pintype "input"))
    )
    (net (code "234") (name "Net-(B12J-IN4)") (class "Default")
      (node (ref "B12") (pin "U2") (pinfunction "IN4_U2") (pintype "input"))
      (node (ref "C11") (pin "N1") (pinfunction "OUT_N1") (pintype "output"))
    )
    (net (code "235") (name "Net-(B12J-OUT)") (class "Default")
      (node (ref "B12") (pin "V2") (pinfunction "OUT_V2") (pintype "output"))
      (node (ref "C12") (pin "F1") (pinfunction "IN2_F1") (pintype "input"))
    )
    (net (code "236") (name "Net-(B13F-S)") (class "Default")
      (node (ref "B13") (pin "N2") (pinfunction "S_N2") (pintype "input"))
      (node (ref "B15") (pin "K1") (pinfunction "OUT_K1") (pintype "output"))
    )
    (net (code "237") (name "Net-(B14G-C)") (class "Default")
      (node (ref "B14") (pin "N1") (pinfunction "C_N1") (pintype "input"))
      (node (ref "B14") (pin "S2") (pinfunction "C_S2") (pintype "input"))
      (node (ref "D15") (pin "D2") (pinfunction "D2_D2") (pintype "output"))
    )
    (net (code "238") (name "Net-(B15B-OUT)") (class "Default")
      (node (ref "A14") (pin "H2") (pinfunction "H2_H2") (pintype "input"))
      (node (ref "A14") (pin "J2") (pinfunction "J2_J2") (pintype "input"))
      (node (ref "A14") (pin "K2") (pinfunction "K2_K2") (pintype "input"))
      (node (ref "B15") (pin "F1") (pinfunction "OUT_F1") (pintype "output"))
    )
    (net (code "239") (name "Net-(B15H-OUT)") (class "Default")
      (node (ref "B15") (pin "N1") (pinfunction "OUT_N1") (pintype "output"))
      (node (ref "C17") (pin "F1") (pinfunction "IN_F1") (pintype "input"))
    )
    (net (code "240") (name "Net-(B15J-OUT)") (class "Default")
      (node (ref "B15") (pin "S1") (pinfunction "OUT_S1") (pintype "output"))
      (node (ref "C17") (pin "L1") (pinfunction "IN_L1") (pintype "input"))
    )
    (net (code "241") (name "Net-(B16-PadD2)") (class "Default")
      (node (ref "B16") (pin "D2") (pinfunction "D2_D2") (pintype "passive"))
      (node (ref "B16") (pin "E2") (pinfunction "E2_E2") (pintype "passive"))
    )
    (net (code "242") (name "Net-(B16C-D2)") (class "Default")
      (node (ref "B16") (pin "R2") (pinfunction "E2_R2") (pintype "passive"))
      (node (ref "B16") (pin "S2") (pinfunction "D2_S2") (pintype "passive"))
    )
    (net (code "243") (name "Net-(C08A-OUT)") (class "Default")
      (node (ref "C08") (pin "E1") (pinfunction "OUT_E1") (pintype "output"))
      (node (ref "C09") (pin "D1") (pinfunction "S_D1") (pintype "input"))
    )
    (net (code "244") (name "Net-(C08D-OUT)") (class "Default")
      (node (ref "C08") (pin "J2") (pinfunction "OUT_J2") (pintype "output"))
      (node (ref "C09") (pin "N2") (pinfunction "S_N2") (pintype "input"))
    )
    (net (code "245") (name "Net-(C08E-OUT)") (class "Default")
      (node (ref "C08") (pin "L1") (pinfunction "OUT_L1") (pintype "output"))
      (node (ref "C09") (pin "F2") (pinfunction "S_F2") (pintype "input"))
    )
    (net (code "246") (name "Net-(C08F-OUT)") (class "Default")
      (node (ref "C08") (pin "P2") (pinfunction "OUT_P2") (pintype "output"))
      (node (ref "C09") (pin "R1") (pinfunction "S_R1") (pintype "input"))
    )
    (net (code "247") (name "Net-(C08G-OUT)") (class "Default")
      (node (ref "C08") (pin "S1") (pinfunction "OUT_S1") (pintype "output"))
      (node (ref "C09") (pin "K1") (pinfunction "S_K1") (pintype "input"))
    )
    (net (code "248") (name "Net-(C08J-OUT)") (class "Default")
      (node (ref "C08") (pin "V2") (pinfunction "OUT_V2") (pintype "output"))
      (node (ref "C09") (pin "U2") (pinfunction "S_U2") (pintype "input"))
    )
    (net (code "249") (name "Net-(C10A-OUT)") (class "Default")
      (node (ref "C10") (pin "E1") (pinfunction "OUT_E1") (pintype "output"))
      (node (ref "C14") (pin "C1") (pinfunction "D_C1") (pintype "input"))
    )
    (net (code "250") (name "Net-(C10D-OUT)") (class "Default")
      (node (ref "C10") (pin "J2") (pinfunction "OUT_J2") (pintype "output"))
      (node (ref "C17") (pin "M2") (pinfunction "IN_M2") (pintype "input"))
    )
    (net (code "251") (name "Net-(C10E-OUT)") (class "Default")
      (node (ref "C10") (pin "L1") (pinfunction "OUT_L1") (pintype "output"))
      (node (ref "C14") (pin "E2") (pinfunction "D_E2") (pintype "input"))
    )
    (net (code "252") (name "Net-(C10G-OUT)") (class "Default")
      (node (ref "C10") (pin "S1") (pinfunction "OUT_S1") (pintype "output"))
      (node (ref "C14") (pin "J1") (pinfunction "D_J1") (pintype "input"))
    )
    (net (code "253") (name "Net-(C10J-OUT)") (class "Default")
      (node (ref "C10") (pin "V2") (pinfunction "OUT_V2") (pintype "output"))
      (node (ref "C17") (pin "V1") (pinfunction "IN_V1") (pintype "input"))
    )
    (net (code "254") (name "Net-(C11C-OUT)") (class "Default")
      (node (ref "C11") (pin "F2") (pinfunction "OUT_F2") (pintype "output"))
      (node (ref "C12") (pin "H1") (pinfunction "IN3_H1") (pintype "input"))
    )
    (net (code "255") (name "Net-(C11F-OUT)") (class "Default")
      (node (ref "C11") (pin "K1") (pinfunction "OUT_K1") (pintype "output"))
      (node (ref "C11") (pin "L1") (pinfunction "IN1_L1") (pintype "input"))
    )
    (net (code "256") (name "Net-(C11G-OUT)") (class "Default")
      (node (ref "C11") (pin "K2") (pinfunction "OUT_K2") (pintype "output"))
      (node (ref "D12") (pin "K2") (pinfunction "IN1_K2") (pintype "input"))
      (node (ref "D12") (pin "L2") (pinfunction "IN2_L2") (pintype "input"))
    )
    (net (code "257") (name "Net-(C11J-OUT)") (class "Default")
      (node (ref "C11") (pin "S1") (pinfunction "OUT_S1") (pintype "output"))
      (node (ref "C12") (pin "E1") (pinfunction "IN1_E1") (pintype "input"))
    )
    (net (code "258") (name "Net-(C11K-OUT)") (class "Default")
      (node (ref "C11") (pin "S2") (pinfunction "OUT_S2") (pintype "output"))
      (node (ref "C11") (pin "T2") (pinfunction "IN1_T2") (pintype "input"))
    )
    (net (code "259") (name "Net-(C11N-OUT)") (class "Default")
      (node (ref "C11") (pin "V2") (pinfunction "OUT_V2") (pintype "output"))
      (node (ref "C13") (pin "V1") (pinfunction "IN_V1") (pintype "input"))
    )
    (net (code "260") (name "Net-(C12A-OUT)") (class "Default")
      (node (ref "C12") (pin "D1") (pinfunction "OUT_D1") (pintype "output"))
      (node (ref "C13") (pin "M2") (pinfunction "IN_M2") (pintype "input"))
    )
    (net (code "261") (name "Net-(C12D-OUT)") (class "Default")
      (node (ref "C12") (pin "H2") (pinfunction "OUT_H2") (pintype "output"))
      (node (ref "D12") (pin "M2") (pinfunction "IN3_M2") (pintype "input"))
      (node (ref "D12") (pin "N2") (pinfunction "IN4_N2") (pintype "input"))
    )
    (net (code "262") (name "Net-(C12H-OUT)") (class "Default")
      (node (ref "C12") (pin "S2") (pinfunction "OUT_S2") (pintype "output"))
      (node (ref "C15") (pin "P1") (pinfunction "IN1_P1") (pintype "input"))
    )
    (net (code "263") (name "Net-(C13B-OUT)") (class "Default")
      (node (ref "C13") (pin "D2") (pinfunction "OUT_D2") (pintype "output"))
      (node (ref "C14") (pin "P1") (pinfunction "D_P1") (pintype "input"))
    )
    (net (code "264") (name "Net-(C13L-OUT)") (class "Default")
      (node (ref "C13") (pin "N2") (pinfunction "OUT_N2") (pintype "output"))
      (node (ref "C14") (pin "N2") (pinfunction "S_N2") (pintype "input"))
    )
    (net (code "265") (name "Net-(C13N-IN)") (class "Default")
      (node (ref "C13") (pin "P2") (pinfunction "IN_P2") (pintype "input"))
      (node (ref "C15") (pin "F2") (pinfunction "OUT_F2") (pintype "output"))
    )
    (net (code "266") (name "Net-(C13P-IN)") (class "Default")
      (node (ref "C13") (pin "S2") (pinfunction "IN_S2") (pintype "input"))
      (node (ref "C15") (pin "K2") (pinfunction "OUT_K2") (pintype "output"))
    )
    (net (code "267") (name "Net-(C14F-C)") (class "Default")
      (node (ref "C14") (pin "L2") (pinfunction "C_L2") (pintype "input"))
      (node (ref "C15") (pin "S2") (pinfunction "OUT_S2") (pintype "output"))
    )
    (net (code "268") (name "Net-(C15A-OUT)") (class "Default")
      (node (ref "C15") (pin "C1") (pinfunction "OUT_C1") (pintype "output"))
      (node (ref "C15") (pin "H1") (pinfunction "IN1_H1") (pintype "input"))
    )
    (net (code "269") (name "Net-(C15B-OUT)") (class "Default")
      (node (ref "C15") (pin "F1") (pinfunction "OUT_F1") (pintype "output"))
      (node (ref "C15") (pin "J1") (pinfunction "IN2_J1") (pintype "input"))
    )
    (net (code "270") (name "Net-(C15H-OUT)") (class "Default")
      (node (ref "C15") (pin "N1") (pinfunction "OUT_N1") (pintype "output"))
      (node (ref "C15") (pin "R1") (pinfunction "IN2_R1") (pintype "input"))
    )
    (net (code "271") (name "Net-(C15I-OUT)") (class "Default")
      (node (ref "C15") (pin "N2") (pinfunction "OUT_N2") (pintype "output"))
      (node (ref "C17") (pin "P2") (pinfunction "IN_P2") (pintype "input"))
    )
    (net (code "272") (name "Net-(C16F-IN1)") (class "Default")
      (node (ref "C16") (pin "K2") (pinfunction "IN1_K2") (pintype "input"))
      (node (ref "C16") (pin "L2") (pinfunction "IN2_L2") (pintype "input"))
      (node (ref "C16") (pin "M2") (pinfunction "IN3_M2") (pintype "input"))
      (node (ref "C16") (pin "N2") (pinfunction "IN4_N2") (pintype "input"))
      (node (ref "C17") (pin "B1") (pinfunction "OUT_B1") (pintype "output"))
    )
    (net (code "273") (name "Net-(C16G-OUT)") (class "Default")
      (node (ref "B16") (pin "K2") (pinfunction "K2_K2") (pintype "input"))
      (node (ref "C16") (pin "S1") (pinfunction "OUT_S1") (pintype "output"))
    )
    (net (code "274") (name "Net-(C16J-OUT)") (class "Default")
      (node (ref "A16") (pin "H2") (pinfunction "H2_H2") (pintype "input"))
      (node (ref "C16") (pin "V2") (pinfunction "OUT_V2") (pintype "output"))
    )
    (net (code "275") (name "Net-(C17B-IN)") (class "Default")
      (node (ref "A16") (pin "F2") (pinfunction "F2_F2") (pintype "output"))
      (node (ref "C17") (pin "C1") (pinfunction "IN_C1") (pintype "input"))
    )
    (net (code "276") (name "Net-(C17D-IN)") (class "Default")
      (node (ref "B16") (pin "F2") (pinfunction "F2_F2") (pintype "output"))
      (node (ref "C17") (pin "E2") (pinfunction "IN_E2") (pintype "input"))
    )
    (net (code "277") (name "Net-(C17L-OUT)") (class "Default")
      (node (ref "C17") (pin "N2") (pinfunction "OUT_N2") (pintype "output"))
      (node (ref "D08") (pin "B1") (pinfunction "B1_B1") (pintype "input"))
      (node (ref "D08") (pin "H1") (pinfunction "H1_H1") (pintype "input"))
      (node (ref "D08") (pin "N1") (pinfunction "N1_N1") (pintype "input"))
    )
    (net (code "278") (name "Net-(C17O-IN)") (class "Default")
      (node (ref "C17") (pin "R1") (pinfunction "IN_R1") (pintype "input"))
      (node (ref "D17") (pin "F2") (pinfunction "F2_F2") (pintype "output"))
    )
    (net (code "279") (name "Net-(C17P-IN)") (class "Default")
      (node (ref "C17") (pin "S2") (pinfunction "IN_S2") (pintype "input"))
      (node (ref "D16") (pin "T2") (pinfunction "F2_T2") (pintype "output"))
    )
    (net (code "280") (name "Net-(C17Q-OUT)") (class "Default")
      (node (ref "C17") (pin "U1") (pinfunction "OUT_U1") (pintype "output"))
      (node (ref "D08") (pin "D2") (pinfunction "D2_D2") (pintype "input"))
      (node (ref "D08") (pin "L2") (pinfunction "L2_L2") (pintype "input"))
      (node (ref "D08") (pin "S2") (pinfunction "S2_S2") (pintype "input"))
    )
    (net (code "281") (name "Net-(C17R-IN)") (class "Default")
      (node (ref "C17") (pin "U2") (pinfunction "IN_U2") (pintype "input"))
      (node (ref "D16") (pin "F2") (pinfunction "F2_F2") (pintype "output"))
    )
    (net (code "282") (name "Net-(D09A-OUT)") (class "Default")
      (node (ref "D08") (pin "C1") (pinfunction "C1_C1") (pintype "input"))
      (node (ref "D08") (pin "D1") (pinfunction "D1_D1") (pintype "input"))
      (node (ref "D09") (pin "E1") (pinfunction "OUT_E1") (pintype "output"))
    )
    (net (code "283") (name "Net-(D09D-OUT)") (class "Default")
      (node (ref "D08") (pin "E2") (pinfunction "E2_E2") (pintype "input"))
      (node (ref "D08") (pin "F2") (pinfunction "F2_F2") (pintype "input"))
      (node (ref "D09") (pin "J2") (pinfunction "OUT_J2") (pintype "output"))
    )
    (net (code "284") (name "Net-(D09E-OUT)") (class "Default")
      (node (ref "D08") (pin "J1") (pinfunction "J1_J1") (pintype "input"))
      (node (ref "D08") (pin "K1") (pinfunction "K1_K1") (pintype "input"))
      (node (ref "D09") (pin "L1") (pinfunction "OUT_L1") (pintype "output"))
    )
    (net (code "285") (name "Net-(D09F-OUT)") (class "Default")
      (node (ref "D08") (pin "M2") (pinfunction "M2_M2") (pintype "input"))
      (node (ref "D08") (pin "N2") (pinfunction "N2_N2") (pintype "input"))
      (node (ref "D09") (pin "P2") (pinfunction "OUT_P2") (pintype "output"))
    )
    (net (code "286") (name "Net-(D09G-OUT)") (class "Default")
      (node (ref "D08") (pin "P1") (pinfunction "P1_P1") (pintype "input"))
      (node (ref "D08") (pin "R1") (pinfunction "R1_R1") (pintype "input"))
      (node (ref "D09") (pin "S1") (pinfunction "OUT_S1") (pintype "output"))
    )
    (net (code "287") (name "Net-(D09J-OUT)") (class "Default")
      (node (ref "D08") (pin "T2") (pinfunction "T2_T2") (pintype "input"))
      (node (ref "D08") (pin "U2") (pinfunction "U2_U2") (pintype "input"))
      (node (ref "D09") (pin "V2") (pinfunction "OUT_V2") (pintype "output"))
    )
    (net (code "288") (name "Net-(D10D-OUT)") (class "Default")
      (node (ref "D10") (pin "P2") (pinfunction "OUT_P2") (pintype "output"))
      (node (ref "D14") (pin "J2") (pinfunction "N1_J2") (pintype "input"))
    )
    (net (code "289") (name "Net-(D12A-IN1)") (class "Default")
      (node (ref "D12") (pin "A1") (pinfunction "IN1_A1") (pintype "input"))
      (node (ref "D12") (pin "B1") (pinfunction "IN2_B1") (pintype "input"))
      (node (ref "D12") (pin "C1") (pinfunction "IN3_C1") (pintype "input"))
      (node (ref "D12") (pin "D1") (pinfunction "IN4_D1") (pintype "input"))
      (node (ref "D13") (pin "F2") (pinfunction "F2_F2") (pintype "output"))
    )
    (net (code "290") (name "Net-(D13C-D2)") (class "Default")
      (node (ref "D13") (pin "R2") (pinfunction "E2_R2") (pintype "passive"))
      (node (ref "D13") (pin "S2") (pinfunction "D2_S2") (pintype "passive"))
    )
    (net (code "291") (name "Net-(D14-PadM2)") (class "Default")
      (node (ref "D14") (pin "M2") (pinfunction "M2_M2") (pintype "passive"))
      (node (ref "D14") (pin "V2") (pinfunction "V2_V2") (pintype "passive"))
    )
    (net (code "292") (name "Net-(D14-PadP1)") (class "Default")
      (node (ref "D14") (pin "P1") (pinfunction "P1_P1") (pintype "passive"))
      (node (ref "D14") (pin "V1") (pinfunction "V1_V1") (pintype "passive"))
    )
    (net (code "293") (name "Net-(D14E-M2)") (class "Default")
      (node (ref "D14") (pin "D2") (pinfunction "M2_D2") (pintype "passive"))
      (node (ref "D14") (pin "H1") (pinfunction "P2_H1") (pintype "passive"))
    )
    (net (code "294") (name "Net-(D14E-P1)") (class "Default")
      (node (ref "D14") (pin "A1") (pinfunction "V1_A1") (pintype "passive"))
      (node (ref "D14") (pin "C1") (pinfunction "P1_C1") (pintype "passive"))
    )
    (net (code "295") (name "Net-(D15-PadN2)") (class "Default")
      (node (ref "D15") (pin "N2") (pinfunction "N2_N2") (pintype "passive"))
      (node (ref "D15") (pin "S2") (pinfunction "S2_S2") (pintype "passive"))
    )
    (net (code "296") (name "Net-(D16-PadD2)") (class "Default")
      (node (ref "D16") (pin "D2") (pinfunction "D2_D2") (pintype "passive"))
      (node (ref "D16") (pin "E2") (pinfunction "E2_E2") (pintype "passive"))
    )
    (net (code "297") (name "Net-(D16D-D2)") (class "Default")
      (node (ref "D16") (pin "R2") (pinfunction "E2_R2") (pintype "passive"))
      (node (ref "D16") (pin "V2") (pinfunction "D2_V2") (pintype "passive"))
    )
    (net (code "298") (name "Net-(D16D-H1)") (class "Default")
      (node (ref "D16") (pin "S1") (pinfunction "H1_S1") (pintype "passive"))
      (node (ref "D16") (pin "S2") (pinfunction "L2_S2") (pintype "passive"))
    )
    (net (code "299") (name "Net-(D17-PadD2)") (class "Default")
      (node (ref "D17") (pin "D2") (pinfunction "D2_D2") (pintype "passive"))
      (node (ref "D17") (pin "E2") (pinfunction "E2_E2") (pintype "passive"))
    )
    (net (code "300") (name "Net-(D17C-D2)") (class "Default")
      (node (ref "D17") (pin "R2") (pinfunction "E2_R2") (pintype "passive"))
      (node (ref "D17") (pin "S2") (pinfunction "D2_S2") (pintype "passive"))
    )
    (net (code "301") (name "PAR") (class "Default")
      (node (ref "A08") (pin "U1") (pinfunction "0_U1") (pintype "output"))
      (node (ref "A25") (pin "T1") (pinfunction "P$2_T1") (pintype "bidirectional"))
    )
    (net (code "302") (name "PC+ES") (class "Default")
      (node (ref "A11") (pin "H2") (pinfunction "IN_H2") (pintype "input"))
      (node (ref "A12") (pin "C1") (pinfunction "OUT_C1") (pintype "output"))
    )
    (net (code "303") (name "PWR_CLR") (class "Default")
      (node (ref "C06") (pin "R2") (pinfunction "OUT_R2") (pintype "output"))
    )
    (net (code "304") (name "RD+WD") (class "Default")
      (node (ref "A09") (pin "P1") (pinfunction "IN3_P1") (pintype "input"))
      (node (ref "B08") (pin "N2") (pinfunction "OUT_N2") (pintype "output"))
      (node (ref "B12") (pin "D2") (pinfunction "IN1_D2") (pintype "input"))
      (node (ref "C12") (pin "R1") (pinfunction "IN2_R1") (pintype "input"))
    )
    (net (code "305") (name "RDD_00") (class "Default")
      (node (ref "A21") (pin "U2") (pinfunction "U2_U2") (pintype "output"))
      (node (ref "B09") (pin "M2") (pinfunction "D_M2") (pintype "input"))
      (node (ref "D09") (pin "C1") (pinfunction "IN2A_C1") (pintype "input"))
      (node (ref "D09") (pin "F2") (pinfunction "IN2A_F2") (pintype "input"))
    )
    (net (code "306") (name "RDD_01") (class "Default")
      (node (ref "B09") (pin "P1") (pinfunction "D_P1") (pintype "input"))
      (node (ref "B20") (pin "U2") (pinfunction "U2_U2") (pintype "output"))
      (node (ref "D09") (pin "J1") (pinfunction "IN2A_J1") (pintype "input"))
      (node (ref "D09") (pin "M2") (pinfunction "IN2A_M2") (pintype "input"))
    )
    (net (code "307") (name "RDD_02") (class "Default")
      (node (ref "A20") (pin "U2") (pinfunction "U2_U2") (pintype "output"))
      (node (ref "B09") (pin "E2") (pinfunction "D_E2") (pintype "input"))
      (node (ref "D09") (pin "P1") (pinfunction "IN2A_P1") (pintype "input"))
      (node (ref "D09") (pin "T2") (pinfunction "IN2A_T2") (pintype "input"))
    )
    (net (code "308") (name "RDMK") (class "Default")
      (node (ref "B18") (pin "U2") (pinfunction "U2_U2") (pintype "output"))
      (node (ref "CD18") (pin "AS2") (pinfunction "AS2_AS2") (pintype "input"))
    )
    (net (code "309") (name "RD_EN") (class "Default")
      (node (ref "C11") (pin "J1") (pinfunction "IN2_J1") (pintype "input"))
      (node (ref "C11") (pin "N2") (pinfunction "OUT_N2") (pintype "output"))
    )
    (net (code "310") (name "RD_EN_LPB_00-02") (class "Default")
      (node (ref "C10") (pin "D2") (pinfunction "IN1A_D2") (pintype "input"))
      (node (ref "C13") (pin "T2") (pinfunction "OUT_T2") (pintype "output"))
      (node (ref "D09") (pin "D1") (pinfunction "IN2B_D1") (pintype "input"))
      (node (ref "D09") (pin "K1") (pinfunction "IN2B_K1") (pintype "input"))
      (node (ref "D09") (pin "R1") (pinfunction "IN2B_R1") (pintype "input"))
    )
    (net (code "311") (name "RD_EN_LPB_03-05") (class "Default")
      (node (ref "C10") (pin "R2") (pinfunction "IN1A_R2") (pintype "input"))
      (node (ref "C13") (pin "R2") (pinfunction "OUT_R2") (pintype "output"))
      (node (ref "D09") (pin "H2") (pinfunction "IN2B_H2") (pintype "input"))
      (node (ref "D09") (pin "N2") (pinfunction "IN2B_N2") (pintype "input"))
      (node (ref "D09") (pin "U2") (pinfunction "IN2B_U2") (pintype "input"))
    )
    (net (code "312") (name "READ_ALL") (class "Default")
      (node (ref "D07") (pin "N2") (pinfunction "O3_N2") (pintype "output"))
    )
    (net (code "313") (name "READ_DATA") (class "Default")
      (node (ref "A10") (pin "L1") (pinfunction "IN1_L1") (pintype "input"))
      (node (ref "C11") (pin "H1") (pinfunction "IN1_H1") (pintype "input"))
      (node (ref "D07") (pin "J2") (pinfunction "O2_J2") (pintype "output"))
    )
    (net (code "314") (name "RSTA") (class "Default")
      (node (ref "C04") (pin "A1") (pinfunction "A1_A1") (pintype "output"))
    )
    (net (code "315") (name "RSTB") (class "Default")
      (node (ref "C05") (pin "C1") (pinfunction "C1_C1") (pintype "output"))
    )
    (net (code "316") (name "SE") (class "Default")
      (node (ref "D07") (pin "L2") (pinfunction "O7_L2") (pintype "output"))
    )
    (net (code "317") (name "SEARCH") (class "Default")
      (node (ref "C11") (pin "D2") (pinfunction "IN1_D2") (pintype "input"))
      (node (ref "D07") (pin "E2") (pinfunction "O1_E2") (pintype "output"))
    )
    (net (code "318") (name "SEL") (class "Default")
      (node (ref "A08") (pin "H2") (pinfunction "1_H2") (pintype "output"))
      (node (ref "A25") (pin "S1") (pinfunction "P$2_S1") (pintype "bidirectional"))
    )
    (net (code "319") (name "SHIFT_CK") (class "Default")
      (node (ref "C17") (pin "K1") (pinfunction "OUT_K1") (pintype "output"))
      (node (ref "CD18") (pin "BR2") (pinfunction "BR2_BR2") (pintype "input"))
    )
    (net (code "320") (name "SH_DTB") (class "Default")
      (node (ref "A10") (pin "R2") (pinfunction "IN2_R2") (pintype "input"))
      (node (ref "B09") (pin "B1") (pinfunction "C_B1") (pintype "input"))
      (node (ref "B09") (pin "D2") (pinfunction "C_D2") (pintype "input"))
      (node (ref "B09") (pin "H1") (pinfunction "C_H1") (pintype "input"))
      (node (ref "B09") (pin "L2") (pinfunction "C_L2") (pintype "input"))
      (node (ref "B09") (pin "N1") (pinfunction "C_N1") (pintype "input"))
      (node (ref "B09") (pin "S2") (pinfunction "C_S2") (pintype "input"))
      (node (ref "B10") (pin "E1") (pinfunction "OUT_E1") (pintype "output"))
      (node (ref "C09") (pin "B1") (pinfunction "C_B1") (pintype "input"))
      (node (ref "C09") (pin "D2") (pinfunction "C_D2") (pintype "input"))
      (node (ref "C09") (pin "H1") (pinfunction "C_H1") (pintype "input"))
      (node (ref "C09") (pin "L2") (pinfunction "C_L2") (pintype "input"))
      (node (ref "C09") (pin "N1") (pinfunction "C_N1") (pintype "input"))
      (node (ref "C09") (pin "S2") (pinfunction "C_S2") (pintype "input"))
    )
    (net (code "321") (name "SH_EN") (class "Default")
      (node (ref "A11") (pin "N2") (pinfunction "OUT_N2") (pintype "output"))
      (node (ref "A12") (pin "E2") (pinfunction "IN2_E2") (pintype "input"))
      (node (ref "C10") (pin "A1") (pinfunction "IN1A_A1") (pintype "input"))
      (node (ref "C10") (pin "F1") (pinfunction "IN1A_F1") (pintype "input"))
      (node (ref "C10") (pin "M1") (pinfunction "IN1A_M1") (pintype "input"))
    )
    (net (code "322") (name "SH_ST") (class "Default")
      (node (ref "C17") (pin "A1") (pinfunction "IN_A1") (pintype "input"))
      (node (ref "CD18") (pin "AM1") (pinfunction "AM1_AM1") (pintype "output"))
    )
    (net (code "323") (name "SH_ST-B") (class "Default")
      (node (ref "C16") (pin "P2") (pinfunction "OUT_P2") (pintype "output"))
      (node (ref "CD18") (pin "BC1") (pinfunction "BC1_BC1") (pintype "input"))
    )
    (net (code "324") (name "SINGLE_UNIT") (class "Default")
      (node (ref "A09") (pin "K1") (pinfunction "IN4_K1") (pintype "input"))
      (node (ref "B21") (pin "U2") (pinfunction "OUT_U2") (pintype "output"))
    )
    (net (code "325") (name "SP_DY") (class "Default")
      (node (ref "D14") (pin "H2") (pinfunction "H2_H2") (pintype "output"))
    )
    (net (code "326") (name "ST_BLK_MK") (class "Default")
      (node (ref "A26") (pin "K1") (pinfunction "P$2_K1") (pintype "bidirectional"))
      (node (ref "C13") (pin "E2") (pinfunction "IN_E2") (pintype "input"))
      (node (ref "CD18") (pin "AR2") (pinfunction "AR2_AR2") (pintype "output"))
    )
    (net (code "327") (name "ST_CK") (class "Default")
      (node (ref "A10") (pin "P1") (pinfunction "IN1_P1") (pintype "input"))
      (node (ref "A26") (pin "P1") (pinfunction "P$2_P1") (pintype "bidirectional"))
      (node (ref "C13") (pin "J1") (pinfunction "IN_J1") (pintype "input"))
      (node (ref "CD18") (pin "BR1") (pinfunction "BR1_BR1") (pintype "output"))
      (node (ref "D17") (pin "M2") (pinfunction "K2_M2") (pintype "input"))
      (node (ref "D17") (pin "N2") (pinfunction "J2_N2") (pintype "input"))
      (node (ref "D17") (pin "P2") (pinfunction "H2_P2") (pintype "input"))
    )
    (net (code "328") (name "ST_CK_0P") (class "Default")
      (node (ref "B12") (pin "H2") (pinfunction "IN4_H2") (pintype "input"))
      (node (ref "C12") (pin "S1") (pinfunction "IN3_S1") (pintype "input"))
      (node (ref "C13") (pin "B1") (pinfunction "OUT_B1") (pintype "output"))
    )
    (net (code "329") (name "ST_DATA") (class "Default")
      (node (ref "B12") (pin "A1") (pinfunction "IN1_A1") (pintype "input"))
      (node (ref "C13") (pin "H2") (pinfunction "IN_H2") (pintype "input"))
      (node (ref "C16") (pin "J2") (pinfunction "OUT_J2") (pintype "output"))
    )
    (net (code "330") (name "ST_FINAL") (class "Default")
      (node (ref "A09") (pin "S2") (pinfunction "IN2_S2") (pintype "input"))
      (node (ref "A26") (pin "N1") (pinfunction "P$2_N1") (pintype "bidirectional"))
      (node (ref "C11") (pin "D1") (pinfunction "IN1_D1") (pintype "input"))
      (node (ref "C13") (pin "L1") (pinfunction "IN_L1") (pintype "input"))
      (node (ref "CD18") (pin "BL2") (pinfunction "BL2_BL2") (pintype "output"))
    )
    (net (code "331") (name "ST_IDLE") (class "Default")
      (node (ref "A26") (pin "R1") (pinfunction "P$2_R1") (pintype "bidirectional"))
      (node (ref "C13") (pin "K2") (pinfunction "IN_K2") (pintype "input"))
      (node (ref "CD18") (pin "AN2") (pinfunction "AN2_AN2") (pintype "output"))
      (node (ref "CD18") (pin "BD2") (pinfunction "BD2_BD2") (pintype "input"))
    )
    (net (code "332") (name "ST_REV_CK") (class "Default")
      (node (ref "A26") (pin "L1") (pinfunction "P$2_L1") (pintype "bidirectional"))
      (node (ref "B11") (pin "S1") (pinfunction "IN3_S1") (pintype "input"))
      (node (ref "C11") (pin "A1") (pinfunction "IN1_A1") (pintype "input"))
      (node (ref "C13") (pin "D1") (pinfunction "IN_D1") (pintype "input"))
      (node (ref "CD18") (pin "BS1") (pinfunction "BS1_BS1") (pintype "output"))
      (node (ref "D12") (pin "F2") (pinfunction "IN3_F2") (pintype "input"))
      (node (ref "D12") (pin "H2") (pinfunction "IN4_H2") (pintype "input"))
    )
    (net (code "333") (name "SWTM") (class "Default")
      (node (ref "A26") (pin "V2") (pinfunction "P$2_V2") (pintype "bidirectional"))
      (node (ref "B06") (pin "P2") (pinfunction "IN_P2") (pintype "input"))
      (node (ref "B08") (pin "V1") (pinfunction "P$1_V1") (pintype "passive"))
      (node (ref "B11") (pin "B1") (pinfunction "IN2_B1") (pintype "input"))
      (node (ref "C10") (pin "N2") (pinfunction "IN2B_N2") (pintype "input"))
      (node (ref "C12") (pin "P2") (pinfunction "IN2_P2") (pintype "input"))
      (node (ref "C15") (pin "L1") (pinfunction "IN1_L1") (pintype "input"))
    )
    (net (code "334") (name "SYNC") (class "Default")
      (node (ref "B10") (pin "D2") (pinfunction "IN1_D2") (pintype "input"))
      (node (ref "B10") (pin "E2") (pinfunction "IN2_E2") (pintype "input"))
      (node (ref "CD18") (pin "BN2") (pinfunction "BN2_BN2") (pintype "output"))
    )
    (net (code "335") (name "SYNC_EN") (class "Default")
      (node (ref "B11") (pin "M2") (pinfunction "OUT_M2") (pintype "output"))
      (node (ref "CD18") (pin "BH1") (pinfunction "BH1_BH1") (pintype "input"))
    )
    (net (code "336") (name "T3") (class "Default")
      (node (ref "C17") (pin "S1") (pinfunction "OUT_S1") (pintype "output"))
      (node (ref "D12") (pin "N1") (pinfunction "IN2_N1") (pintype "input"))
      (node (ref "D12") (pin "P1") (pinfunction "IN3_P1") (pintype "input"))
    )
    (net (code "337") (name "TIM") (class "Default")
      (node (ref "A08") (pin "L1") (pinfunction "1_L1") (pintype "output"))
      (node (ref "A25") (pin "U1") (pinfunction "P$2_U1") (pintype "bidirectional"))
    )
    (net (code "338") (name "TM_EN") (class "Default")
      (node (ref "A18") (pin "R2") (pinfunction "R2_R2") (pintype "input"))
      (node (ref "B18") (pin "R2") (pinfunction "R2_R2") (pintype "input"))
      (node (ref "C13") (pin "N1") (pinfunction "IN_N1") (pintype "input"))
      (node (ref "C15") (pin "S1") (pinfunction "OUT_S1") (pintype "output"))
      (node (ref "C16") (pin "M1") (pinfunction "IN1_M1") (pintype "input"))
      (node (ref "C16") (pin "R2") (pinfunction "IN1_R2") (pintype "input"))
    )
    (net (code "339") (name "TP00") (class "Default")
      (node (ref "A08") (pin "B1") (pinfunction "C_B1") (pintype "input"))
      (node (ref "A15") (pin "L1") (pinfunction "OUT_L1") (pintype "output"))
      (node (ref "A16") (pin "M2") (pinfunction "K2_M2") (pintype "input"))
      (node (ref "A16") (pin "N2") (pinfunction "J2_N2") (pintype "input"))
      (node (ref "A16") (pin "P2") (pinfunction "H2_P2") (pintype "input"))
      (node (ref "B10") (pin "F2") (pinfunction "IN3_F2") (pintype "input"))
      (node (ref "B10") (pin "H2") (pinfunction "IN4_H2") (pintype "input"))
      (node (ref "B10") (pin "N1") (pinfunction "IN2_N1") (pintype "input"))
      (node (ref "B13") (pin "B1") (pinfunction "C_B1") (pintype "input"))
      (node (ref "B13") (pin "D2") (pinfunction "C_D2") (pintype "input"))
      (node (ref "B13") (pin "H1") (pinfunction "C_H1") (pintype "input"))
      (node (ref "B15") (pin "J1") (pinfunction "IN2_J1") (pintype "input"))
      (node (ref "C15") (pin "E1") (pinfunction "IN2_E1") (pintype "input"))
    )
    (net (code "340") (name "TP00_A") (class "Default")
      (node (ref "A15") (pin "S1") (pinfunction "OUT_S1") (pintype "output"))
      (node (ref "B10") (pin "H1") (pinfunction "IN2_H1") (pintype "input"))
      (node (ref "C12") (pin "E2") (pinfunction "IN2_E2") (pintype "input"))
    )
    (net (code "341") (name "TP01") (class "Default")
      (node (ref "A12") (pin "J2") (pinfunction "IN2_J2") (pintype "input"))
      (node (ref "A15") (pin "P2") (pinfunction "OUT_P2") (pintype "output"))
      (node (ref "B16") (pin "M2") (pinfunction "K2_M2") (pintype "input"))
      (node (ref "B16") (pin "N2") (pinfunction "J2_N2") (pintype "input"))
      (node (ref "B16") (pin "P2") (pinfunction "H2_P2") (pintype "input"))
      (node (ref "C11") (pin "J2") (pinfunction "IN2_J2") (pintype "input"))
      (node (ref "C15") (pin "B1") (pinfunction "IN2_B1") (pintype "input"))
      (node (ref "CD18") (pin "BF1") (pinfunction "BF1_BF1") (pintype "input"))
    )
    (net (code "342") (name "TP01_A") (class "Default")
      (node (ref "A15") (pin "V2") (pinfunction "OUT_V2") (pintype "output"))
      (node (ref "B12") (pin "T2") (pinfunction "IN3_T2") (pintype "input"))
      (node (ref "C15") (pin "M2") (pinfunction "IN2_M2") (pintype "input"))
    )
    (net (code "343") (name "T_TRK") (class "Default")
      (node (ref "A18") (pin "U2") (pinfunction "U2_U2") (pintype "output"))
      (node (ref "B15") (pin "E2") (pinfunction "IN2_E2") (pintype "input"))
      (node (ref "C15") (pin "R2") (pinfunction "IN2_R2") (pintype "input"))
      (node (ref "D14") (pin "S1") (pinfunction "S1_S1") (pintype "input"))
      (node (ref "D14") (pin "U1") (pinfunction "U1_U1") (pintype "input"))
    )
    (net (code "344") (name "U+M_DY") (class "Default")
      (node (ref "D14") (pin "K1") (pinfunction "H2_K1") (pintype "output"))
    )
    (net (code "345") (name "USR_00") (class "Default")
      (node (ref "A07") (pin "V2") (pinfunction "IN2_V2") (pintype "input"))
      (node (ref "A25") (pin "A1") (pinfunction "P$2_A1") (pintype "bidirectional"))
      (node (ref "B07") (pin "E1") (pinfunction "E1_E1") (pintype "output"))
    )
    (net (code "346") (name "USR_01") (class "Default")
      (node (ref "A07") (pin "U2") (pinfunction "IN1_U2") (pintype "input"))
      (node (ref "A25") (pin "B1") (pinfunction "P$2_B1") (pintype "bidirectional"))
      (node (ref "B07") (pin "H2") (pinfunction "H2_H2") (pintype "output"))
    )
    (net (code "347") (name "USR_02") (class "Default")
      (node (ref "A07") (pin "V1") (pinfunction "IN0_V1") (pintype "input"))
      (node (ref "A25") (pin "C1") (pinfunction "P$2_C1") (pintype "bidirectional"))
      (node (ref "B07") (pin "L1") (pinfunction "L1_L1") (pintype "output"))
    )
    (net (code "348") (name "UTS") (class "Default")
      (node (ref "A10") (pin "E1") (pinfunction "IN2_E1") (pintype "input"))
      (node (ref "A26") (pin "J1") (pinfunction "P$2_J1") (pintype "bidirectional"))
      (node (ref "B15") (pin "P1") (pinfunction "IN1_P1") (pintype "input"))
      (node (ref "C14") (pin "R2") (pinfunction "0_R2") (pintype "output"))
    )
    (net (code "349") (name "VCC") (class "Default")
      (node (ref "AB01") (pin "AA2") (pinfunction "VCC_AA2") (pintype "power_in"))
      (node (ref "AB01") (pin "AB1") (pinfunction "VCC_AB1") (pintype "power_in"))
      (node (ref "AB01") (pin "AC1") (pinfunction "VCC_AC1") (pintype "power_in"))
      (node (ref "AB01") (pin "AD1") (pinfunction "VCC_AD1") (pintype "power_in"))
      (node (ref "AB01") (pin "AE1") (pinfunction "VCC_AE1") (pintype "power_in"))
      (node (ref "AB01") (pin "AF1") (pinfunction "VCC_AF1") (pintype "power_in"))
      (node (ref "AB01") (pin "AH1") (pinfunction "VCC_AH1") (pintype "power_in"))
      (node (ref "AB01") (pin "AJ1") (pinfunction "VCC_AJ1") (pintype "power_in"))
      (node (ref "AB01") (pin "AK1") (pinfunction "VCC_AK1") (pintype "power_in"))
      (node (ref "AB01") (pin "AL1") (pinfunction "VCC_AL1") (pintype "power_in"))
      (node (ref "AB01") (pin "BA2") (pinfunction "VCC_BA2") (pintype "power_in"))
      (node (ref "AB01") (pin "BB1") (pinfunction "VCC_BB1") (pintype "power_in"))
      (node (ref "AB01") (pin "BC1") (pinfunction "VCC_BC1") (pintype "power_in"))
      (node (ref "AB01") (pin "BD1") (pinfunction "VCC_BD1") (pintype "power_in"))
      (node (ref "AB01") (pin "BE1") (pinfunction "VCC_BE1") (pintype "power_in"))
    )
    (net (code "350") (name "W+UTS") (class "Default")
      (node (ref "A15") (pin "A1") (pinfunction "IN1_A1") (pintype "input"))
      (node (ref "A15") (pin "H2") (pinfunction "IN4_H2") (pintype "input"))
      (node (ref "C12") (pin "M2") (pinfunction "OUT_M2") (pintype "output"))
    )
    (net (code "351") (name "W-INH") (class "Default")
      (node (ref "A08") (pin "V1") (pinfunction "0_V1") (pintype "output"))
    )
    (net (code "352") (name "W01") (class "Default")
      (node (ref "A26") (pin "J2") (pinfunction "P$2_J2") (pintype "bidirectional"))
      (node (ref "CD18") (pin "BJ2") (pinfunction "BJ2_BJ2") (pintype "output"))
    )
    (net (code "353") (name "W01-W05") (class "Default")
      (node (ref "CD18") (pin "AK1") (pinfunction "AK1_AK1") (pintype "output"))
    )
    (net (code "354") (name "W02") (class "Default")
      (node (ref "A26") (pin "K2") (pinfunction "P$2_K2") (pintype "bidirectional"))
      (node (ref "CD18") (pin "BV2") (pinfunction "BV2_BV2") (pintype "output"))
    )
    (net (code "355") (name "W03") (class "Default")
      (node (ref "A26") (pin "L2") (pinfunction "P$2_L2") (pintype "bidirectional"))
      (node (ref "CD18") (pin "BE2") (pinfunction "BE2_BE2") (pintype "output"))
    )
    (net (code "356") (name "W04") (class "Default")
      (node (ref "A26") (pin "M2") (pinfunction "P$2_M2") (pintype "bidirectional"))
      (node (ref "CD18") (pin "AT2") (pinfunction "AT2_AT2") (pintype "output"))
    )
    (net (code "357") (name "W05") (class "Default")
      (node (ref "A26") (pin "N2") (pinfunction "P$2_N2") (pintype "bidirectional"))
      (node (ref "CD18") (pin "BU2") (pinfunction "BU2_BU2") (pintype "output"))
    )
    (net (code "358") (name "W06") (class "Default")
      (node (ref "A26") (pin "P2") (pinfunction "P$2_P2") (pintype "bidirectional"))
      (node (ref "CD18") (pin "AM2") (pinfunction "AM2_AM2") (pintype "output"))
    )
    (net (code "359") (name "W07") (class "Default")
      (node (ref "A26") (pin "R2") (pinfunction "P$2_R2") (pintype "bidirectional"))
      (node (ref "CD18") (pin "AK2") (pinfunction "AK2_AK2") (pintype "output"))
    )
    (net (code "360") (name "W08") (class "Default")
      (node (ref "A26") (pin "S2") (pinfunction "P$2_S2") (pintype "bidirectional"))
      (node (ref "CD18") (pin "AL1") (pinfunction "AL1_AL1") (pintype "output"))
    )
    (net (code "361") (name "W09") (class "Default")
      (node (ref "A26") (pin "T2") (pinfunction "P$2_T2") (pintype "bidirectional"))
      (node (ref "CD18") (pin "BF2") (pinfunction "BF2_BF2") (pintype "output"))
    )
    (net (code "362") (name "WB00") (class "Default")
      (node (ref "A21") (pin "N2") (pinfunction "N2_N2") (pintype "input"))
      (node (ref "A25") (pin "P2") (pinfunction "P$2_P2") (pintype "bidirectional"))
      (node (ref "B18") (pin "N2") (pinfunction "N2_N2") (pintype "input"))
      (node (ref "C14") (pin "F1") (pinfunction "0_F1") (pintype "output"))
      (node (ref "D09") (pin "A1") (pinfunction "IN1A_A1") (pintype "input"))
    )
    (net (code "363") (name "WB01") (class "Default")
      (node (ref "A25") (pin "R2") (pinfunction "P$2_R2") (pintype "bidirectional"))
      (node (ref "B20") (pin "N2") (pinfunction "N2_N2") (pintype "input"))
      (node (ref "C14") (pin "J2") (pinfunction "0_J2") (pintype "output"))
      (node (ref "D09") (pin "F1") (pinfunction "IN1A_F1") (pintype "input"))
    )
    (net (code "364") (name "WB02") (class "Default")
      (node (ref "A20") (pin "N2") (pinfunction "N2_N2") (pintype "input"))
      (node (ref "A25") (pin "S2") (pinfunction "P$2_S2") (pintype "bidirectional"))
      (node (ref "C14") (pin "M1") (pinfunction "0_M1") (pintype "output"))
      (node (ref "D09") (pin "M1") (pinfunction "IN1A_M1") (pintype "input"))
    )
    (net (code "365") (name "WC") (class "Default")
      (node (ref "A26") (pin "H1") (pinfunction "P$2_H1") (pintype "bidirectional"))
      (node (ref "B10") (pin "M1") (pinfunction "IN1_M1") (pintype "input"))
      (node (ref "B11") (pin "K1") (pinfunction "IN1_K1") (pintype "input"))
      (node (ref "D11") (pin "U1") (pinfunction "0_U1") (pintype "output"))
    )
    (net (code "366") (name "WC0") (class "Default")
      (node (ref "C01") (pin "H1") (pinfunction "OUT_H1") (pintype "output"))
      (node (ref "C06") (pin "M2") (pinfunction "IN_M2") (pintype "input"))
    )
    (net (code "367") (name "WRITE_ALL") (class "Default")
      (node (ref "A08") (pin "S2") (pinfunction "C_S2") (pintype "input"))
      (node (ref "B11") (pin "M1") (pinfunction "IN3_M1") (pintype "input"))
      (node (ref "B12") (pin "F1") (pinfunction "IN1_F1") (pintype "input"))
      (node (ref "D07") (pin "M2") (pinfunction "O5_M2") (pintype "output"))
    )
    (net (code "368") (name "WRITE_DATA") (class "Default")
      (node (ref "A09") (pin "R2") (pinfunction "IN1_R2") (pintype "input"))
      (node (ref "B11") (pin "R1") (pinfunction "IN2_R1") (pintype "input"))
      (node (ref "B12") (pin "B1") (pinfunction "IN2_B1") (pintype "input"))
      (node (ref "B12") (pin "P1") (pinfunction "IN3_P1") (pintype "input"))
      (node (ref "D07") (pin "F2") (pinfunction "O4_F2") (pintype "output"))
    )
    (net (code "369") (name "WRITE_OK") (class "Default")
      (node (ref "A22") (pin "D2") (pinfunction "D2_D2") (pintype "output"))
      (node (ref "B11") (pin "C1") (pinfunction "IN3_C1") (pintype "input"))
      (node (ref "B15") (pin "R1") (pinfunction "IN2_R1") (pintype "input"))
      (node (ref "C17") (pin "H2") (pinfunction "IN_H2") (pintype "input"))
    )
    (net (code "370") (name "WRITE_OK+UTS") (class "Default")
      (node (ref "B12") (pin "D1") (pinfunction "IN4_D1") (pintype "input"))
      (node (ref "B12") (pin "K1") (pinfunction "IN4_K1") (pintype "input"))
      (node (ref "C17") (pin "M1") (pinfunction "OUT_M1") (pintype "output"))
    )
    (net (code "371") (name "WRTM") (class "Default")
      (node (ref "B11") (pin "A1") (pinfunction "IN1_A1") (pintype "input"))
      (node (ref "C10") (pin "K2") (pinfunction "IN1A_K2") (pintype "input"))
      (node (ref "C12") (pin "N2") (pinfunction "IN1_N2") (pintype "input"))
      (node (ref "D07") (pin "H2") (pinfunction "O6_H2") (pintype "output"))
    )
    (net (code "372") (name "WRTM+FR03") (class "Default")
      (node (ref "B08") (pin "K2") (pinfunction "OUT_K2") (pintype "output"))
      (node (ref "C12") (pin "M1") (pinfunction "IN3_M1") (pintype "input"))
      (node (ref "C12") (pin "V2") (pinfunction "IN3_V2") (pintype "input"))
    )
    (net (code "373") (name "WR_EN") (class "Default")
      (node (ref "A20") (pin "R2") (pinfunction "R2_R2") (pintype "input"))
      (node (ref "A21") (pin "R2") (pinfunction "R2_R2") (pintype "input"))
      (node (ref "A26") (pin "F1") (pinfunction "P$2_F1") (pintype "bidirectional"))
      (node (ref "B20") (pin "R2") (pinfunction "R2_R2") (pintype "input"))
      (node (ref "C10") (pin "H2") (pinfunction "IN2B_H2") (pintype "input"))
      (node (ref "C10") (pin "U2") (pinfunction "IN2B_U2") (pintype "input"))
      (node (ref "C12") (pin "D2") (pinfunction "IN1_D2") (pintype "input"))
      (node (ref "C14") (pin "U1") (pinfunction "0_U1") (pintype "output"))
      (node (ref "C15") (pin "A1") (pinfunction "IN1_A1") (pintype "input"))
      (node (ref "C15") (pin "M1") (pinfunction "IN2_M1") (pintype "input"))
      (node (ref "D09") (pin "B1") (pinfunction "IN1B_B1") (pintype "input"))
      (node (ref "D09") (pin "E2") (pinfunction "IN1B_E2") (pintype "input"))
      (node (ref "D09") (pin "H1") (pinfunction "IN1B_H1") (pintype "input"))
      (node (ref "D09") (pin "L2") (pinfunction "IN1B_L2") (pintype "input"))
      (node (ref "D09") (pin "N1") (pinfunction "IN1B_N1") (pintype "input"))
      (node (ref "D09") (pin "S2") (pinfunction "IN1B_S2") (pintype "input"))
    )
    (net (code "374") (name "XOR_TO_LPB") (class "Default")
      (node (ref "C10") (pin "E2") (pinfunction "IN1B_E2") (pintype "input"))
      (node (ref "C10") (pin "F2") (pinfunction "IN2A_F2") (pintype "input"))
      (node (ref "C10") (pin "S2") (pinfunction "IN1B_S2") (pintype "input"))
      (node (ref "C10") (pin "T2") (pinfunction "IN2A_T2") (pintype "input"))
      (node (ref "D12") (pin "P2") (pinfunction "OUT_P2") (pintype "output"))
    )
    (net (code "375") (name "XSAD") (class "Default")
      (node (ref "A09") (pin "R1") (pinfunction "IN4_R1") (pintype "input"))
      (node (ref "A11") (pin "L2") (pinfunction "OUT_L2") (pintype "output"))
    )
    (net (code "376") (name "XSA_DY") (class "Default")
      (node (ref "A08") (pin "D2") (pinfunction "C_D2") (pintype "input"))
      (node (ref "B14") (pin "B1") (pinfunction "C_B1") (pintype "input"))
      (node (ref "B14") (pin "L2") (pinfunction "C_L2") (pintype "input"))
      (node (ref "C17") (pin "T2") (pinfunction "OUT_T2") (pintype "output"))
    )
    (net (code "377") (name "XSTA") (class "Default")
      (node (ref "B07") (pin "B1") (pinfunction "B1_B1") (pintype "input"))
      (node (ref "B07") (pin "D2") (pinfunction "D2_D2") (pintype "input"))
      (node (ref "B07") (pin "H1") (pinfunction "H1_H1") (pintype "input"))
      (node (ref "B07") (pin "L2") (pinfunction "L2_L2") (pintype "input"))
      (node (ref "B07") (pin "N1") (pinfunction "N1_N1") (pintype "input"))
      (node (ref "B07") (pin "S2") (pinfunction "S2_S2") (pintype "input"))
      (node (ref "C04") (pin "E1") (pinfunction "E1_E1") (pintype "output"))
      (node (ref "C07") (pin "B1") (pinfunction "B1_B1") (pintype "input"))
      (node (ref "C07") (pin "D2") (pinfunction "D2_D2") (pintype "input"))
      (node (ref "C07") (pin "H1") (pinfunction "H1_H1") (pintype "input"))
      (node (ref "C07") (pin "L2") (pinfunction "L2_L2") (pintype "input"))
      (node (ref "D11") (pin "N1") (pinfunction "C_N1") (pintype "input"))
      (node (ref "D13") (pin "M2") (pinfunction "K2_M2") (pintype "input"))
      (node (ref "D13") (pin "N2") (pinfunction "J2_N2") (pintype "input"))
      (node (ref "D13") (pin "P2") (pinfunction "H2_P2") (pintype "input"))
    )
    (net (code "378") (name "unconnected-(A07A-O8-PadP2)") (class "Default")
      (node (ref "A07") (pin "P2") (pinfunction "O8_P2") (pintype "output"))
    )
    (net (code "379") (name "unconnected-(A07A-O9-PadR2)") (class "Default")
      (node (ref "A07") (pin "R2") (pinfunction "O9_R2") (pintype "output"))
    )
    (net (code "380") (name "unconnected-(A07A-~{O8}-PadP1)") (class "Default")
      (node (ref "A07") (pin "P1") (pinfunction "~{O8}_P1") (pintype "output"))
    )
    (net (code "381") (name "unconnected-(A07A-~{O9}-PadR1)") (class "Default")
      (node (ref "A07") (pin "R1") (pinfunction "~{O9}_R1") (pintype "output"))
    )
    (net (code "382") (name "unconnected-(A14-PadD1)") (class "Default")
      (node (ref "A14") (pin "D1") (pinfunction "D1_D1") (pintype "passive"))
    )
    (net (code "383") (name "unconnected-(A14-PadE1)") (class "Default")
      (node (ref "A14") (pin "E1") (pinfunction "E1_E1") (pintype "passive"))
    )
    (net (code "384") (name "unconnected-(A14-PadF1)") (class "Default")
      (node (ref "A14") (pin "F1") (pinfunction "F1_F1") (pintype "passive"))
    )
    (net (code "385") (name "unconnected-(A14-PadJ1)") (class "Default")
      (node (ref "A14") (pin "J1") (pinfunction "J1_J1") (pintype "passive"))
    )
    (net (code "386") (name "unconnected-(A14D-D1-PadN1)") (class "Default")
      (node (ref "A14") (pin "N1") (pinfunction "D1_N1") (pintype "passive"))
    )
    (net (code "387") (name "unconnected-(A14D-E1-PadP1)") (class "Default")
      (node (ref "A14") (pin "P1") (pinfunction "E1_P1") (pintype "passive"))
    )
    (net (code "388") (name "unconnected-(A14D-F1-PadR1)") (class "Default")
      (node (ref "A14") (pin "R1") (pinfunction "F1_R1") (pintype "passive"))
    )
    (net (code "389") (name "unconnected-(A14D-J1-PadU1)") (class "Default")
      (node (ref "A14") (pin "U1") (pinfunction "J1_U1") (pintype "passive"))
    )
    (net (code "390") (name "unconnected-(A18-PadH2)") (class "Default")
      (node (ref "A18") (pin "H2") (pinfunction "H2_H2") (pintype "input"))
    )
    (net (code "391") (name "unconnected-(A18-PadL2)") (class "Default")
      (node (ref "A18") (pin "L2") (pinfunction "L2_L2") (pintype "input"))
    )
    (net (code "392") (name "unconnected-(A18-PadM2)") (class "Default")
      (node (ref "A18") (pin "M2") (pinfunction "M2_M2") (pintype "input"))
    )
    (net (code "393") (name "unconnected-(A20-PadH2)") (class "Default")
      (node (ref "A20") (pin "H2") (pinfunction "H2_H2") (pintype "input"))
    )
    (net (code "394") (name "unconnected-(A20-PadL2)") (class "Default")
      (node (ref "A20") (pin "L2") (pinfunction "L2_L2") (pintype "input"))
    )
    (net (code "395") (name "unconnected-(A20-PadM2)") (class "Default")
      (node (ref "A20") (pin "M2") (pinfunction "M2_M2") (pintype "input"))
    )
    (net (code "396") (name "unconnected-(A21-PadH2)") (class "Default")
      (node (ref "A21") (pin "H2") (pinfunction "H2_H2") (pintype "input"))
    )
    (net (code "397") (name "unconnected-(A21-PadL2)") (class "Default")
      (node (ref "A21") (pin "L2") (pinfunction "L2_L2") (pintype "input"))
    )
    (net (code "398") (name "unconnected-(A21-PadM2)") (class "Default")
      (node (ref "A21") (pin "M2") (pinfunction "M2_M2") (pintype "input"))
    )
    (net (code "399") (name "unconnected-(A22-PadE2)") (class "Default")
      (node (ref "A22") (pin "E2") (pinfunction "E2_E2") (pintype "passive"))
    )
    (net (code "400") (name "unconnected-(AB01-PadBM1)") (class "Default")
      (node (ref "AB01") (pin "BM1") (pinfunction "BM1_BM1") (pintype "output"))
    )
    (net (code "401") (name "unconnected-(AB01-PadBN1)") (class "Default")
      (node (ref "AB01") (pin "BN1") (pinfunction "BN1_BN1") (pintype "input"))
    )
    (net (code "402") (name "unconnected-(AB01-PadBP1)") (class "Default")
      (node (ref "AB01") (pin "BP1") (pinfunction "BP1_BP1") (pintype "input"))
    )
    (net (code "403") (name "unconnected-(AB01-PadBR1)") (class "Default")
      (node (ref "AB01") (pin "BR1") (pinfunction "BR1_BR1") (pintype "output"))
    )
    (net (code "404") (name "unconnected-(B05H-B-PadL2)") (class "Default")
      (node (ref "B05") (pin "L2") (pinfunction "B_L2") (pintype "input"))
    )
    (net (code "405") (name "unconnected-(B05H-E-PadP2)") (class "Default")
      (node (ref "B05") (pin "P2") (pinfunction "E_P2") (pintype "open_collector"))
    )
    (net (code "406") (name "unconnected-(B18-PadH2)") (class "Default")
      (node (ref "B18") (pin "H2") (pinfunction "H2_H2") (pintype "input"))
    )
    (net (code "407") (name "unconnected-(B18-PadL2)") (class "Default")
      (node (ref "B18") (pin "L2") (pinfunction "L2_L2") (pintype "input"))
    )
    (net (code "408") (name "unconnected-(B18-PadM2)") (class "Default")
      (node (ref "B18") (pin "M2") (pinfunction "M2_M2") (pintype "input"))
    )
    (net (code "409") (name "unconnected-(B20-PadH2)") (class "Default")
      (node (ref "B20") (pin "H2") (pinfunction "H2_H2") (pintype "input"))
    )
    (net (code "410") (name "unconnected-(B20-PadL2)") (class "Default")
      (node (ref "B20") (pin "L2") (pinfunction "L2_L2") (pintype "input"))
    )
    (net (code "411") (name "unconnected-(B20-PadM2)") (class "Default")
      (node (ref "B20") (pin "M2") (pinfunction "M2_M2") (pintype "input"))
    )
    (net (code "412") (name "unconnected-(B22K-A-PadR2)") (class "Default")
      (node (ref "B22") (pin "R2") (pinfunction "A_R2") (pintype "input"))
    )
    (net (code "413") (name "unconnected-(B22K-D-PadU2)") (class "Default")
      (node (ref "B22") (pin "U2") (pinfunction "D_U2") (pintype "output"))
    )
    (net (code "414") (name "unconnected-(C02A-IN13-PadP2)") (class "Default")
      (node (ref "C02") (pin "P2") (pinfunction "IN13_P2") (pintype "input"))
    )
    (net (code "415") (name "unconnected-(C02A-IN14-PadS2)") (class "Default")
      (node (ref "C02") (pin "S2") (pinfunction "IN14_S2") (pintype "input"))
    )
    (net (code "416") (name "unconnected-(C02A-O13-PadR2)") (class "Default")
      (node (ref "C02") (pin "R2") (pinfunction "O13_R2") (pintype "output"))
    )
    (net (code "417") (name "unconnected-(C02A-O14-PadT2)") (class "Default")
      (node (ref "C02") (pin "T2") (pinfunction "O14_T2") (pintype "output"))
    )
    (net (code "418") (name "unconnected-(C03A-IN13-PadP2)") (class "Default")
      (node (ref "C03") (pin "P2") (pinfunction "IN13_P2") (pintype "input"))
    )
    (net (code "419") (name "unconnected-(C03A-IN14-PadS2)") (class "Default")
      (node (ref "C03") (pin "S2") (pinfunction "IN14_S2") (pintype "input"))
    )
    (net (code "420") (name "unconnected-(C03A-IN15-PadU2)") (class "Default")
      (node (ref "C03") (pin "U2") (pinfunction "IN15_U2") (pintype "input"))
    )
    (net (code "421") (name "unconnected-(C03A-O13-PadR2)") (class "Default")
      (node (ref "C03") (pin "R2") (pinfunction "O13_R2") (pintype "output"))
    )
    (net (code "422") (name "unconnected-(C03A-O14-PadT2)") (class "Default")
      (node (ref "C03") (pin "T2") (pinfunction "O14_T2") (pintype "output"))
    )
    (net (code "423") (name "unconnected-(C03A-O15-PadV2)") (class "Default")
      (node (ref "C03") (pin "V2") (pinfunction "O15_V2") (pintype "output"))
    )
    (net (code "424") (name "unconnected-(C07-PadN1)") (class "Default")
      (node (ref "C07") (pin "N1") (pinfunction "N1_N1") (pintype "input"))
    )
    (net (code "425") (name "unconnected-(C07-PadP1)") (class "Default")
      (node (ref "C07") (pin "P1") (pinfunction "P1_P1") (pintype "input"))
    )
    (net (code "426") (name "unconnected-(C07-PadR1)") (class "Default")
      (node (ref "C07") (pin "R1") (pinfunction "R1_R1") (pintype "input"))
    )
    (net (code "427") (name "unconnected-(C07-PadS1)") (class "Default")
      (node (ref "C07") (pin "S1") (pinfunction "S1_S1") (pintype "output"))
    )
    (net (code "428") (name "unconnected-(C07-PadS2)") (class "Default")
      (node (ref "C07") (pin "S2") (pinfunction "S2_S2") (pintype "input"))
    )
    (net (code "429") (name "unconnected-(C07-PadT2)") (class "Default")
      (node (ref "C07") (pin "T2") (pinfunction "T2_T2") (pintype "input"))
    )
    (net (code "430") (name "unconnected-(C07-PadU1)") (class "Default")
      (node (ref "C07") (pin "U1") (pinfunction "U1_U1") (pintype "output"))
    )
    (net (code "431") (name "unconnected-(C07-PadU2)") (class "Default")
      (node (ref "C07") (pin "U2") (pinfunction "U2_U2") (pintype "input"))
    )
    (net (code "432") (name "unconnected-(C07-PadV1)") (class "Default")
      (node (ref "C07") (pin "V1") (pinfunction "V1_V1") (pintype "output"))
    )
    (net (code "433") (name "unconnected-(C07-PadV2)") (class "Default")
      (node (ref "C07") (pin "V2") (pinfunction "V2_V2") (pintype "output"))
    )
    (net (code "434") (name "unconnected-(CD18-PadAU1)") (class "Default")
      (node (ref "CD18") (pin "AU1") (pinfunction "AU1_AU1") (pintype "output"))
    )
    (net (code "435") (name "unconnected-(D07A-O8-PadP2)") (class "Default")
      (node (ref "D07") (pin "P2") (pinfunction "O8_P2") (pintype "output"))
    )
    (net (code "436") (name "unconnected-(D07A-O9-PadR2)") (class "Default")
      (node (ref "D07") (pin "R2") (pinfunction "O9_R2") (pintype "output"))
    )
    (net (code "437") (name "unconnected-(D07A-~{O8}-PadP1)") (class "Default")
      (node (ref "D07") (pin "P1") (pinfunction "~{O8}_P1") (pintype "output"))
    )
    (net (code "438") (name "unconnected-(D07A-~{O9}-PadR1)") (class "Default")
      (node (ref "D07") (pin "R1") (pinfunction "~{O9}_R1") (pintype "output"))
    )
    (net (code "439") (name "unconnected-(D13-PadD2)") (class "Default")
      (node (ref "D13") (pin "D2") (pinfunction "D2_D2") (pintype "passive"))
    )
    (net (code "440") (name "unconnected-(D13-PadE2)") (class "Default")
      (node (ref "D13") (pin "E2") (pinfunction "E2_E2") (pintype "passive"))
    )
    (net (code "441") (name "unconnected-(D14-PadN2)") (class "Default")
      (node (ref "D14") (pin "N2") (pinfunction "N2_N2") (pintype "passive"))
    )
    (net (code "442") (name "unconnected-(D14-PadP2)") (class "Default")
      (node (ref "D14") (pin "P2") (pinfunction "P2_P2") (pintype "passive"))
    )
    (net (code "443") (name "unconnected-(D14-PadR2)") (class "Default")
      (node (ref "D14") (pin "R2") (pinfunction "R2_R2") (pintype "passive"))
    )
    (net (code "444") (name "unconnected-(D14-PadS2)") (class "Default")
      (node (ref "D14") (pin "S2") (pinfunction "S2_S2") (pintype "passive"))
    )
    (net (code "445") (name "unconnected-(D14-PadU2)") (class "Default")
      (node (ref "D14") (pin "U2") (pinfunction "U2_U2") (pintype "passive"))
    )
    (net (code "446") (name "unconnected-(D14E-N2-PadJ1)") (class "Default")
      (node (ref "D14") (pin "J1") (pinfunction "N2_J1") (pintype "passive"))
    )
    (net (code "447") (name "unconnected-(D14E-R2-PadF1)") (class "Default")
      (node (ref "D14") (pin "F1") (pinfunction "R2_F1") (pintype "passive"))
    )
    (net (code "448") (name "unconnected-(D14E-S2-PadE1)") (class "Default")
      (node (ref "D14") (pin "E1") (pinfunction "S2_E1") (pintype "passive"))
    )
    (net (code "449") (name "unconnected-(D14E-U2-PadD1)") (class "Default")
      (node (ref "D14") (pin "D1") (pinfunction "U2_D1") (pintype "passive"))
    )
    (net (code "450") (name "unconnected-(D14E-V2-PadB1)") (class "Default")
      (node (ref "D14") (pin "B1") (pinfunction "V2_B1") (pintype "passive"))
    )
    (net (code "451") (name "unconnected-(D15-PadE2)") (class "Default")
      (node (ref "D15") (pin "E2") (pinfunction "E2_E2") (pintype "output"))
    )
    (net (code "452") (name "unconnected-(D15-PadM2)") (class "Default")
      (node (ref "D15") (pin "M2") (pinfunction "M2_M2") (pintype "passive"))
    )
    (net (code "453") (name "unconnected-(D15-PadP2)") (class "Default")
      (node (ref "D15") (pin "P2") (pinfunction "P2_P2") (pintype "passive"))
    )
    (net (code "454") (name "unconnected-(D15-PadR2)") (class "Default")
      (node (ref "D15") (pin "R2") (pinfunction "R2_R2") (pintype "passive"))
    )
    (net (code "455") (name "unconnected-(D15-PadT2)") (class "Default")
      (node (ref "D15") (pin "T2") (pinfunction "T2_T2") (pintype "passive"))
    )
    (net (code "456") (name "unconnected-(D16-PadD1)") (class "Default")
      (node (ref "D16") (pin "D1") (pinfunction "D1_D1") (pintype "passive"))
    )
    (net (code "457") (name "unconnected-(D16-PadE1)") (class "Default")
      (node (ref "D16") (pin "E1") (pinfunction "E1_E1") (pintype "passive"))
    )
    (net (code "458") (name "unconnected-(D16-PadF1)") (class "Default")
      (node (ref "D16") (pin "F1") (pinfunction "F1_F1") (pintype "passive"))
    )
    (net (code "459") (name "unconnected-(D16-PadH1)") (class "Default")
      (node (ref "D16") (pin "H1") (pinfunction "H1_H1") (pintype "passive"))
    )
    (net (code "460") (name "unconnected-(D16-PadJ1)") (class "Default")
      (node (ref "D16") (pin "J1") (pinfunction "J1_J1") (pintype "passive"))
    )
    (net (code "461") (name "unconnected-(D16-PadL2)") (class "Default")
      (node (ref "D16") (pin "L2") (pinfunction "L2_L2") (pintype "passive"))
    )
    (net (code "462") (name "unconnected-(D16D-D1-PadN1)") (class "Default")
      (node (ref "D16") (pin "N1") (pinfunction "D1_N1") (pintype "passive"))
    )
    (net (code "463") (name "unconnected-(D16D-E1-PadP1)") (class "Default")
      (node (ref "D16") (pin "P1") (pinfunction "E1_P1") (pintype "passive"))
    )
    (net (code "464") (name "unconnected-(D16D-F1-PadR1)") (class "Default")
      (node (ref "D16") (pin "R1") (pinfunction "F1_R1") (pintype "passive"))
    )
    (net (code "465") (name "unconnected-(D16D-J1-PadU1)") (class "Default")
      (node (ref "D16") (pin "U1") (pinfunction "J1_U1") (pintype "passive"))
    )
    (net (code "466") (name "~{0_TO_AC}") (class "Default")
      (node (ref "B05") (pin "H1") (pinfunction "B_H1") (pintype "input"))
      (node (ref "B06") (pin "T2") (pinfunction "OUT_T2") (pintype "output"))
    )
    (net (code "467") (name "~{0_TO_DTB}") (class "Default")
      (node (ref "A11") (pin "L1") (pinfunction "IN_L1") (pintype "input"))
      (node (ref "B09") (pin "A1") (pinfunction "R_A1") (pintype "input"))
      (node (ref "B09") (pin "K2") (pinfunction "R_K2") (pintype "input"))
      (node (ref "B10") (pin "L1") (pinfunction "OUT_L1") (pintype "output"))
      (node (ref "C09") (pin "A1") (pinfunction "R_A1") (pintype "input"))
      (node (ref "C09") (pin "K2") (pinfunction "R_K2") (pintype "input"))
    )
    (net (code "468") (name "~{0_TO_EF}") (class "Default")
      (node (ref "A08") (pin "A1") (pinfunction "R_A1") (pintype "input"))
      (node (ref "A08") (pin "N2") (pinfunction "S_N2") (pintype "input"))
      (node (ref "A08") (pin "R1") (pinfunction "S_R1") (pintype "input"))
      (node (ref "A11") (pin "F2") (pinfunction "OUT_F2") (pintype "output"))
    )
    (net (code "469") (name "~{0_TO_LPB}") (class "Default")
      (node (ref "D08") (pin "A1") (pinfunction "A1_A1") (pintype "input"))
      (node (ref "D08") (pin "K2") (pinfunction "K2_K2") (pintype "input"))
      (node (ref "D12") (pin "J2") (pinfunction "OUT_J2") (pintype "output"))
    )
    (net (code "470") (name "~{0_TO_STATE}") (class "Default")
      (node (ref "C16") (pin "L1") (pinfunction "OUT_L1") (pintype "output"))
      (node (ref "CD18") (pin "AV2") (pinfunction "AV2_AV2") (pintype "input"))
    )
    (net (code "471") (name "~{0_TO_STA}") (class "Default")
      (node (ref "A11") (pin "P1") (pinfunction "OUT_P1") (pintype "output"))
      (node (ref "B07") (pin "A1") (pinfunction "A1_A1") (pintype "input"))
      (node (ref "B07") (pin "K2") (pinfunction "K2_K2") (pintype "input"))
      (node (ref "B11") (pin "P2") (pinfunction "IN2_P2") (pintype "input"))
      (node (ref "C07") (pin "A1") (pinfunction "A1_A1") (pintype "input"))
    )
    (net (code "472") (name "~{0_TO_W}") (class "Default")
      (node (ref "C16") (pin "E1") (pinfunction "OUT_E1") (pintype "output"))
      (node (ref "CD18") (pin "BH2") (pinfunction "BH2_BH2") (pintype "input"))
    )
    (net (code "473") (name "~{00}") (class "Default")
      (node (ref "A07") (pin "D1") (pinfunction "~{O0}_D1") (pintype "output"))
      (node (ref "B22") (pin "S2") (pinfunction "B_S2") (pintype "input"))
    )
    (net (code "474") (name "~{01}") (class "Default")
      (node (ref "A07") (pin "E1") (pinfunction "~{O1}_E1") (pintype "output"))
      (node (ref "A23") (pin "N1") (pinfunction "B_N1") (pintype "input"))
    )
    (net (code "475") (name "~{02}") (class "Default")
      (node (ref "A07") (pin "J1") (pinfunction "~{O2}_J1") (pintype "output"))
      (node (ref "A23") (pin "D2") (pinfunction "A_D2") (pintype "input"))
    )
    (net (code "476") (name "~{03}") (class "Default")
      (node (ref "A07") (pin "N1") (pinfunction "~{O3}_N1") (pintype "output"))
      (node (ref "A23") (pin "E2") (pinfunction "B_E2") (pintype "input"))
    )
    (net (code "477") (name "~{04}") (class "Default")
      (node (ref "A07") (pin "F1") (pinfunction "~{O4}_F1") (pintype "output"))
      (node (ref "A23") (pin "K2") (pinfunction "A_K2") (pintype "input"))
    )
    (net (code "478") (name "~{05}") (class "Default")
      (node (ref "A07") (pin "M1") (pinfunction "~{O5}_M1") (pintype "output"))
      (node (ref "A23") (pin "L2") (pinfunction "B_L2") (pintype "input"))
    )
    (net (code "479") (name "~{06}") (class "Default")
      (node (ref "A07") (pin "H1") (pinfunction "~{O6}_H1") (pintype "output"))
      (node (ref "A23") (pin "R2") (pinfunction "A_R2") (pintype "input"))
    )
    (net (code "480") (name "~{07}") (class "Default")
      (node (ref "A07") (pin "L1") (pinfunction "~{O7}_L1") (pintype "output"))
      (node (ref "A23") (pin "S2") (pinfunction "B_S2") (pintype "input"))
    )
    (net (code "481") (name "~{76}") (class "Default")
      (node (ref "C06") (pin "T2") (pinfunction "OUT_T2") (pintype "output"))
      (node (ref "D12") (pin "R2") (pinfunction "IN1_R2") (pintype "input"))
      (node (ref "D12") (pin "S2") (pinfunction "IN2_S2") (pintype "input"))
    )
    (net (code "482") (name "~{77}") (class "Default")
      (node (ref "C06") (pin "V2") (pinfunction "OUT_V2") (pintype "output"))
      (node (ref "D12") (pin "T2") (pinfunction "IN3_T2") (pintype "input"))
      (node (ref "D12") (pin "U2") (pinfunction "IN4_U2") (pintype "input"))
    )
    (net (code "483") (name "~{ADDR_ACC}") (class "Default")
      (node (ref "B08") (pin "T2") (pinfunction "IN1_T2") (pintype "input"))
      (node (ref "C17") (pin "P1") (pinfunction "OUT_P1") (pintype "output"))
    )
    (net (code "484") (name "~{B-BRK}") (class "Default")
      (node (ref "B02") (pin "C1") (pinfunction "C_C1") (pintype "input"))
      (node (ref "B02") (pin "F2") (pinfunction "C_F2") (pintype "input"))
      (node (ref "B02") (pin "J1") (pinfunction "C_J1") (pintype "input"))
      (node (ref "B02") (pin "M2") (pinfunction "C_M2") (pintype "input"))
      (node (ref "B02") (pin "P1") (pinfunction "C_P1") (pintype "input"))
      (node (ref "B02") (pin "T2") (pinfunction "C_T2") (pintype "input"))
      (node (ref "B10") (pin "V2") (pinfunction "OUT_V2") (pintype "output"))
    )
    (net (code "485") (name "~{BAC_00}") (class "Default")
      (node (ref "B06") (pin "A1") (pinfunction "IN_A1") (pintype "input"))
      (node (ref "C03") (pin "B1") (pinfunction "O1_B1") (pintype "output"))
      (node (ref "D10") (pin "F1") (pinfunction "IN1_F1") (pintype "input"))
    )
    (net (code "486") (name "~{BAC_01}") (class "Default")
      (node (ref "B06") (pin "D1") (pinfunction "IN_D1") (pintype "input"))
      (node (ref "C03") (pin "E1") (pinfunction "O2_E1") (pintype "output"))
      (node (ref "D10") (pin "H1") (pinfunction "IN2_H1") (pintype "input"))
    )
    (net (code "487") (name "~{BAC_02}") (class "Default")
      (node (ref "B06") (pin "F1") (pinfunction "IN_F1") (pintype "input"))
      (node (ref "C03") (pin "H1") (pinfunction "O3_H1") (pintype "output"))
      (node (ref "D10") (pin "J1") (pinfunction "IN3_J1") (pintype "input"))
    )
    (net (code "488") (name "~{BAC_03}") (class "Default")
      (node (ref "B06") (pin "J1") (pinfunction "IN_J1") (pintype "input"))
      (node (ref "C03") (pin "K1") (pinfunction "O4_K1") (pintype "output"))
      (node (ref "D10") (pin "K1") (pinfunction "IN4_K1") (pintype "input"))
    )
    (net (code "489") (name "~{BAC_04}") (class "Default")
      (node (ref "B06") (pin "L1") (pinfunction "IN_L1") (pintype "input"))
      (node (ref "C03") (pin "M1") (pinfunction "O5_M1") (pintype "output"))
      (node (ref "D10") (pin "K2") (pinfunction "IN5_K2") (pintype "input"))
    )
    (net (code "490") (name "~{BAC_05}") (class "Default")
      (node (ref "B06") (pin "N1") (pinfunction "IN_N1") (pintype "input"))
      (node (ref "C03") (pin "P1") (pinfunction "O6_P1") (pintype "output"))
    )
    (net (code "491") (name "~{BAC_06}") (class "Default")
      (node (ref "B06") (pin "R1") (pinfunction "IN_R1") (pintype "input"))
      (node (ref "C03") (pin "S1") (pinfunction "O7_S1") (pintype "output"))
    )
    (net (code "492") (name "~{BAC_07}") (class "Default")
      (node (ref "B06") (pin "V1") (pinfunction "IN_V1") (pintype "input"))
      (node (ref "C03") (pin "U1") (pinfunction "O8_U1") (pintype "output"))
    )
    (net (code "493") (name "~{BAC_08}") (class "Default")
      (node (ref "B06") (pin "C1") (pinfunction "IN_C1") (pintype "input"))
      (node (ref "C03") (pin "F2") (pinfunction "O9_F2") (pintype "output"))
    )
    (net (code "494") (name "~{BAC_09}") (class "Default")
      (node (ref "B06") (pin "E2") (pinfunction "IN_E2") (pintype "input"))
      (node (ref "C03") (pin "J2") (pinfunction "O10_J2") (pintype "output"))
    )
    (net (code "495") (name "~{BAC_10}") (class "Default")
      (node (ref "A10") (pin "D2") (pinfunction "IN1_D2") (pintype "input"))
      (node (ref "B06") (pin "H2") (pinfunction "IN_H2") (pintype "input"))
      (node (ref "C03") (pin "L2") (pinfunction "O11_L2") (pintype "output"))
    )
    (net (code "496") (name "~{BAC_11}") (class "Default")
      (node (ref "B06") (pin "K2") (pinfunction "IN_K2") (pintype "input"))
      (node (ref "C03") (pin "N2") (pinfunction "O12_N2") (pintype "output"))
      (node (ref "C11") (pin "R2") (pinfunction "IN2_R2") (pintype "input"))
    )
    (net (code "497") (name "~{BLK_IN_SYNC}") (class "Default")
      (node (ref "A10") (pin "A1") (pinfunction "IN1_A1") (pintype "input"))
      (node (ref "C13") (pin "R1") (pinfunction "IN_R1") (pintype "input"))
      (node (ref "D10") (pin "J2") (pinfunction "OUT_J2") (pintype "output"))
    )
    (net (code "498") (name "~{BMB_00}") (class "Default")
      (node (ref "C02") (pin "B1") (pinfunction "O1_B1") (pintype "output"))
      (node (ref "C06") (pin "A1") (pinfunction "IN_A1") (pintype "input"))
    )
    (net (code "499") (name "~{BMB_01}") (class "Default")
      (node (ref "C02") (pin "E1") (pinfunction "O2_E1") (pintype "output"))
      (node (ref "C06") (pin "D1") (pinfunction "IN_D1") (pintype "input"))
    )
    (net (code "500") (name "~{BMB_02}") (class "Default")
      (node (ref "C02") (pin "H1") (pinfunction "O3_H1") (pintype "output"))
      (node (ref "C06") (pin "F1") (pinfunction "IN_F1") (pintype "input"))
    )
    (net (code "501") (name "~{BMB_03}") (class "Default")
      (node (ref "C02") (pin "K1") (pinfunction "O4_K1") (pintype "output"))
      (node (ref "C06") (pin "J1") (pinfunction "IN_J1") (pintype "input"))
    )
    (net (code "502") (name "~{BMB_04}") (class "Default")
      (node (ref "C02") (pin "M1") (pinfunction "O5_M1") (pintype "output"))
      (node (ref "C06") (pin "L1") (pinfunction "IN_L1") (pintype "input"))
    )
    (net (code "503") (name "~{BMB_05}") (class "Default")
      (node (ref "C02") (pin "P1") (pinfunction "O6_P1") (pintype "output"))
      (node (ref "C06") (pin "N1") (pinfunction "IN_N1") (pintype "input"))
    )
    (net (code "504") (name "~{BMB_06}") (class "Default")
      (node (ref "C02") (pin "S1") (pinfunction "O7_S1") (pintype "output"))
      (node (ref "C06") (pin "R1") (pinfunction "IN_R1") (pintype "input"))
    )
    (net (code "505") (name "~{BMB_07}") (class "Default")
      (node (ref "C02") (pin "U1") (pinfunction "O8_U1") (pintype "output"))
      (node (ref "C06") (pin "V1") (pinfunction "IN_V1") (pintype "input"))
    )
    (net (code "506") (name "~{BMB_08}") (class "Default")
      (node (ref "C02") (pin "F2") (pinfunction "O9_F2") (pintype "output"))
      (node (ref "C06") (pin "C1") (pinfunction "IN_C1") (pintype "input"))
    )
    (net (code "507") (name "~{BMB_09}") (class "Default")
      (node (ref "C02") (pin "J2") (pinfunction "O10_J2") (pintype "output"))
      (node (ref "C06") (pin "E2") (pinfunction "IN_E2") (pintype "input"))
    )
    (net (code "508") (name "~{BMB_10}") (class "Default")
      (node (ref "C02") (pin "L2") (pinfunction "O11_L2") (pintype "output"))
      (node (ref "C06") (pin "H2") (pinfunction "IN_H2") (pintype "input"))
    )
    (net (code "509") (name "~{BMB_11}") (class "Default")
      (node (ref "C02") (pin "N2") (pinfunction "O12_N2") (pintype "output"))
      (node (ref "C06") (pin "K2") (pinfunction "IN_K2") (pintype "input"))
    )
    (net (code "510") (name "~{BMR00}") (class "Default")
      (node (ref "A23") (pin "H1") (pinfunction "B_H1") (pintype "input"))
      (node (ref "B14") (pin "R2") (pinfunction "0_R2") (pintype "output"))
    )
    (net (code "511") (name "~{BMR01}") (class "Default")
      (node (ref "A23") (pin "A1") (pinfunction "A_A1") (pintype "input"))
      (node (ref "B14") (pin "E1") (pinfunction "1_E1") (pintype "output"))
    )
    (net (code "512") (name "~{C00}") (class "Default")
      (node (ref "A12") (pin "P2") (pinfunction "IN1_P2") (pintype "input"))
      (node (ref "B13") (pin "P1") (pinfunction "D_P1") (pintype "input"))
      (node (ref "B13") (pin "S2") (pinfunction "C_S2") (pintype "input"))
      (node (ref "B13") (pin "U1") (pinfunction "0_U1") (pintype "output"))
      (node (ref "B15") (pin "H1") (pinfunction "IN1_H1") (pintype "input"))
      (node (ref "C15") (pin "J2") (pinfunction "IN2_J2") (pintype "input"))
    )
    (net (code "513") (name "~{C01}") (class "Default")
      (node (ref "A12") (pin "R2") (pinfunction "IN2_R2") (pintype "input"))
      (node (ref "B10") (pin "P1") (pinfunction "IN3_P1") (pintype "input"))
      (node (ref "B13") (pin "M2") (pinfunction "D_M2") (pintype "input"))
      (node (ref "B13") (pin "R2") (pinfunction "0_R2") (pintype "output"))
      (node (ref "C12") (pin "F2") (pinfunction "IN3_F2") (pintype "input"))
      (node (ref "D10") (pin "D1") (pinfunction "IN4_D1") (pintype "input"))
    )
    (net (code "514") (name "~{CK00}") (class "Default")
      (node (ref "A18") (pin "N2") (pinfunction "N2_N2") (pintype "input"))
      (node (ref "B14") (pin "T2") (pinfunction "D_T2") (pintype "input"))
      (node (ref "B14") (pin "U1") (pinfunction "0_U1") (pintype "output"))
    )
    (net (code "515") (name "~{CK01}") (class "Default")
      (node (ref "B14") (pin "V1") (pinfunction "0_V1") (pintype "output"))
      (node (ref "C16") (pin "S2") (pinfunction "IN2_S2") (pintype "input"))
      (node (ref "C16") (pin "T2") (pinfunction "IN3_T2") (pintype "input"))
      (node (ref "C16") (pin "U2") (pinfunction "IN4_U2") (pintype "input"))
    )
    (net (code "516") (name "~{CLR_DF}") (class "Default")
      (node (ref "A11") (pin "U1") (pinfunction "OUT_U1") (pintype "output"))
      (node (ref "D11") (pin "N2") (pinfunction "S_N2") (pintype "input"))
    )
    (net (code "517") (name "~{CLR_DTF}") (class "Default")
      (node (ref "C13") (pin "U1") (pinfunction "OUT_U1") (pintype "output"))
      (node (ref "D11") (pin "U2") (pinfunction "S_U2") (pintype "input"))
    )
    (net (code "518") (name "~{CSTA}") (class "Default")
      (node (ref "A10") (pin "L2") (pinfunction "IN1_L2") (pintype "input"))
      (node (ref "C04") (pin "D1") (pinfunction "D1_D1") (pintype "output"))
    )
    (net (code "519") (name "~{DATA}") (class "Default")
      (node (ref "B12") (pin "N1") (pinfunction "IN2_N1") (pintype "input"))
      (node (ref "C11") (pin "L2") (pinfunction "IN1_L2") (pintype "input"))
      (node (ref "C13") (pin "H1") (pinfunction "OUT_H1") (pintype "output"))
      (node (ref "C16") (pin "D2") (pinfunction "IN1_D2") (pintype "input"))
    )
    (net (code "520") (name "~{DB_00}") (class "Default")
      (node (ref "A06") (pin "B1") (pinfunction "P$2_B1") (pintype "bidirectional"))
      (node (ref "B02") (pin "D1") (pinfunction "D_D1") (pintype "open_collector"))
      (node (ref "D06") (pin "B1") (pinfunction "P$2_B1") (pintype "bidirectional"))
    )
    (net (code "521") (name "~{DB_01}") (class "Default")
      (node (ref "A06") (pin "D1") (pinfunction "P$2_D1") (pintype "bidirectional"))
      (node (ref "B02") (pin "E1") (pinfunction "E_E1") (pintype "open_collector"))
      (node (ref "D06") (pin "D1") (pinfunction "P$2_D1") (pintype "bidirectional"))
    )
    (net (code "522") (name "~{DB_02}") (class "Default")
      (node (ref "A06") (pin "E1") (pinfunction "P$2_E1") (pintype "bidirectional"))
      (node (ref "B02") (pin "K1") (pinfunction "D_K1") (pintype "open_collector"))
      (node (ref "D06") (pin "E1") (pinfunction "P$2_E1") (pintype "bidirectional"))
    )
    (net (code "523") (name "~{DB_03}") (class "Default")
      (node (ref "A06") (pin "H1") (pinfunction "P$2_H1") (pintype "bidirectional"))
      (node (ref "B02") (pin "L1") (pinfunction "E_L1") (pintype "open_collector"))
      (node (ref "D06") (pin "H1") (pinfunction "P$2_H1") (pintype "bidirectional"))
    )
    (net (code "524") (name "~{DB_04}") (class "Default")
      (node (ref "A06") (pin "J1") (pinfunction "P$2_J1") (pintype "bidirectional"))
      (node (ref "B02") (pin "R1") (pinfunction "D_R1") (pintype "open_collector"))
      (node (ref "D06") (pin "J1") (pinfunction "P$2_J1") (pintype "bidirectional"))
    )
    (net (code "525") (name "~{DB_05}") (class "Default")
      (node (ref "A06") (pin "L1") (pinfunction "P$2_L1") (pintype "bidirectional"))
      (node (ref "B02") (pin "S1") (pinfunction "E_S1") (pintype "open_collector"))
      (node (ref "D06") (pin "L1") (pinfunction "P$2_L1") (pintype "bidirectional"))
    )
    (net (code "526") (name "~{DB_06}") (class "Default")
      (node (ref "A06") (pin "M1") (pinfunction "P$2_M1") (pintype "bidirectional"))
      (node (ref "B02") (pin "H2") (pinfunction "D_H2") (pintype "open_collector"))
      (node (ref "D06") (pin "M1") (pinfunction "P$2_M1") (pintype "bidirectional"))
    )
    (net (code "527") (name "~{DB_07}") (class "Default")
      (node (ref "A06") (pin "P1") (pinfunction "P$2_P1") (pintype "bidirectional"))
      (node (ref "B02") (pin "J2") (pinfunction "E_J2") (pintype "open_collector"))
      (node (ref "D06") (pin "P1") (pinfunction "P$2_P1") (pintype "bidirectional"))
    )
    (net (code "528") (name "~{DB_08}") (class "Default")
      (node (ref "A06") (pin "S1") (pinfunction "P$2_S1") (pintype "bidirectional"))
      (node (ref "B02") (pin "N2") (pinfunction "D_N2") (pintype "open_collector"))
      (node (ref "D06") (pin "S1") (pinfunction "P$2_S1") (pintype "bidirectional"))
    )
    (net (code "529") (name "~{DB_09}") (class "Default")
      (node (ref "A06") (pin "D2") (pinfunction "P$2_D2") (pintype "bidirectional"))
      (node (ref "B02") (pin "P2") (pinfunction "E_P2") (pintype "open_collector"))
      (node (ref "D06") (pin "D2") (pinfunction "P$2_D2") (pintype "bidirectional"))
    )
    (net (code "530") (name "~{DB_10}") (class "Default")
      (node (ref "A06") (pin "E2") (pinfunction "P$2_E2") (pintype "bidirectional"))
      (node (ref "B02") (pin "U2") (pinfunction "D_U2") (pintype "open_collector"))
      (node (ref "D06") (pin "E2") (pinfunction "P$2_E2") (pintype "bidirectional"))
    )
    (net (code "531") (name "~{DB_11}") (class "Default")
      (node (ref "A06") (pin "H2") (pinfunction "P$2_H2") (pintype "bidirectional"))
      (node (ref "B02") (pin "V2") (pinfunction "E_V2") (pintype "open_collector"))
      (node (ref "D06") (pin "H2") (pinfunction "P$2_H2") (pintype "bidirectional"))
    )
    (net (code "532") (name "~{DF}") (class "Default")
      (node (ref "B05") (pin "A1") (pinfunction "A_A1") (pintype "input"))
      (node (ref "B12") (pin "J1") (pinfunction "IN3_J1") (pintype "input"))
      (node (ref "D11") (pin "P2") (pinfunction "1_P2") (pintype "output"))
    )
    (net (code "533") (name "~{DTB_00}") (class "Default")
      (node (ref "B02") (pin "A1") (pinfunction "A_A1") (pintype "input"))
      (node (ref "C09") (pin "F1") (pinfunction "0_F1") (pintype "output"))
    )
    (net (code "534") (name "~{DTB_01}") (class "Default")
      (node (ref "B02") (pin "B1") (pinfunction "B_B1") (pintype "input"))
      (node (ref "C09") (pin "J2") (pinfunction "0_J2") (pintype "output"))
    )
    (net (code "535") (name "~{DTB_02}") (class "Default")
      (node (ref "B02") (pin "F1") (pinfunction "A_F1") (pintype "input"))
      (node (ref "C09") (pin "M1") (pinfunction "0_M1") (pintype "output"))
    )
    (net (code "536") (name "~{DTB_03}") (class "Default")
      (node (ref "B02") (pin "H1") (pinfunction "B_H1") (pintype "input"))
      (node (ref "C09") (pin "R2") (pinfunction "0_R2") (pintype "output"))
    )
    (net (code "537") (name "~{DTB_04}") (class "Default")
      (node (ref "B02") (pin "M1") (pinfunction "A_M1") (pintype "input"))
      (node (ref "C09") (pin "U1") (pinfunction "0_U1") (pintype "output"))
    )
    (net (code "538") (name "~{DTB_05}") (class "Default")
      (node (ref "B02") (pin "N1") (pinfunction "B_N1") (pintype "input"))
      (node (ref "C09") (pin "V1") (pinfunction "0_V1") (pintype "output"))
    )
    (net (code "539") (name "~{DTB_06}") (class "Default")
      (node (ref "B02") (pin "D2") (pinfunction "A_D2") (pintype "input"))
      (node (ref "B09") (pin "F1") (pinfunction "0_F1") (pintype "output"))
    )
    (net (code "540") (name "~{DTB_07}") (class "Default")
      (node (ref "B02") (pin "E2") (pinfunction "B_E2") (pintype "input"))
      (node (ref "B09") (pin "V1") (pinfunction "0_V1") (pintype "output"))
    )
    (net (code "541") (name "~{DTB_08}") (class "Default")
      (node (ref "B02") (pin "K2") (pinfunction "A_K2") (pintype "input"))
      (node (ref "B09") (pin "M1") (pinfunction "0_M1") (pintype "output"))
    )
    (net (code "542") (name "~{DTB_09}") (class "Default")
      (node (ref "B02") (pin "L2") (pinfunction "B_L2") (pintype "input"))
      (node (ref "B09") (pin "R2") (pinfunction "0_R2") (pintype "output"))
    )
    (net (code "543") (name "~{DTB_10}") (class "Default")
      (node (ref "B02") (pin "R2") (pinfunction "A_R2") (pintype "input"))
      (node (ref "B09") (pin "U1") (pinfunction "0_U1") (pintype "output"))
    )
    (net (code "544") (name "~{DTB_11}") (class "Default")
      (node (ref "B02") (pin "S2") (pinfunction "B_S2") (pintype "input"))
      (node (ref "B09") (pin "J2") (pinfunction "0_J2") (pintype "output"))
    )
    (net (code "545") (name "~{DTF}") (class "Default")
      (node (ref "A12") (pin "M1") (pinfunction "IN2_M1") (pintype "input"))
      (node (ref "B04") (pin "L2") (pinfunction "B_L2") (pintype "input"))
      (node (ref "B12") (pin "C1") (pinfunction "IN3_C1") (pintype "input"))
      (node (ref "D11") (pin "V2") (pinfunction "1_V2") (pintype "output"))
    )
    (net (code "546") (name "~{DTSF}") (class "Default")
      (node (ref "C05") (pin "B1") (pinfunction "B1_B1") (pintype "output"))
    )
    (net (code "547") (name "~{EA_00}") (class "Default")
      (node (ref "A06") (pin "V2") (pinfunction "P$2_V2") (pintype "bidirectional"))
      (node (ref "B05") (pin "R1") (pinfunction "D_R1") (pintype "open_collector"))
      (node (ref "D06") (pin "V2") (pinfunction "P$2_V2") (pintype "bidirectional"))
    )
    (net (code "548") (name "~{EA_01}") (class "Default")
      (node (ref "A06") (pin "T2") (pinfunction "P$2_T2") (pintype "bidirectional"))
      (node (ref "B05") (pin "S1") (pinfunction "E_S1") (pintype "open_collector"))
      (node (ref "D06") (pin "T2") (pinfunction "P$2_T2") (pintype "bidirectional"))
    )
    (net (code "549") (name "~{EA_02}") (class "Default")
      (node (ref "A06") (pin "S2") (pinfunction "P$2_S2") (pintype "bidirectional"))
      (node (ref "B05") (pin "H2") (pinfunction "D_H2") (pintype "open_collector"))
      (node (ref "D06") (pin "S2") (pinfunction "P$2_S2") (pintype "bidirectional"))
    )
    (net (code "550") (name "~{EF}") (class "Default")
      (node (ref "A11") (pin "K1") (pinfunction "OUT_K1") (pintype "output"))
      (node (ref "A12") (pin "L1") (pinfunction "IN1_L1") (pintype "input"))
      (node (ref "B04") (pin "A1") (pinfunction "A_A1") (pintype "input"))
    )
    (net (code "551") (name "~{END}") (class "Default")
      (node (ref "A08") (pin "F1") (pinfunction "0_F1") (pintype "output"))
      (node (ref "A09") (pin "M2") (pinfunction "IN3_M2") (pintype "input"))
      (node (ref "B04") (pin "F1") (pinfunction "A_F1") (pintype "input"))
    )
    (net (code "552") (name "~{ENI}") (class "Default")
      (node (ref "B03") (pin "L2") (pinfunction "B_L2") (pintype "input"))
      (node (ref "C07") (pin "M1") (pinfunction "M1_M1") (pintype "output"))
    )
    (net (code "553") (name "~{FR_00}") (class "Default")
      (node (ref "B03") (pin "N1") (pinfunction "B_N1") (pintype "input"))
      (node (ref "B07") (pin "U1") (pinfunction "U1_U1") (pintype "output"))
      (node (ref "C12") (pin "K1") (pinfunction "IN1_K1") (pintype "input"))
      (node (ref "C12") (pin "P1") (pinfunction "IN1_P1") (pintype "input"))
    )
    (net (code "554") (name "~{FR_01}") (class "Default")
      (node (ref "A12") (pin "H2") (pinfunction "IN1_H2") (pintype "input"))
      (node (ref "B03") (pin "D2") (pinfunction "A_D2") (pintype "input"))
      (node (ref "B05") (pin "E2") (pinfunction "B_E2") (pintype "input"))
      (node (ref "B07") (pin "V1") (pinfunction "V1_V1") (pintype "output"))
    )
    (net (code "555") (name "~{FR_02}") (class "Default")
      (node (ref "B03") (pin "E2") (pinfunction "B_E2") (pintype "input"))
      (node (ref "C07") (pin "F1") (pinfunction "F1_F1") (pintype "output"))
    )
    (net (code "556") (name "~{FR_03}") (class "Default")
      (node (ref "B03") (pin "K2") (pinfunction "A_K2") (pintype "input"))
      (node (ref "B08") (pin "J2") (pinfunction "IN2_J2") (pintype "input"))
      (node (ref "C07") (pin "J2") (pinfunction "J2_J2") (pintype "output"))
    )
    (net (code "557") (name "~{IM_00}") (class "Default")
      (node (ref "A04") (pin "B1") (pinfunction "P$2_B1") (pintype "bidirectional"))
      (node (ref "B03") (pin "D1") (pinfunction "D_D1") (pintype "open_collector"))
      (node (ref "B04") (pin "D1") (pinfunction "D_D1") (pintype "open_collector"))
      (node (ref "D04") (pin "B1") (pinfunction "P$2_B1") (pintype "bidirectional"))
    )
    (net (code "558") (name "~{IM_01}") (class "Default")
      (node (ref "A04") (pin "D1") (pinfunction "P$2_D1") (pintype "bidirectional"))
      (node (ref "B03") (pin "E1") (pinfunction "E_E1") (pintype "open_collector"))
      (node (ref "B04") (pin "E1") (pinfunction "E_E1") (pintype "open_collector"))
      (node (ref "D04") (pin "D1") (pinfunction "P$2_D1") (pintype "bidirectional"))
    )
    (net (code "559") (name "~{IM_02}") (class "Default")
      (node (ref "A04") (pin "E1") (pinfunction "P$2_E1") (pintype "bidirectional"))
      (node (ref "B03") (pin "K1") (pinfunction "D_K1") (pintype "open_collector"))
      (node (ref "B04") (pin "K1") (pinfunction "D_K1") (pintype "open_collector"))
      (node (ref "D04") (pin "E1") (pinfunction "P$2_E1") (pintype "bidirectional"))
    )
    (net (code "560") (name "~{IM_03}") (class "Default")
      (node (ref "A04") (pin "H1") (pinfunction "P$2_H1") (pintype "bidirectional"))
      (node (ref "B03") (pin "L1") (pinfunction "E_L1") (pintype "open_collector"))
      (node (ref "B04") (pin "L1") (pinfunction "E_L1") (pintype "open_collector"))
      (node (ref "D04") (pin "H1") (pinfunction "P$2_H1") (pintype "bidirectional"))
    )
    (net (code "561") (name "~{IM_04}") (class "Default")
      (node (ref "A04") (pin "J1") (pinfunction "P$2_J1") (pintype "bidirectional"))
      (node (ref "B03") (pin "R1") (pinfunction "D_R1") (pintype "open_collector"))
      (node (ref "B04") (pin "R1") (pinfunction "D_R1") (pintype "open_collector"))
      (node (ref "D04") (pin "J1") (pinfunction "P$2_J1") (pintype "bidirectional"))
    )
    (net (code "562") (name "~{IM_05}") (class "Default")
      (node (ref "A04") (pin "L1") (pinfunction "P$2_L1") (pintype "bidirectional"))
      (node (ref "B03") (pin "S1") (pinfunction "E_S1") (pintype "open_collector"))
      (node (ref "B04") (pin "S1") (pinfunction "E_S1") (pintype "open_collector"))
      (node (ref "D04") (pin "L1") (pinfunction "P$2_L1") (pintype "bidirectional"))
    )
    (net (code "563") (name "~{IM_06}") (class "Default")
      (node (ref "A04") (pin "M1") (pinfunction "P$2_M1") (pintype "bidirectional"))
      (node (ref "B03") (pin "H2") (pinfunction "D_H2") (pintype "open_collector"))
      (node (ref "B04") (pin "H2") (pinfunction "D_H2") (pintype "open_collector"))
      (node (ref "D04") (pin "M1") (pinfunction "P$2_M1") (pintype "bidirectional"))
    )
    (net (code "564") (name "~{IM_07}") (class "Default")
      (node (ref "A04") (pin "P1") (pinfunction "P$2_P1") (pintype "bidirectional"))
      (node (ref "B03") (pin "J2") (pinfunction "E_J2") (pintype "open_collector"))
      (node (ref "B04") (pin "J2") (pinfunction "E_J2") (pintype "open_collector"))
      (node (ref "D04") (pin "P1") (pinfunction "P$2_P1") (pintype "bidirectional"))
    )
    (net (code "565") (name "~{IM_08}") (class "Default")
      (node (ref "A04") (pin "S1") (pinfunction "P$2_S1") (pintype "bidirectional"))
      (node (ref "B03") (pin "N2") (pinfunction "D_N2") (pintype "open_collector"))
      (node (ref "B04") (pin "N2") (pinfunction "D_N2") (pintype "open_collector"))
      (node (ref "D04") (pin "S1") (pinfunction "P$2_S1") (pintype "bidirectional"))
    )
    (net (code "566") (name "~{IM_09}") (class "Default")
      (node (ref "A04") (pin "D2") (pinfunction "P$2_D2") (pintype "bidirectional"))
      (node (ref "B03") (pin "P2") (pinfunction "E_P2") (pintype "open_collector"))
      (node (ref "D04") (pin "D2") (pinfunction "P$2_D2") (pintype "bidirectional"))
    )
    (net (code "567") (name "~{IM_10}") (class "Default")
      (node (ref "A04") (pin "E2") (pinfunction "P$2_E2") (pintype "bidirectional"))
      (node (ref "D04") (pin "E2") (pinfunction "P$2_E2") (pintype "bidirectional"))
    )
    (net (code "568") (name "~{IM_11}") (class "Default")
      (node (ref "A04") (pin "H2") (pinfunction "P$2_H2") (pintype "bidirectional"))
      (node (ref "B04") (pin "P2") (pinfunction "E_P2") (pintype "open_collector"))
      (node (ref "D04") (pin "H2") (pinfunction "P$2_H2") (pintype "bidirectional"))
    )
    (net (code "569") (name "~{INT_RQ}") (class "Default")
      (node (ref "A12") (pin "K1") (pinfunction "OUT_K1") (pintype "output"))
      (node (ref "B05") (pin "B1") (pinfunction "B_B1") (pintype "input"))
    )
    (net (code "570") (name "~{LDMF}") (class "Default")
      (node (ref "B08") (pin "P2") (pinfunction "IN1_P2") (pintype "input"))
      (node (ref "C05") (pin "F1") (pinfunction "F1_F1") (pintype "output"))
    )
    (net (code "571") (name "~{LPB_00}") (class "Default")
      (node (ref "D08") (pin "F1") (pinfunction "F1_F1") (pintype "output"))
    )
    (net (code "572") (name "~{LPB_01}") (class "Default")
      (node (ref "D08") (pin "M1") (pinfunction "M1_M1") (pintype "output"))
    )
    (net (code "573") (name "~{LPB_02}") (class "Default")
      (node (ref "D08") (pin "U1") (pinfunction "U1_U1") (pintype "output"))
    )
    (net (code "574") (name "~{LPB_03}") (class "Default")
      (node (ref "D08") (pin "J2") (pinfunction "J2_J2") (pintype "output"))
    )
    (net (code "575") (name "~{LPB_04}") (class "Default")
      (node (ref "D08") (pin "R2") (pinfunction "R2_R2") (pintype "output"))
    )
    (net (code "576") (name "~{LPB_05}") (class "Default")
      (node (ref "D08") (pin "V1") (pinfunction "V1_V1") (pintype "output"))
    )
    (net (code "577") (name "~{M-STOP}") (class "Default")
      (node (ref "A11") (pin "S1") (pinfunction "OUT_S1") (pintype "output"))
      (node (ref "B14") (pin "D1") (pinfunction "S_D1") (pintype "input"))
      (node (ref "C07") (pin "K2") (pinfunction "K2_K2") (pintype "input"))
      (node (ref "D14") (pin "L1") (pinfunction "M1_L1") (pintype "input"))
    )
    (net (code "578") (name "~{MB_TO_DTB}") (class "Default")
      (node (ref "D12") (pin "F1") (pinfunction "IN1_F1") (pintype "input"))
      (node (ref "D12") (pin "H1") (pinfunction "IN2_H1") (pintype "input"))
      (node (ref "D12") (pin "J1") (pinfunction "IN3_J1") (pintype "input"))
      (node (ref "D12") (pin "K1") (pinfunction "IN4_K1") (pintype "input"))
      (node (ref "D12") (pin "S1") (pinfunction "OUT_S1") (pintype "output"))
    )
    (net (code "579") (name "~{MC00}") (class "Default")
      (node (ref "A10") (pin "R1") (pinfunction "IN2_R1") (pintype "input"))
      (node (ref "B11") (pin "T2") (pinfunction "IN1_T2") (pintype "input"))
      (node (ref "B13") (pin "F1") (pinfunction "0_F1") (pintype "output"))
    )
    (net (code "580") (name "~{MC01}") (class "Default")
      (node (ref "B11") (pin "P1") (pinfunction "IN1_P1") (pintype "input"))
      (node (ref "B13") (pin "J2") (pinfunction "0_J2") (pintype "output"))
      (node (ref "C11") (pin "B1") (pinfunction "IN2_B1") (pintype "input"))
      (node (ref "D10") (pin "E2") (pinfunction "IN6_E2") (pintype "input"))
    )
    (net (code "581") (name "~{MC02}") (class "Default")
      (node (ref "B13") (pin "C1") (pinfunction "D_C1") (pintype "input"))
      (node (ref "B13") (pin "M1") (pinfunction "0_M1") (pintype "output"))
      (node (ref "D10") (pin "F2") (pinfunction "IN7_F2") (pintype "input"))
    )
    (net (code "582") (name "~{MF00}") (class "Default")
      (node (ref "B04") (pin "D2") (pinfunction "A_D2") (pintype "input"))
      (node (ref "B05") (pin "M1") (pinfunction "A_M1") (pintype "input"))
      (node (ref "D11") (pin "F1") (pinfunction "0_F1") (pintype "output"))
    )
    (net (code "583") (name "~{MF01}") (class "Default")
      (node (ref "B04") (pin "E2") (pinfunction "B_E2") (pintype "input"))
      (node (ref "B05") (pin "N1") (pinfunction "B_N1") (pintype "input"))
      (node (ref "D11") (pin "J2") (pinfunction "0_J2") (pintype "output"))
    )
    (net (code "584") (name "~{MF02}") (class "Default")
      (node (ref "B04") (pin "K2") (pinfunction "A_K2") (pintype "input"))
      (node (ref "B05") (pin "D2") (pinfunction "A_D2") (pintype "input"))
      (node (ref "D11") (pin "M1") (pinfunction "0_M1") (pintype "output"))
    )
    (net (code "585") (name "~{MKTK}") (class "Default")
      (node (ref "A08") (pin "P2") (pinfunction "1_P2") (pintype "output"))
      (node (ref "A09") (pin "K2") (pinfunction "IN1_K2") (pintype "input"))
      (node (ref "B04") (pin "B1") (pinfunction "B_B1") (pintype "input"))
    )
    (net (code "586") (name "~{MKT}") (class "Default")
      (node (ref "B10") (pin "R1") (pinfunction "IN4_R1") (pintype "input"))
      (node (ref "B13") (pin "T2") (pinfunction "D_T2") (pintype "input"))
      (node (ref "B13") (pin "V1") (pinfunction "0_V1") (pintype "output"))
      (node (ref "C14") (pin "N1") (pinfunction "C_N1") (pintype "input"))
      (node (ref "D10") (pin "H2") (pinfunction "IN8_H2") (pintype "input"))
    )
    (net (code "587") (name "~{MK_BLK_END}") (class "Default")
      (node (ref "A09") (pin "C1") (pinfunction "IN3_C1") (pintype "input"))
      (node (ref "CD18") (pin "BV1") (pinfunction "BV1_BV1") (pintype "output"))
    )
    (net (code "588") (name "~{MK_BLK_MK}") (class "Default")
      (node (ref "CD18") (pin "AD2") (pinfunction "AD2_AD2") (pintype "output"))
    )
    (net (code "589") (name "~{MK_BLK_START}") (class "Default")
      (node (ref "A09") (pin "A1") (pinfunction "IN1_A1") (pintype "input"))
      (node (ref "CD18") (pin "AF1") (pinfunction "AF1_AF1") (pintype "output"))
    )
    (net (code "590") (name "~{MK_BLK_SYNC}") (class "Default")
      (node (ref "CD18") (pin "BT2") (pinfunction "BT2_BT2") (pintype "output"))
    )
    (net (code "591") (name "~{MK_DATA_SYNC}") (class "Default")
      (node (ref "CD18") (pin "AJ1") (pinfunction "AJ1_AJ1") (pintype "output"))
    )
    (net (code "592") (name "~{MK_DATA}") (class "Default")
      (node (ref "A09") (pin "B1") (pinfunction "IN2_B1") (pintype "input"))
      (node (ref "CD18") (pin "AU2") (pinfunction "AU2_AU2") (pintype "output"))
    )
    (net (code "593") (name "~{MK_END}") (class "Default")
      (node (ref "A09") (pin "D1") (pinfunction "IN4_D1") (pintype "input"))
      (node (ref "CD18") (pin "AH2") (pinfunction "AH2_AH2") (pintype "output"))
    )
    (net (code "594") (name "~{MOVE}") (class "Default")
      (node (ref "A09") (pin "F2") (pinfunction "IN3_F2") (pintype "input"))
      (node (ref "D07") (pin "D1") (pinfunction "~{O0}_D1") (pintype "output"))
    )
    (net (code "595") (name "~{MR00}") (class "Default")
      (node (ref "B03") (pin "H1") (pinfunction "B_H1") (pintype "input"))
      (node (ref "B07") (pin "R2") (pinfunction "R2_R2") (pintype "output"))
    )
    (net (code "596") (name "~{MR01}") (class "Default")
      (node (ref "B03") (pin "M1") (pinfunction "A_M1") (pintype "input"))
      (node (ref "B14") (pin "C1") (pinfunction "D_C1") (pintype "input"))
      (node (ref "C07") (pin "R2") (pinfunction "R2_R2") (pintype "output"))
    )
    (net (code "597") (name "~{PAR}") (class "Default")
      (node (ref "A08") (pin "S1") (pinfunction "1_S1") (pintype "output"))
      (node (ref "A12") (pin "E1") (pinfunction "IN2_E1") (pintype "input"))
      (node (ref "B04") (pin "M1") (pinfunction "A_M1") (pintype "input"))
    )
    (net (code "598") (name "~{PC+ES}") (class "Default")
      (node (ref "A11") (pin "J2") (pinfunction "OUT_J2") (pintype "output"))
      (node (ref "B11") (pin "R2") (pinfunction "IN3_R2") (pintype "input"))
    )
    (net (code "599") (name "~{PWR_CLR}") (class "Default")
      (node (ref "A10") (pin "H2") (pinfunction "IN1_H2") (pintype "input"))
      (node (ref "A10") (pin "M2") (pinfunction "IN2_M2") (pintype "input"))
      (node (ref "A12") (pin "A1") (pinfunction "IN1_A1") (pintype "input"))
      (node (ref "A23") (pin "M1") (pinfunction "A_M1") (pintype "input"))
      (node (ref "B08") (pin "U2") (pinfunction "IN2_U2") (pintype "input"))
      (node (ref "C05") (pin "K1") (pinfunction "OUT_K1") (pintype "output"))
      (node (ref "C06") (pin "P2") (pinfunction "IN_P2") (pintype "input"))
      (node (ref "C11") (pin "U2") (pinfunction "IN2_U2") (pintype "input"))
      (node (ref "C14") (pin "R1") (pinfunction "S_R1") (pintype "input"))
      (node (ref "D11") (pin "A1") (pinfunction "R_A1") (pintype "input"))
    )
    (net (code "600") (name "~{RDD_00}") (class "Default")
      (node (ref "A21") (pin "V2") (pinfunction "V2_V2") (pintype "output"))
    )
    (net (code "601") (name "~{RDD_01}") (class "Default")
      (node (ref "B20") (pin "V2") (pinfunction "V2_V2") (pintype "output"))
    )
    (net (code "602") (name "~{RDD_02}") (class "Default")
      (node (ref "A20") (pin "V2") (pinfunction "V2_V2") (pintype "output"))
    )
    (net (code "603") (name "~{RDMK}") (class "Default")
      (node (ref "B18") (pin "V2") (pinfunction "V2_V2") (pintype "output"))
    )
    (net (code "604") (name "~{READ_ALL}") (class "Default")
      (node (ref "C11") (pin "M1") (pinfunction "IN2_M1") (pintype "input"))
      (node (ref "D07") (pin "N1") (pinfunction "~{O3}_N1") (pintype "output"))
    )
    (net (code "605") (name "~{READ_DATA}") (class "Default")
      (node (ref "B08") (pin "L2") (pinfunction "IN1_L2") (pintype "input"))
      (node (ref "B11") (pin "J2") (pinfunction "IN1_J2") (pintype "input"))
      (node (ref "D07") (pin "J1") (pinfunction "~{O2}_J1") (pintype "output"))
    )
    (net (code "606") (name "~{RSTA}") (class "Default")
      (node (ref "B03") (pin "C1") (pinfunction "C_C1") (pintype "input"))
      (node (ref "B03") (pin "F2") (pinfunction "C_F2") (pintype "input"))
      (node (ref "B03") (pin "J1") (pinfunction "C_J1") (pintype "input"))
      (node (ref "B03") (pin "M2") (pinfunction "C_M2") (pintype "input"))
      (node (ref "B03") (pin "P1") (pinfunction "C_P1") (pintype "input"))
      (node (ref "C04") (pin "B1") (pinfunction "B1_B1") (pintype "output"))
    )
    (net (code "607") (name "~{RSTB}") (class "Default")
      (node (ref "B04") (pin "C1") (pinfunction "C_C1") (pintype "input"))
      (node (ref "B04") (pin "F2") (pinfunction "C_F2") (pintype "input"))
      (node (ref "B04") (pin "J1") (pinfunction "C_J1") (pintype "input"))
      (node (ref "B04") (pin "M2") (pinfunction "C_M2") (pintype "input"))
      (node (ref "B04") (pin "P1") (pinfunction "C_P1") (pintype "input"))
      (node (ref "C05") (pin "D1") (pinfunction "D1_D1") (pintype "output"))
    )
    (net (code "608") (name "~{SEARCH}") (class "Default")
      (node (ref "B05") (pin "K2") (pinfunction "A_K2") (pintype "input"))
      (node (ref "B11") (pin "K2") (pinfunction "IN2_K2") (pintype "input"))
      (node (ref "D07") (pin "E1") (pinfunction "~{O1}_E1") (pintype "output"))
    )
    (net (code "609") (name "~{SEL}") (class "Default")
      (node (ref "A08") (pin "J2") (pinfunction "0_J2") (pintype "output"))
      (node (ref "A09") (pin "N2") (pinfunction "IN4_N2") (pintype "input"))
      (node (ref "B04") (pin "H1") (pinfunction "B_H1") (pintype "input"))
    )
    (net (code "610") (name "~{SE}") (class "Default")
      (node (ref "A09") (pin "H1") (pinfunction "IN2_H1") (pintype "input"))
      (node (ref "D07") (pin "L1") (pinfunction "~{O7}_L1") (pintype "output"))
    )
    (net (code "611") (name "~{SH_EN}") (class "Default")
      (node (ref "A11") (pin "M2") (pinfunction "IN_M2") (pintype "input"))
      (node (ref "A12") (pin "V2") (pinfunction "OUT_V2") (pintype "output"))
      (node (ref "C10") (pin "C1") (pinfunction "IN2A_C1") (pintype "input"))
      (node (ref "C10") (pin "J1") (pinfunction "IN2A_J1") (pintype "input"))
      (node (ref "C10") (pin "P1") (pinfunction "IN2A_P1") (pintype "input"))
    )
    (net (code "612") (name "~{SKP_RQ}") (class "Default")
      (node (ref "A12") (pin "S1") (pinfunction "OUT_S1") (pintype "output"))
      (node (ref "B05") (pin "F1") (pinfunction "A_F1") (pintype "input"))
    )
    (net (code "613") (name "~{SP_DY}") (class "Default")
      (node (ref "C14") (pin "M2") (pinfunction "D_M2") (pintype "input"))
      (node (ref "D14") (pin "F2") (pinfunction "F2_F2") (pintype "output"))
    )
    (net (code "614") (name "~{ST_BLK_MK}") (class "Default")
      (node (ref "A09") (pin "D2") (pinfunction "IN1_D2") (pintype "input"))
      (node (ref "A09") (pin "M1") (pinfunction "IN1_M1") (pintype "input"))
      (node (ref "C13") (pin "F2") (pinfunction "OUT_F2") (pintype "output"))
    )
    (net (code "615") (name "~{ST_CK_0P}") (class "Default")
      (node (ref "C13") (pin "A1") (pinfunction "IN_A1") (pintype "input"))
      (node (ref "D17") (pin "L2") (pinfunction "F2_L2") (pintype "output"))
    )
    (net (code "616") (name "~{ST_CK}") (class "Default")
      (node (ref "C13") (pin "K1") (pinfunction "OUT_K1") (pintype "output"))
      (node (ref "C16") (pin "E2") (pinfunction "IN2_E2") (pintype "input"))
    )
    (net (code "617") (name "~{ST_DATA}") (class "Default")
      (node (ref "C13") (pin "J2") (pinfunction "OUT_J2") (pintype "output"))
    )
    (net (code "618") (name "~{ST_FINAL}") (class "Default")
      (node (ref "C11") (pin "M2") (pinfunction "IN2_M2") (pintype "input"))
      (node (ref "C13") (pin "M1") (pinfunction "OUT_M1") (pintype "output"))
      (node (ref "C16") (pin "F2") (pinfunction "IN3_F2") (pintype "input"))
    )
    (net (code "619") (name "~{ST_IDLE}") (class "Default")
      (node (ref "A09") (pin "E2") (pinfunction "IN2_E2") (pintype "input"))
      (node (ref "A09") (pin "N1") (pinfunction "IN2_N1") (pintype "input"))
      (node (ref "C13") (pin "L2") (pinfunction "OUT_L2") (pintype "output"))
    )
    (net (code "620") (name "~{ST_REV_CK}") (class "Default")
      (node (ref "C13") (pin "E1") (pinfunction "OUT_E1") (pintype "output"))
    )
    (net (code "621") (name "~{SWTM}") (class "Default")
      (node (ref "B06") (pin "R2") (pinfunction "OUT_R2") (pintype "output"))
      (node (ref "C10") (pin "L2") (pinfunction "IN1B_L2") (pintype "input"))
    )
    (net (code "622") (name "~{SYNC-P}") (class "Default")
      (node (ref "B13") (pin "A1") (pinfunction "R_A1") (pintype "input"))
      (node (ref "B13") (pin "K2") (pinfunction "R_K2") (pintype "input"))
      (node (ref "C17") (pin "V2") (pinfunction "OUT_V2") (pintype "output"))
    )
    (net (code "623") (name "~{SYNC}") (class "Default")
      (node (ref "CD18") (pin "BM2") (pinfunction "BM2_BM2") (pintype "output"))
    )
    (net (code "624") (name "~{TIM}") (class "Default")
      (node (ref "A08") (pin "M1") (pinfunction "0_M1") (pintype "output"))
      (node (ref "A09") (pin "L2") (pinfunction "IN2_L2") (pintype "input"))
      (node (ref "B04") (pin "N1") (pinfunction "B_N1") (pintype "input"))
    )
    (net (code "625") (name "~{TM_EN}") (class "Default")
      (node (ref "B15") (pin "D1") (pinfunction "IN1_D1") (pintype "input"))
      (node (ref "B15") (pin "D2") (pinfunction "IN1_D2") (pintype "input"))
      (node (ref "C12") (pin "C1") (pinfunction "IN3_C1") (pintype "input"))
      (node (ref "C12") (pin "K2") (pinfunction "IN2_K2") (pintype "input"))
      (node (ref "C13") (pin "P1") (pinfunction "OUT_P1") (pintype "output"))
      (node (ref "D15") (pin "J2") (pinfunction "J2_J2") (pintype "input"))
      (node (ref "D15") (pin "K2") (pinfunction "K2_K2") (pintype "input"))
    )
    (net (code "626") (name "~{TP00_A}") (class "Default")
      (node (ref "A15") (pin "M1") (pinfunction "IN1_M1") (pintype "input"))
      (node (ref "A15") (pin "N1") (pinfunction "IN2_N1") (pintype "input"))
      (node (ref "A15") (pin "P1") (pinfunction "IN3_P1") (pintype "input"))
      (node (ref "A15") (pin "R1") (pinfunction "IN4_R1") (pintype "input"))
      (node (ref "A16") (pin "L2") (pinfunction "F2_L2") (pintype "output"))
    )
    (net (code "627") (name "~{TP0_XTLK_DY}") (class "Default")
      (node (ref "A11") (pin "R2") (pinfunction "OUT_R2") (pintype "output"))
      (node (ref "A15") (pin "F2") (pinfunction "IN3_F2") (pintype "input"))
      (node (ref "A16") (pin "J2") (pinfunction "J2_J2") (pintype "input"))
      (node (ref "A16") (pin "K2") (pinfunction "K2_K2") (pintype "input"))
    )
    (net (code "628") (name "~{TP00}") (class "Default")
      (node (ref "A15") (pin "E1") (pinfunction "OUT_E1") (pintype "output"))
      (node (ref "A15") (pin "F1") (pinfunction "IN1_F1") (pintype "input"))
      (node (ref "A15") (pin "H1") (pinfunction "IN2_H1") (pintype "input"))
      (node (ref "A15") (pin "J1") (pinfunction "IN3_J1") (pintype "input"))
      (node (ref "A15") (pin "K1") (pinfunction "IN4_K1") (pintype "input"))
      (node (ref "B13") (pin "N1") (pinfunction "C_N1") (pintype "input"))
      (node (ref "CD18") (pin "AN1") (pinfunction "AN1_AN1") (pintype "input"))
    )
    (net (code "629") (name "~{TP01_A}") (class "Default")
      (node (ref "A15") (pin "R2") (pinfunction "IN1_R2") (pintype "input"))
      (node (ref "A15") (pin "S2") (pinfunction "IN2_S2") (pintype "input"))
      (node (ref "A15") (pin "T2") (pinfunction "IN3_T2") (pintype "input"))
      (node (ref "A15") (pin "U2") (pinfunction "IN4_U2") (pintype "input"))
      (node (ref "B16") (pin "L2") (pinfunction "F2_L2") (pintype "output"))
    )
    (net (code "630") (name "~{TP1_XTLK_DY}") (class "Default")
      (node (ref "A11") (pin "V2") (pinfunction "OUT_V2") (pintype "output"))
      (node (ref "A15") (pin "B1") (pinfunction "IN2_B1") (pintype "input"))
      (node (ref "B16") (pin "H2") (pinfunction "H2_H2") (pintype "input"))
      (node (ref "B16") (pin "J2") (pinfunction "J2_J2") (pintype "input"))
    )
    (net (code "631") (name "~{TP01}") (class "Default")
      (node (ref "A15") (pin "J2") (pinfunction "OUT_J2") (pintype "output"))
      (node (ref "A15") (pin "K2") (pinfunction "IN1_K2") (pintype "input"))
      (node (ref "A15") (pin "L2") (pinfunction "IN2_L2") (pintype "input"))
      (node (ref "A15") (pin "M2") (pinfunction "IN3_M2") (pintype "input"))
      (node (ref "A15") (pin "N2") (pinfunction "IN4_N2") (pintype "input"))
      (node (ref "B13") (pin "L2") (pinfunction "C_L2") (pintype "input"))
    )
    (net (code "632") (name "~{TS03}") (class "Default")
      (node (ref "C04") (pin "K1") (pinfunction "OUT_K1") (pintype "output"))
      (node (ref "D17") (pin "H2") (pinfunction "H2_H2") (pintype "input"))
      (node (ref "D17") (pin "J2") (pinfunction "J2_J2") (pintype "input"))
      (node (ref "D17") (pin "K2") (pinfunction "K2_K2") (pintype "input"))
    )
    (net (code "633") (name "~{T_00}") (class "Default")
      (node (ref "A24") (pin "V2") (pinfunction "P$2_V2") (pintype "bidirectional"))
      (node (ref "B22") (pin "V2") (pinfunction "E_V2") (pintype "output"))
      (node (ref "B23") (pin "V2") (pinfunction "P$1_V2") (pintype "passive"))
    )
    (net (code "634") (name "~{T_01}") (class "Default")
      (node (ref "A23") (pin "S1") (pinfunction "E_S1") (pintype "output"))
      (node (ref "A24") (pin "M2") (pinfunction "P$2_M2") (pintype "bidirectional"))
      (node (ref "B23") (pin "M2") (pinfunction "P$1_M2") (pintype "passive"))
    )
    (net (code "635") (name "~{T_02}") (class "Default")
      (node (ref "A23") (pin "H2") (pinfunction "D_H2") (pintype "output"))
      (node (ref "A24") (pin "N2") (pinfunction "P$2_N2") (pintype "bidirectional"))
      (node (ref "B23") (pin "N2") (pinfunction "P$1_N2") (pintype "passive"))
    )
    (net (code "636") (name "~{T_03}") (class "Default")
      (node (ref "A23") (pin "J2") (pinfunction "E_J2") (pintype "output"))
      (node (ref "A24") (pin "P2") (pinfunction "P$2_P2") (pintype "bidirectional"))
      (node (ref "B23") (pin "P2") (pinfunction "P$1_P2") (pintype "passive"))
    )
    (net (code "637") (name "~{T_04}") (class "Default")
      (node (ref "A23") (pin "N2") (pinfunction "D_N2") (pintype "output"))
      (node (ref "A24") (pin "R2") (pinfunction "P$2_R2") (pintype "bidirectional"))
      (node (ref "B23") (pin "R2") (pinfunction "P$1_R2") (pintype "passive"))
    )
    (net (code "638") (name "~{T_05}") (class "Default")
      (node (ref "A23") (pin "P2") (pinfunction "E_P2") (pintype "output"))
      (node (ref "A24") (pin "S2") (pinfunction "P$2_S2") (pintype "bidirectional"))
      (node (ref "B23") (pin "S2") (pinfunction "P$1_S2") (pintype "passive"))
    )
    (net (code "639") (name "~{T_06}") (class "Default")
      (node (ref "A23") (pin "U2") (pinfunction "D_U2") (pintype "output"))
      (node (ref "A24") (pin "T2") (pinfunction "P$2_T2") (pintype "bidirectional"))
      (node (ref "B23") (pin "T2") (pinfunction "P$1_T2") (pintype "passive"))
    )
    (net (code "640") (name "~{T_07}") (class "Default")
      (node (ref "A23") (pin "V2") (pinfunction "E_V2") (pintype "output"))
      (node (ref "A24") (pin "U2") (pinfunction "P$2_U2") (pintype "bidirectional"))
      (node (ref "B23") (pin "U2") (pinfunction "P$1_U2") (pintype "passive"))
    )
    (net (code "641") (name "~{T_FWD}") (class "Default")
      (node (ref "A23") (pin "K1") (pinfunction "D_K1") (pintype "output"))
      (node (ref "A24") (pin "E2") (pinfunction "P$2_E2") (pintype "bidirectional"))
      (node (ref "B23") (pin "H2") (pinfunction "P$1_H2") (pintype "passive"))
    )
    (net (code "642") (name "~{T_GO}") (class "Default")
      (node (ref "A23") (pin "D1") (pinfunction "D_D1") (pintype "output"))
      (node (ref "A24") (pin "C2") (pinfunction "P$2_C2") (pintype "bidirectional"))
      (node (ref "B23") (pin "D2") (pinfunction "P$1_D2") (pintype "passive"))
    )
    (net (code "643") (name "~{T_PWR_CLR}") (class "Default")
      (node (ref "A23") (pin "R1") (pinfunction "D_R1") (pintype "output"))
      (node (ref "A24") (pin "H2") (pinfunction "P$2_H2") (pintype "bidirectional"))
      (node (ref "B23") (pin "K2") (pinfunction "P$1_K2") (pintype "passive"))
    )
    (net (code "644") (name "~{T_REV}") (class "Default")
      (node (ref "A23") (pin "L1") (pinfunction "E_L1") (pintype "output"))
      (node (ref "A24") (pin "F2") (pinfunction "P$2_F2") (pintype "bidirectional"))
      (node (ref "B23") (pin "J2") (pinfunction "P$1_J2") (pintype "passive"))
    )
    (net (code "645") (name "~{T_SINGLE_UNIT}") (class "Default")
      (node (ref "A24") (pin "K2") (pinfunction "P$2_K2") (pintype "bidirectional"))
      (node (ref "B21") (pin "T2") (pinfunction "IN_T2") (pintype "input"))
    )
    (net (code "646") (name "~{T_STOP}") (class "Default")
      (node (ref "A23") (pin "E1") (pinfunction "E_E1") (pintype "output"))
      (node (ref "A24") (pin "D2") (pinfunction "P$2_D2") (pintype "bidirectional"))
      (node (ref "B23") (pin "E2") (pinfunction "P$1_E2") (pintype "passive"))
    )
    (net (code "647") (name "~{T_TRK}") (class "Default")
      (node (ref "A18") (pin "V2") (pinfunction "V2_V2") (pintype "output"))
      (node (ref "B15") (pin "E1") (pinfunction "IN2_E1") (pintype "input"))
    )
    (net (code "648") (name "~{T_WRITE_OK}") (class "Default")
      (node (ref "A22") (pin "H2") (pinfunction "H2_H2") (pintype "input"))
      (node (ref "A24") (pin "L2") (pinfunction "P$2_L2") (pintype "bidirectional"))
      (node (ref "B23") (pin "L2") (pinfunction "P$1_L2") (pintype "passive"))
    )
    (net (code "649") (name "~{U+M_DY}") (class "Default")
      (node (ref "C12") (pin "A1") (pinfunction "IN1_A1") (pintype "input"))
      (node (ref "C12") (pin "R2") (pinfunction "IN3_R2") (pintype "input"))
      (node (ref "D14") (pin "E2") (pinfunction "F2_E2") (pintype "output"))
      (node (ref "D14") (pin "N1") (pinfunction "N1_N1") (pintype "input"))
    )
    (net (code "650") (name "~{USR_00}") (class "Default")
      (node (ref "B03") (pin "A1") (pinfunction "A_A1") (pintype "input"))
      (node (ref "B07") (pin "F1") (pinfunction "F1_F1") (pintype "output"))
    )
    (net (code "651") (name "~{USR_01}") (class "Default")
      (node (ref "B03") (pin "B1") (pinfunction "B_B1") (pintype "input"))
      (node (ref "B07") (pin "J2") (pinfunction "J2_J2") (pintype "output"))
    )
    (net (code "652") (name "~{USR_02}") (class "Default")
      (node (ref "B03") (pin "F1") (pinfunction "A_F1") (pintype "input"))
      (node (ref "B07") (pin "M1") (pinfunction "M1_M1") (pintype "output"))
    )
    (net (code "653") (name "~{UTS}") (class "Default")
      (node (ref "C12") (pin "L2") (pinfunction "IN3_L2") (pintype "input"))
      (node (ref "C14") (pin "P2") (pinfunction "1_P2") (pintype "output"))
      (node (ref "C15") (pin "P2") (pinfunction "IN1_P2") (pintype "input"))
      (node (ref "C16") (pin "A1") (pinfunction "IN1_A1") (pintype "input"))
      (node (ref "C16") (pin "B1") (pinfunction "IN2_B1") (pintype "input"))
      (node (ref "C16") (pin "C1") (pinfunction "IN3_C1") (pintype "input"))
      (node (ref "C16") (pin "D1") (pinfunction "IN4_D1") (pintype "input"))
      (node (ref "C16") (pin "F1") (pinfunction "IN1_F1") (pintype "input"))
      (node (ref "C16") (pin "H1") (pinfunction "IN2_H1") (pintype "input"))
      (node (ref "C16") (pin "J1") (pinfunction "IN3_J1") (pintype "input"))
      (node (ref "C16") (pin "K1") (pinfunction "IN4_K1") (pintype "input"))
    )
    (net (code "654") (name "~{W-INH}") (class "Default")
      (node (ref "A08") (pin "V2") (pinfunction "1_V2") (pintype "output"))
      (node (ref "B11") (pin "L1") (pinfunction "IN2_L1") (pintype "input"))
      (node (ref "B12") (pin "H1") (pinfunction "IN2_H1") (pintype "input"))
    )
    (net (code "655") (name "~{WB00}") (class "Default")
      (node (ref "A21") (pin "P2") (pinfunction "P2_P2") (pintype "input"))
      (node (ref "B18") (pin "P2") (pinfunction "P2_P2") (pintype "input"))
      (node (ref "C10") (pin "D1") (pinfunction "IN2B_D1") (pintype "input"))
      (node (ref "C14") (pin "E1") (pinfunction "1_E1") (pintype "output"))
    )
    (net (code "656") (name "~{WB01}") (class "Default")
      (node (ref "B20") (pin "P2") (pinfunction "P2_P2") (pintype "input"))
      (node (ref "C10") (pin "K1") (pinfunction "IN2B_K1") (pintype "input"))
      (node (ref "C14") (pin "H2") (pinfunction "1_H2") (pintype "output"))
    )
    (net (code "657") (name "~{WB02}") (class "Default")
      (node (ref "A20") (pin "P2") (pinfunction "P2_P2") (pintype "input"))
      (node (ref "C10") (pin "R1") (pinfunction "IN2B_R1") (pintype "input"))
      (node (ref "C14") (pin "L1") (pinfunction "1_L1") (pintype "output"))
    )
    (net (code "658") (name "~{WC0}") (class "Default")
      (node (ref "C06") (pin "N2") (pinfunction "OUT_N2") (pintype "output"))
      (node (ref "D11") (pin "R1") (pinfunction "S_R1") (pintype "input"))
    )
    (net (code "659") (name "~{WC}") (class "Default")
      (node (ref "B12") (pin "F2") (pinfunction "IN3_F2") (pintype "input"))
      (node (ref "C12") (pin "T2") (pinfunction "IN1_T2") (pintype "input"))
      (node (ref "D11") (pin "M2") (pinfunction "D_M2") (pintype "input"))
      (node (ref "D11") (pin "S1") (pinfunction "1_S1") (pintype "output"))
    )
    (net (code "660") (name "~{WRITE_ALL}") (class "Default")
      (node (ref "D07") (pin "M1") (pinfunction "~{O5}_M1") (pintype "output"))
    )
    (net (code "661") (name "~{WRITE_DATA}") (class "Default")
      (node (ref "B08") (pin "M2") (pinfunction "IN2_M2") (pintype "input"))
      (node (ref "D07") (pin "F1") (pinfunction "~{O4}_F1") (pintype "output"))
    )
    (net (code "662") (name "~{WRITE_OK}") (class "Default")
      (node (ref "A10") (pin "J1") (pinfunction "IN2_J1") (pintype "input"))
      (node (ref "C17") (pin "J2") (pinfunction "OUT_J2") (pintype "output"))
    )
    (net (code "663") (name "~{WRTM}") (class "Default")
      (node (ref "B08") (pin "H2") (pinfunction "IN1_H2") (pintype "input"))
      (node (ref "C10") (pin "M2") (pinfunction "IN2A_M2") (pintype "input"))
      (node (ref "D07") (pin "H1") (pinfunction "~{O6}_H1") (pintype "output"))
    )
    (net (code "664") (name "~{WR_EN}") (class "Default")
      (node (ref "B11") (pin "F1") (pinfunction "IN2_F1") (pintype "input"))
      (node (ref "C11") (pin "H2") (pinfunction "IN1_H2") (pintype "input"))
      (node (ref "C12") (pin "J2") (pinfunction "IN1_J2") (pintype "input"))
      (node (ref "C14") (pin "S1") (pinfunction "1_S1") (pintype "output"))
      (node (ref "C15") (pin "D2") (pinfunction "IN1_D2") (pintype "input"))
      (node (ref "C15") (pin "H2") (pinfunction "IN1_H2") (pintype "input"))
    )
    (net (code "665") (name "~{XSAD}") (class "Default")
      (node (ref "A11") (pin "K2") (pinfunction "IN_K2") (pintype "input"))
      (node (ref "D13") (pin "L2") (pinfunction "F2_L2") (pintype "output"))
    )
    (net (code "666") (name "~{XSTA}") (class "Default")
      (node (ref "B08") (pin "R2") (pinfunction "IN2_R2") (pintype "input"))
      (node (ref "C04") (pin "F1") (pinfunction "F1_F1") (pintype "output"))
      (node (ref "D13") (pin "H2") (pinfunction "H2_H2") (pintype "input"))
      (node (ref "D13") (pin "J2") (pinfunction "J2_J2") (pintype "input"))
      (node (ref "D13") (pin "K2") (pinfunction "K2_K2") (pintype "input"))
      (node (ref "D14") (pin "K2") (pinfunction "U1_K2") (pintype "input"))
      (node (ref "D14") (pin "L2") (pinfunction "S1_L2") (pintype "input"))
      (node (ref "D16") (pin "M2") (pinfunction "H2_M2") (pintype "input"))
      (node (ref "D16") (pin "N2") (pinfunction "J2_N2") (pintype "input"))
    )
  )
)
